# cw-lite-main.net
KiCad netlist of a schematic drawn in EAGLE
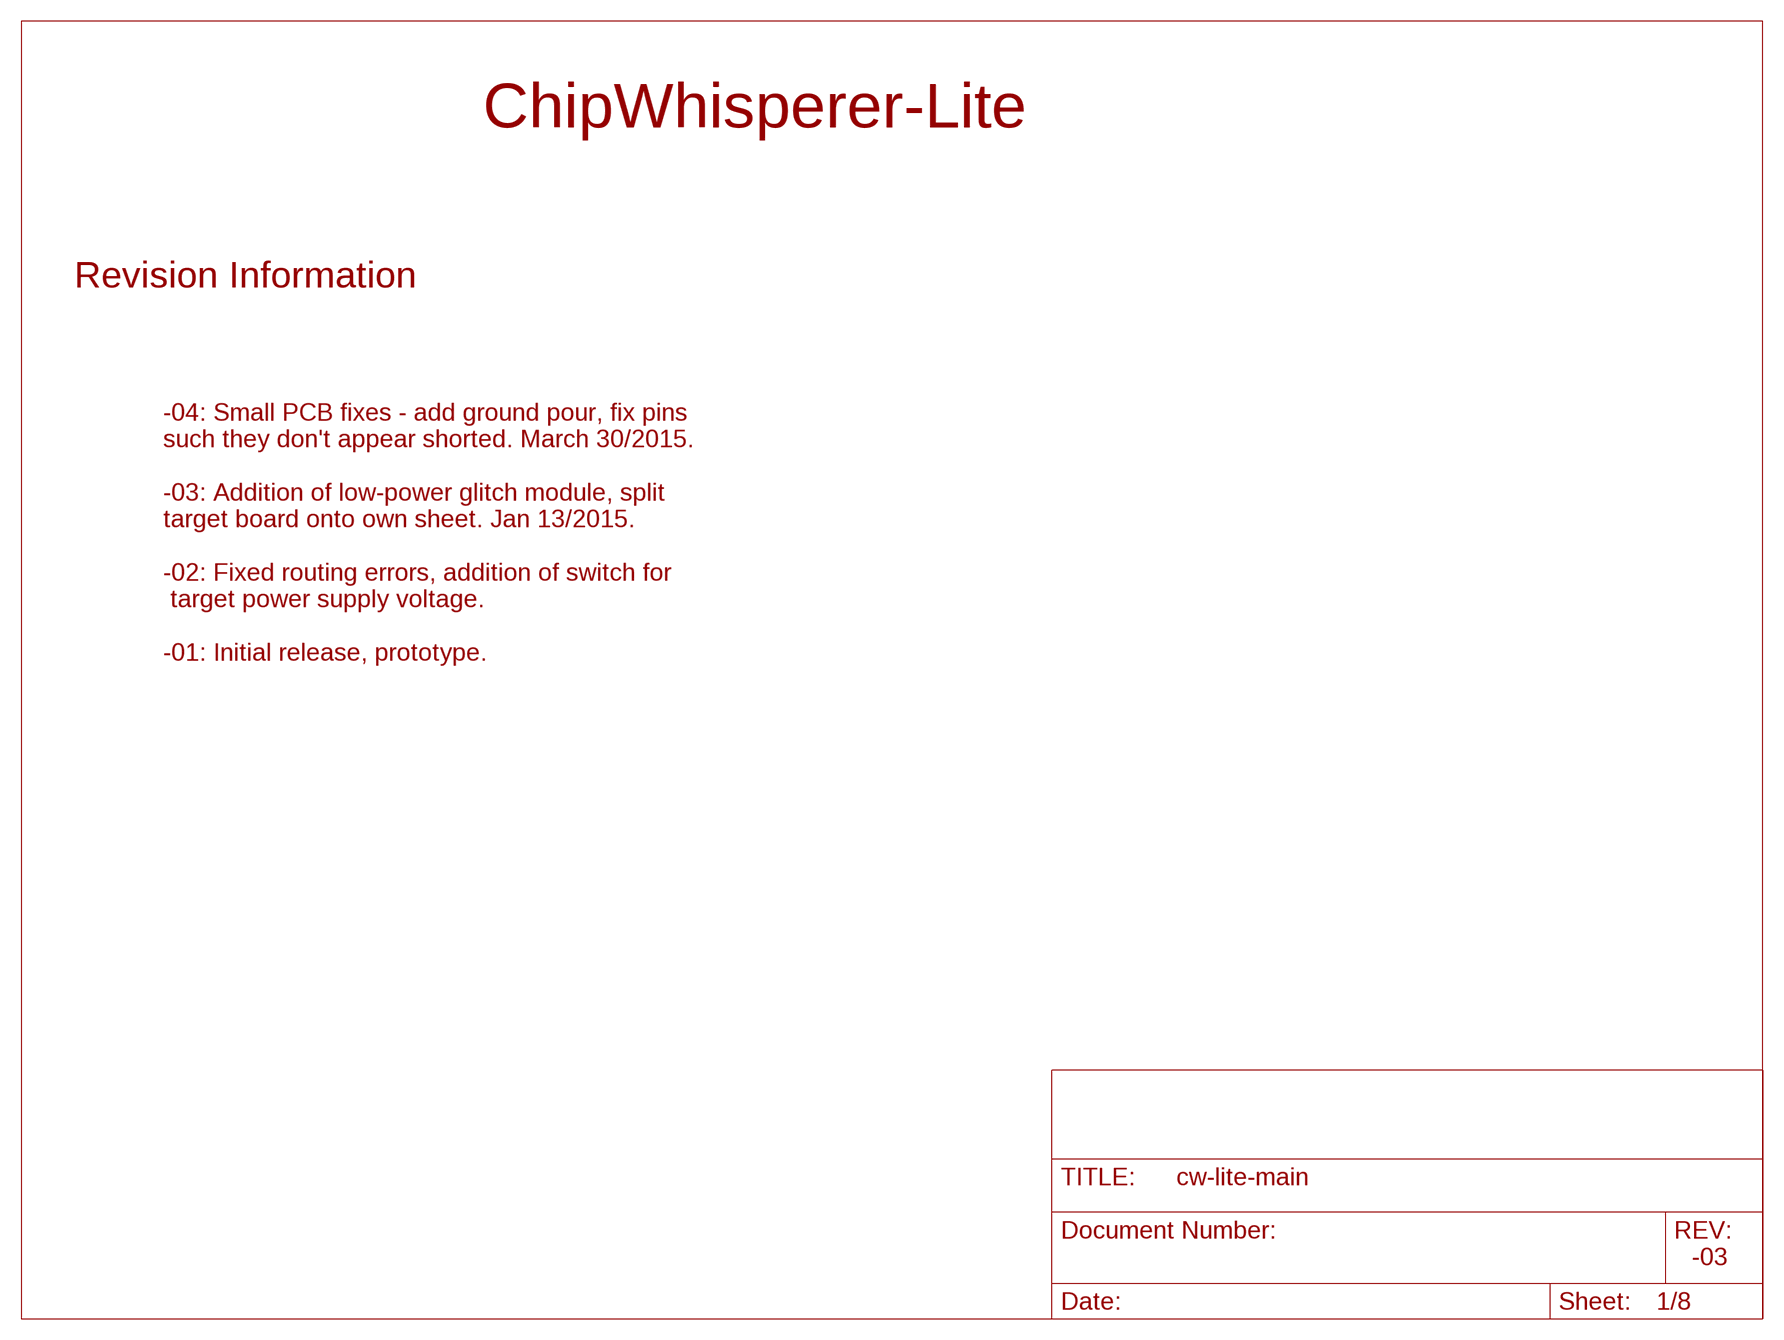
[diagram p0: schematic, sheet 1]
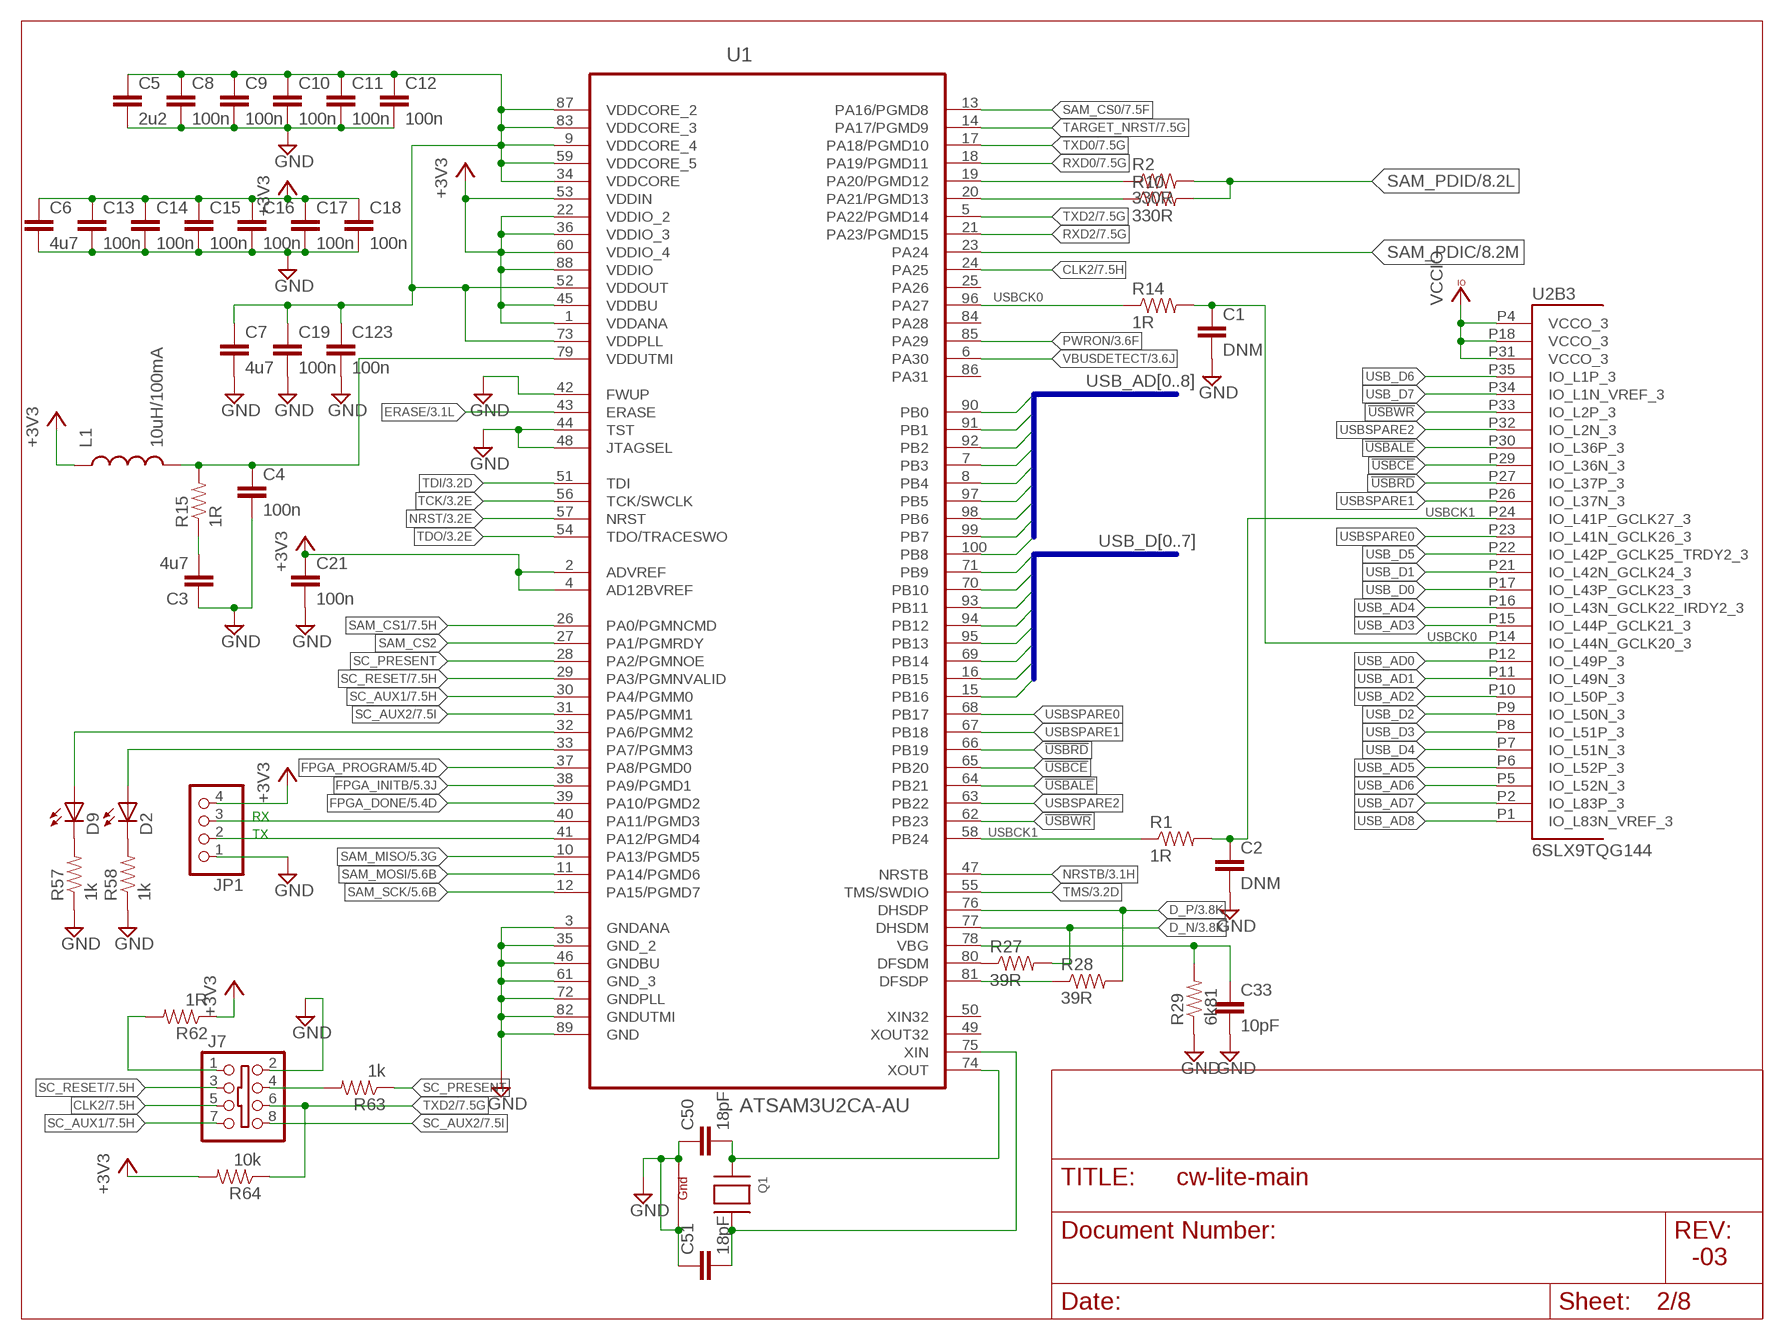
[diagram p1: schematic, sheet 2]
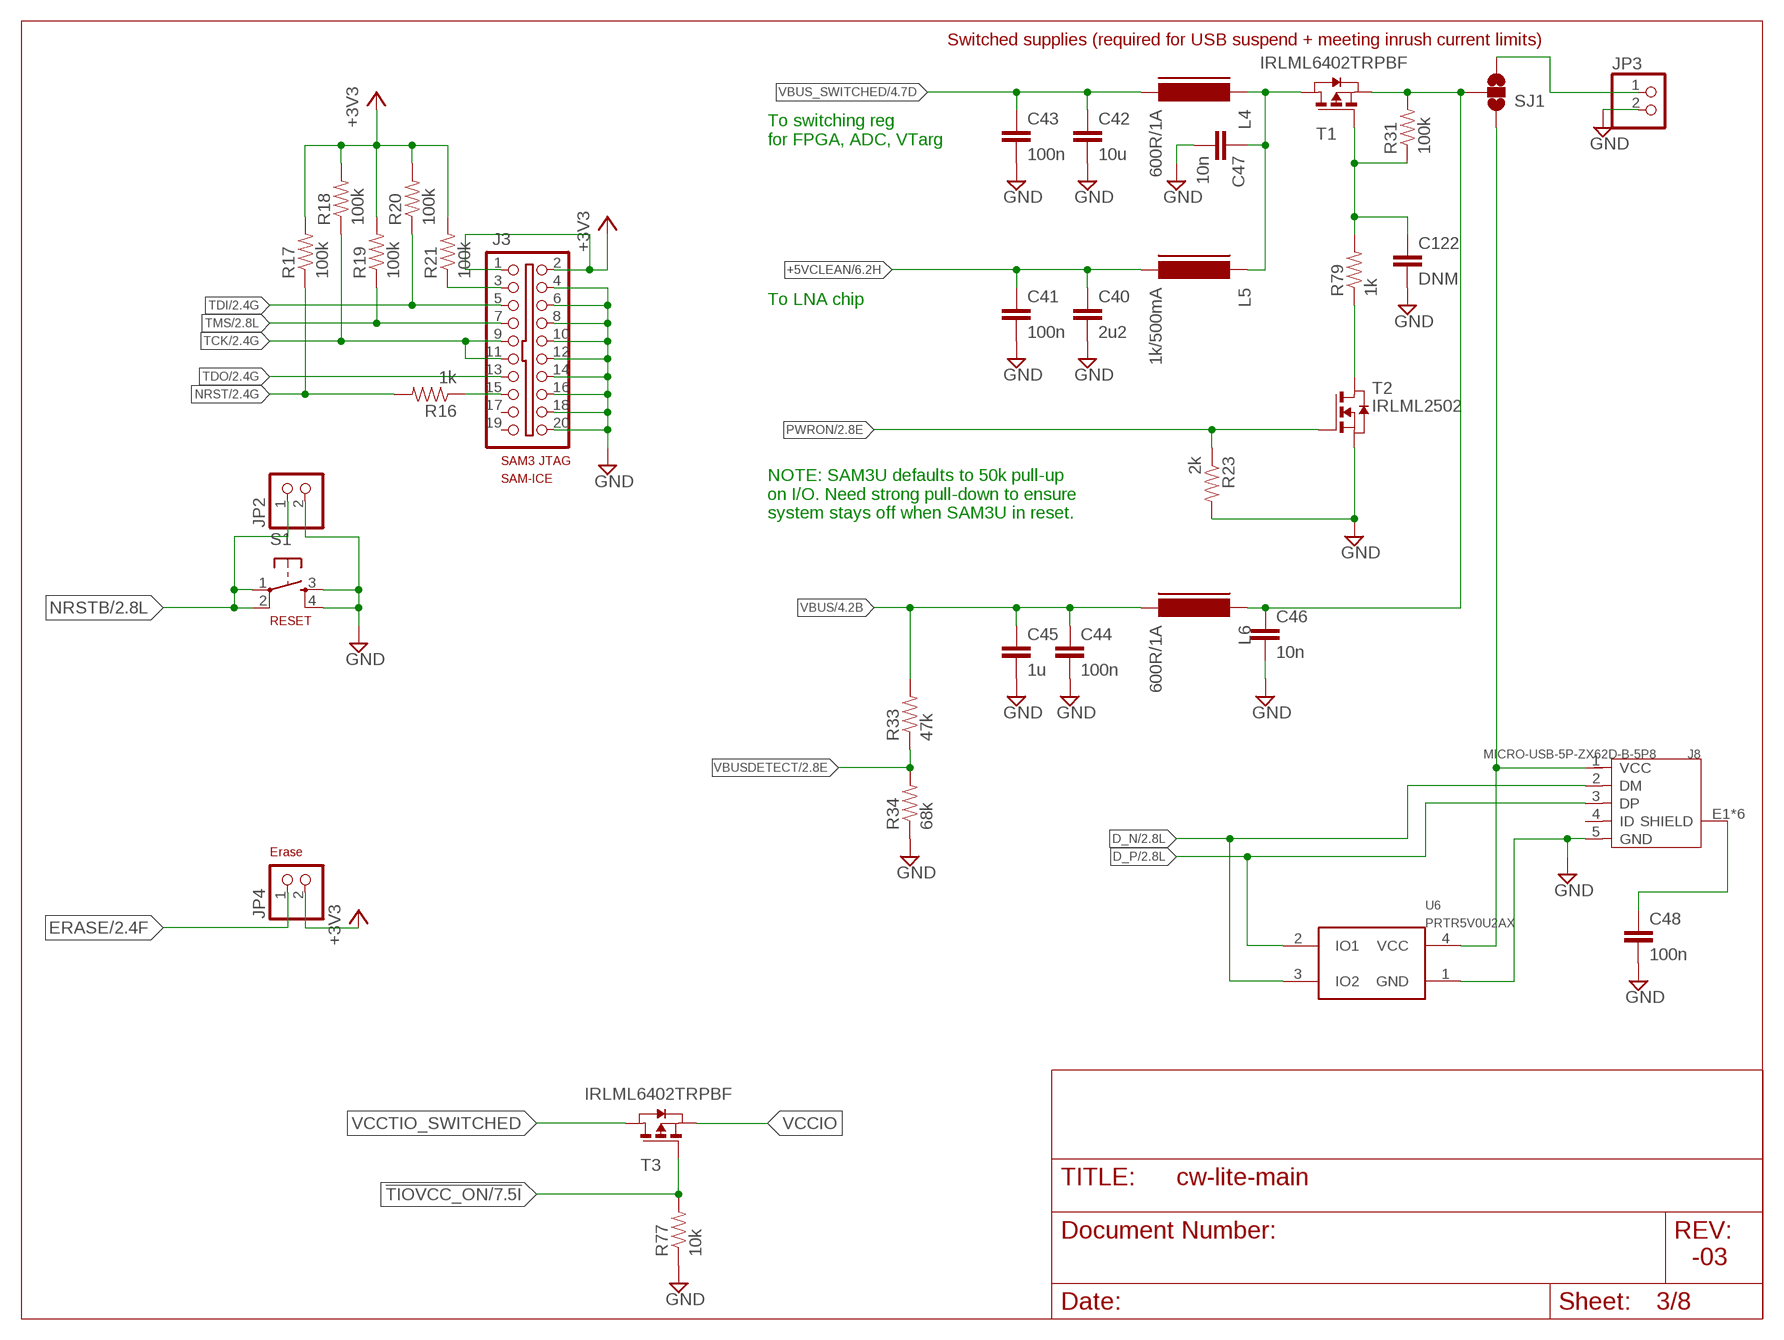
[diagram p2: schematic, sheet 3]
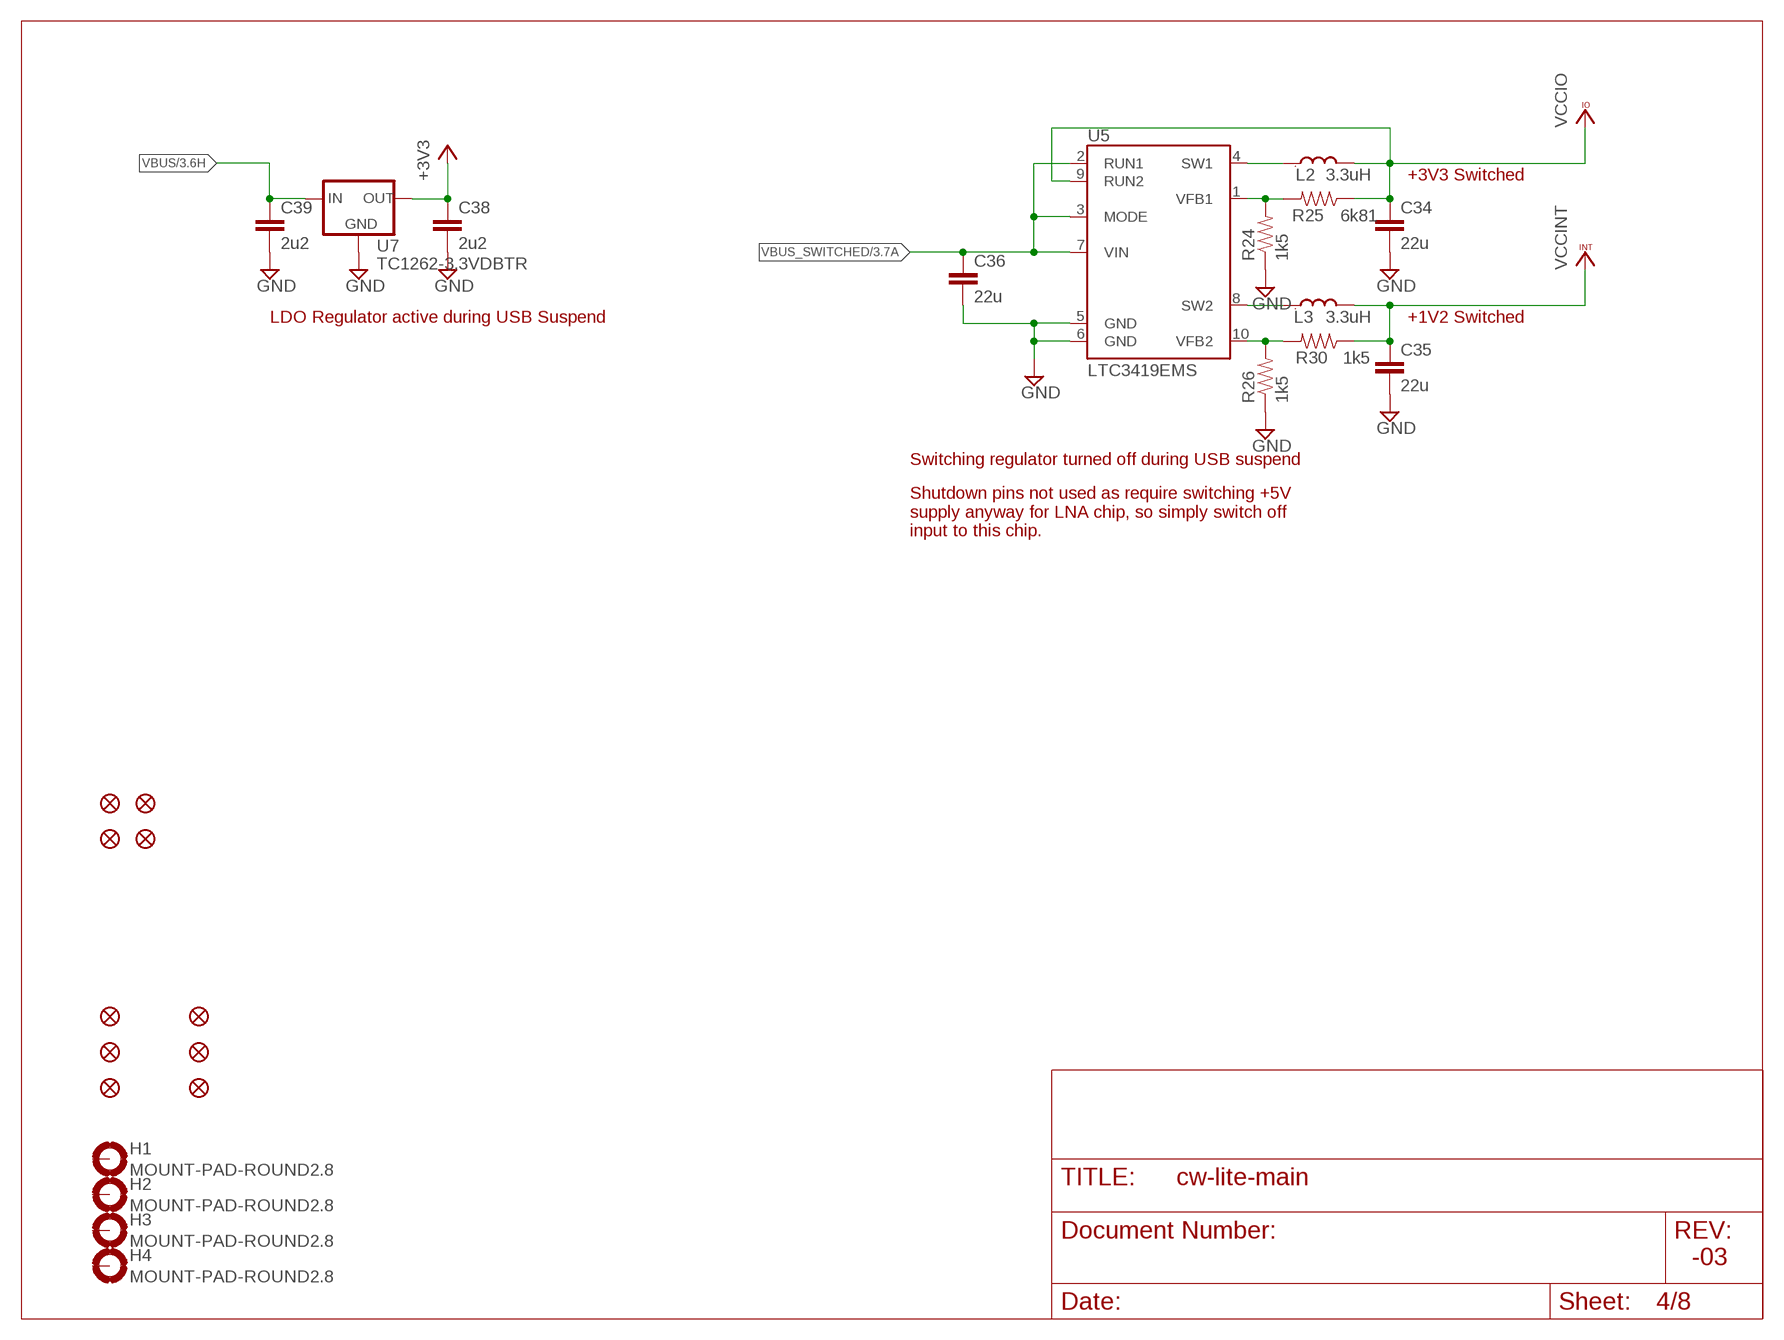
[diagram p3: schematic, sheet 4]
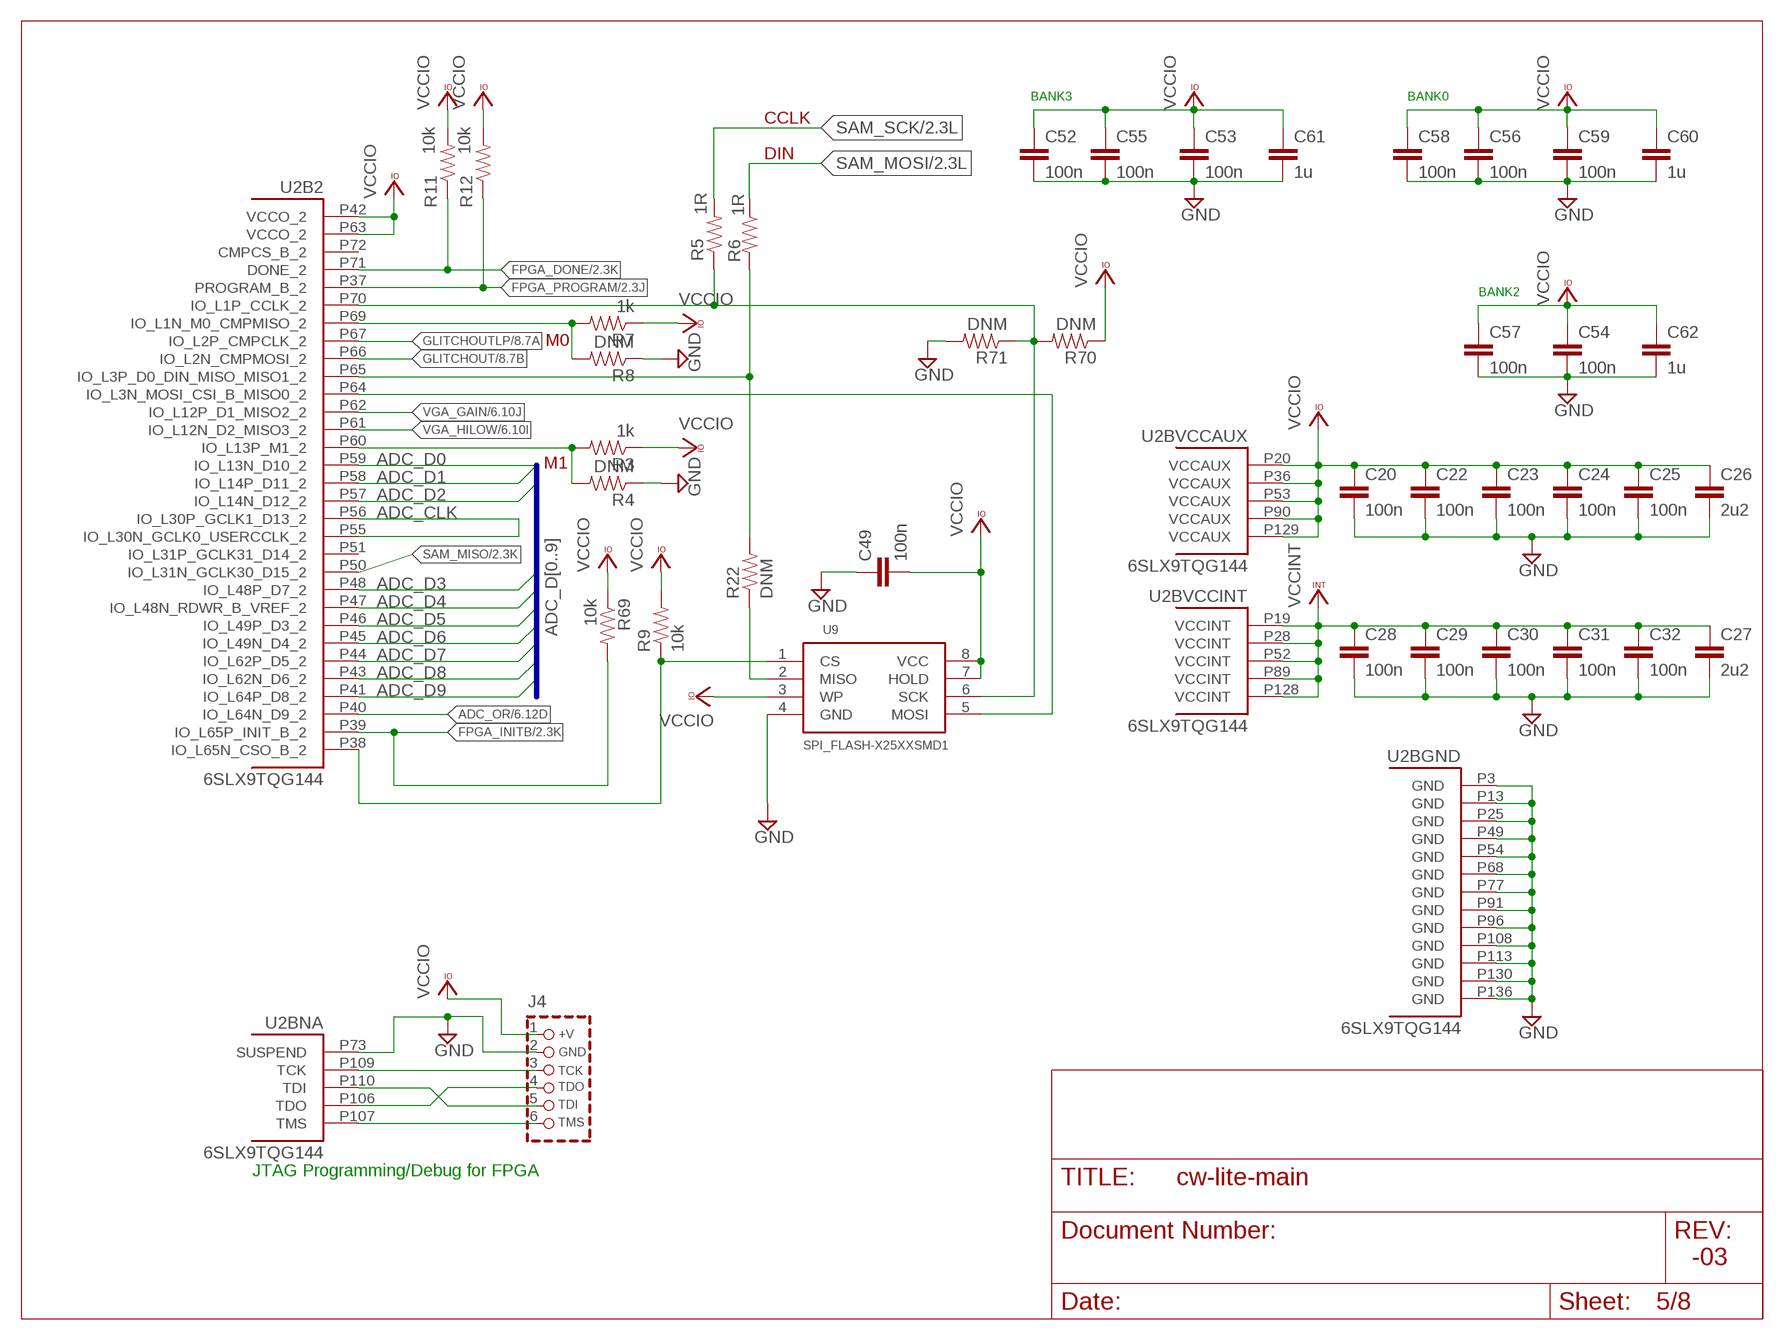
[diagram p4: schematic, sheet 5]
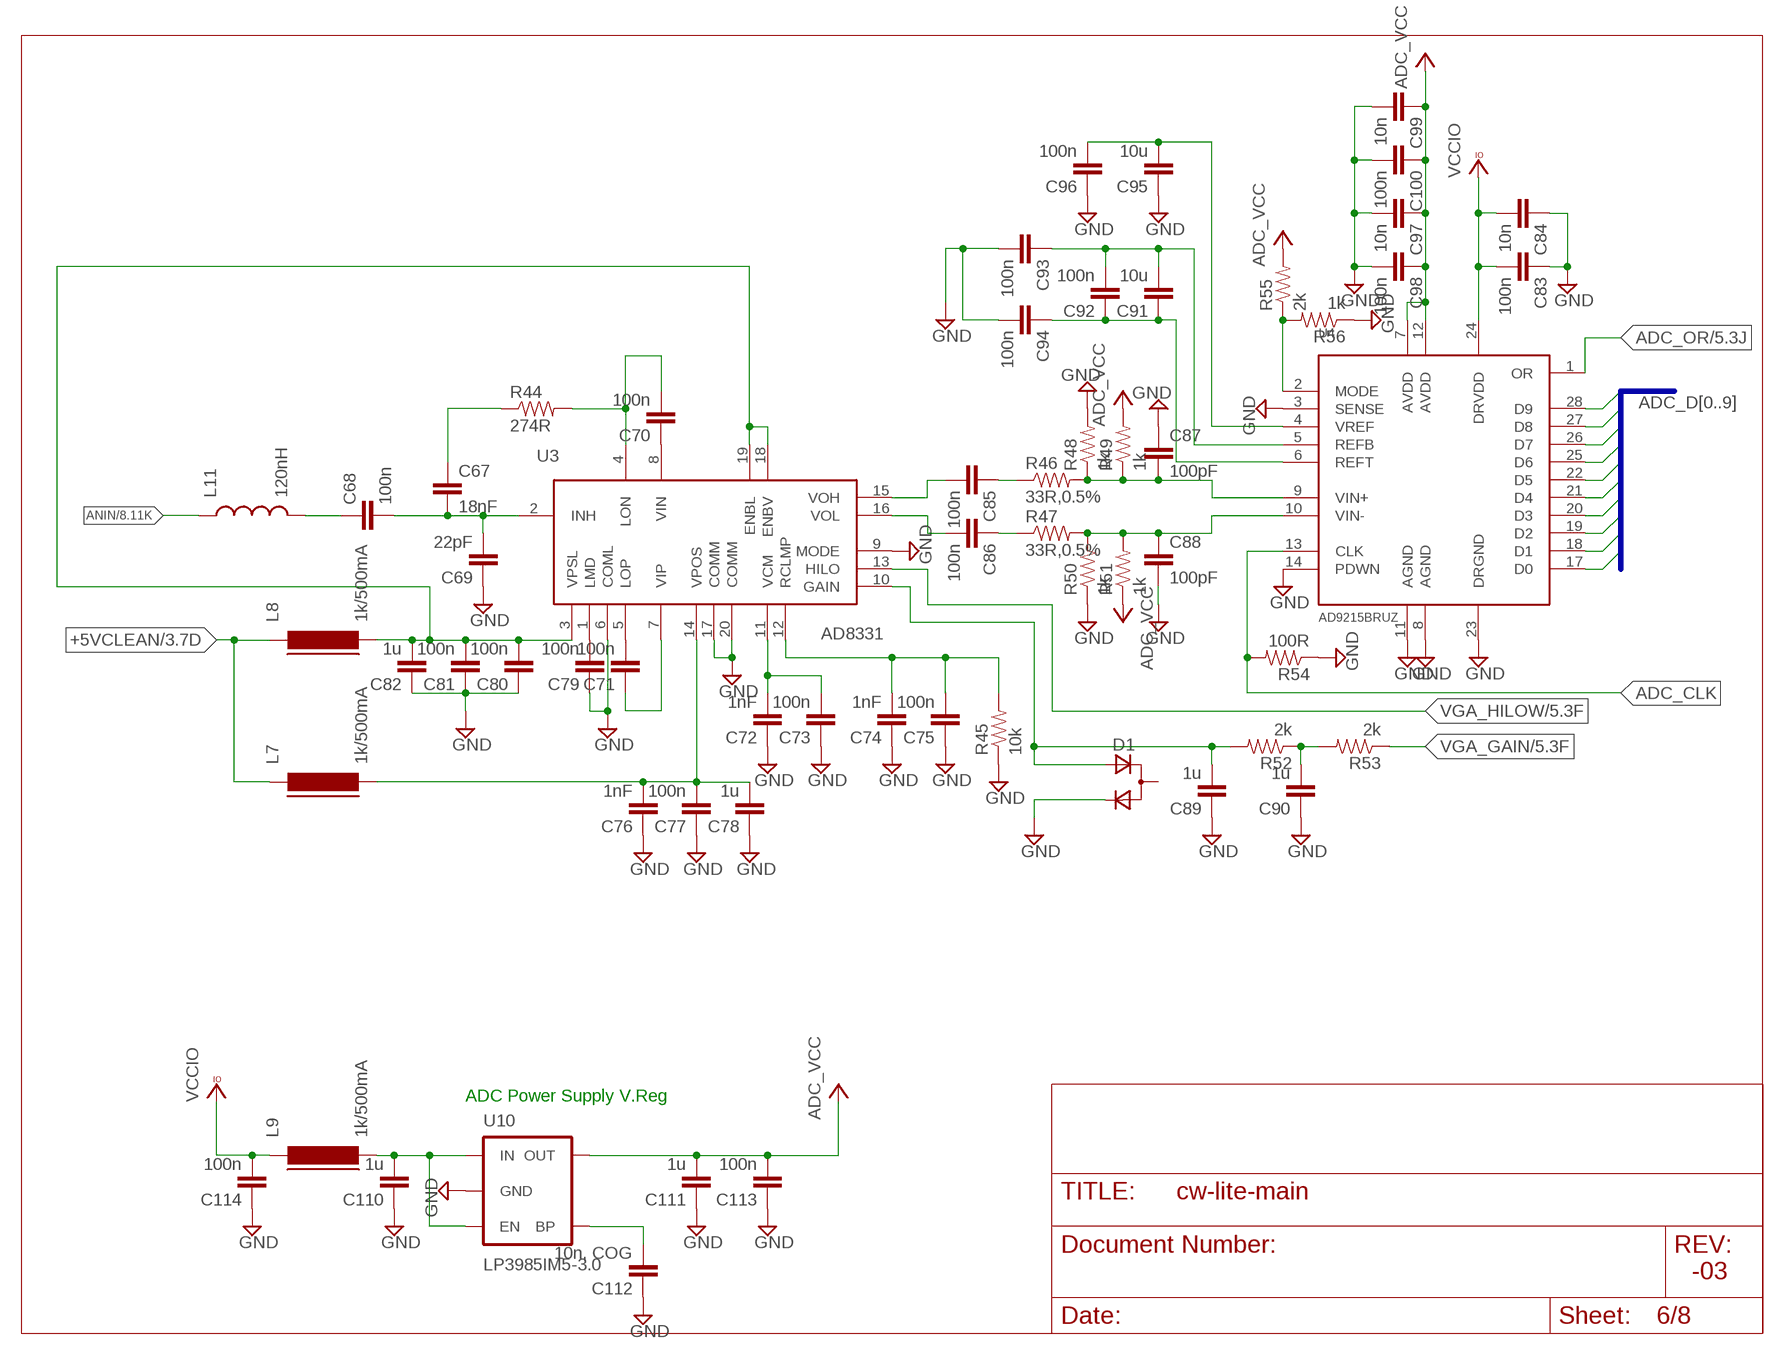
[diagram p5: schematic, sheet 6]
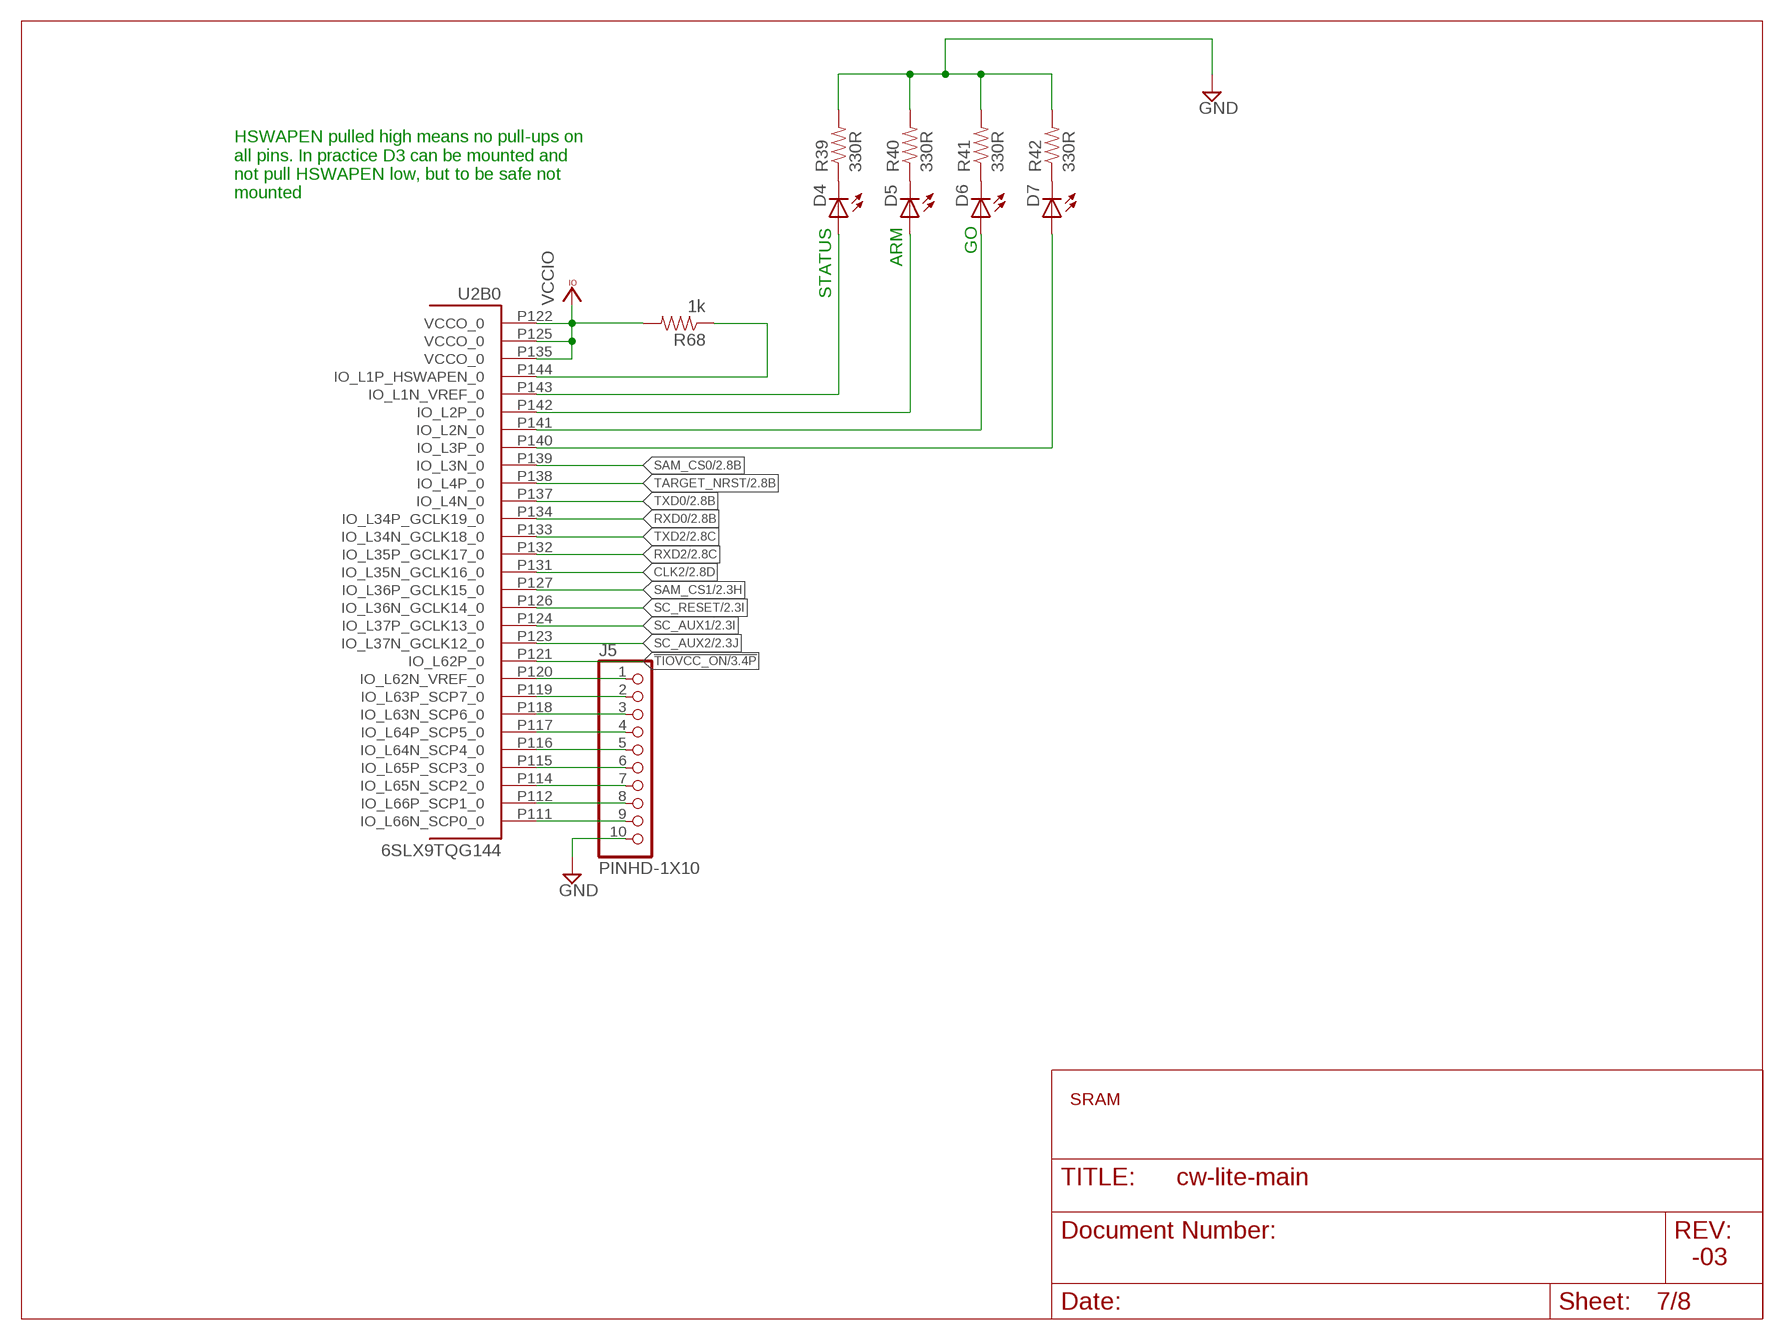
[diagram p6: schematic, sheet 7]
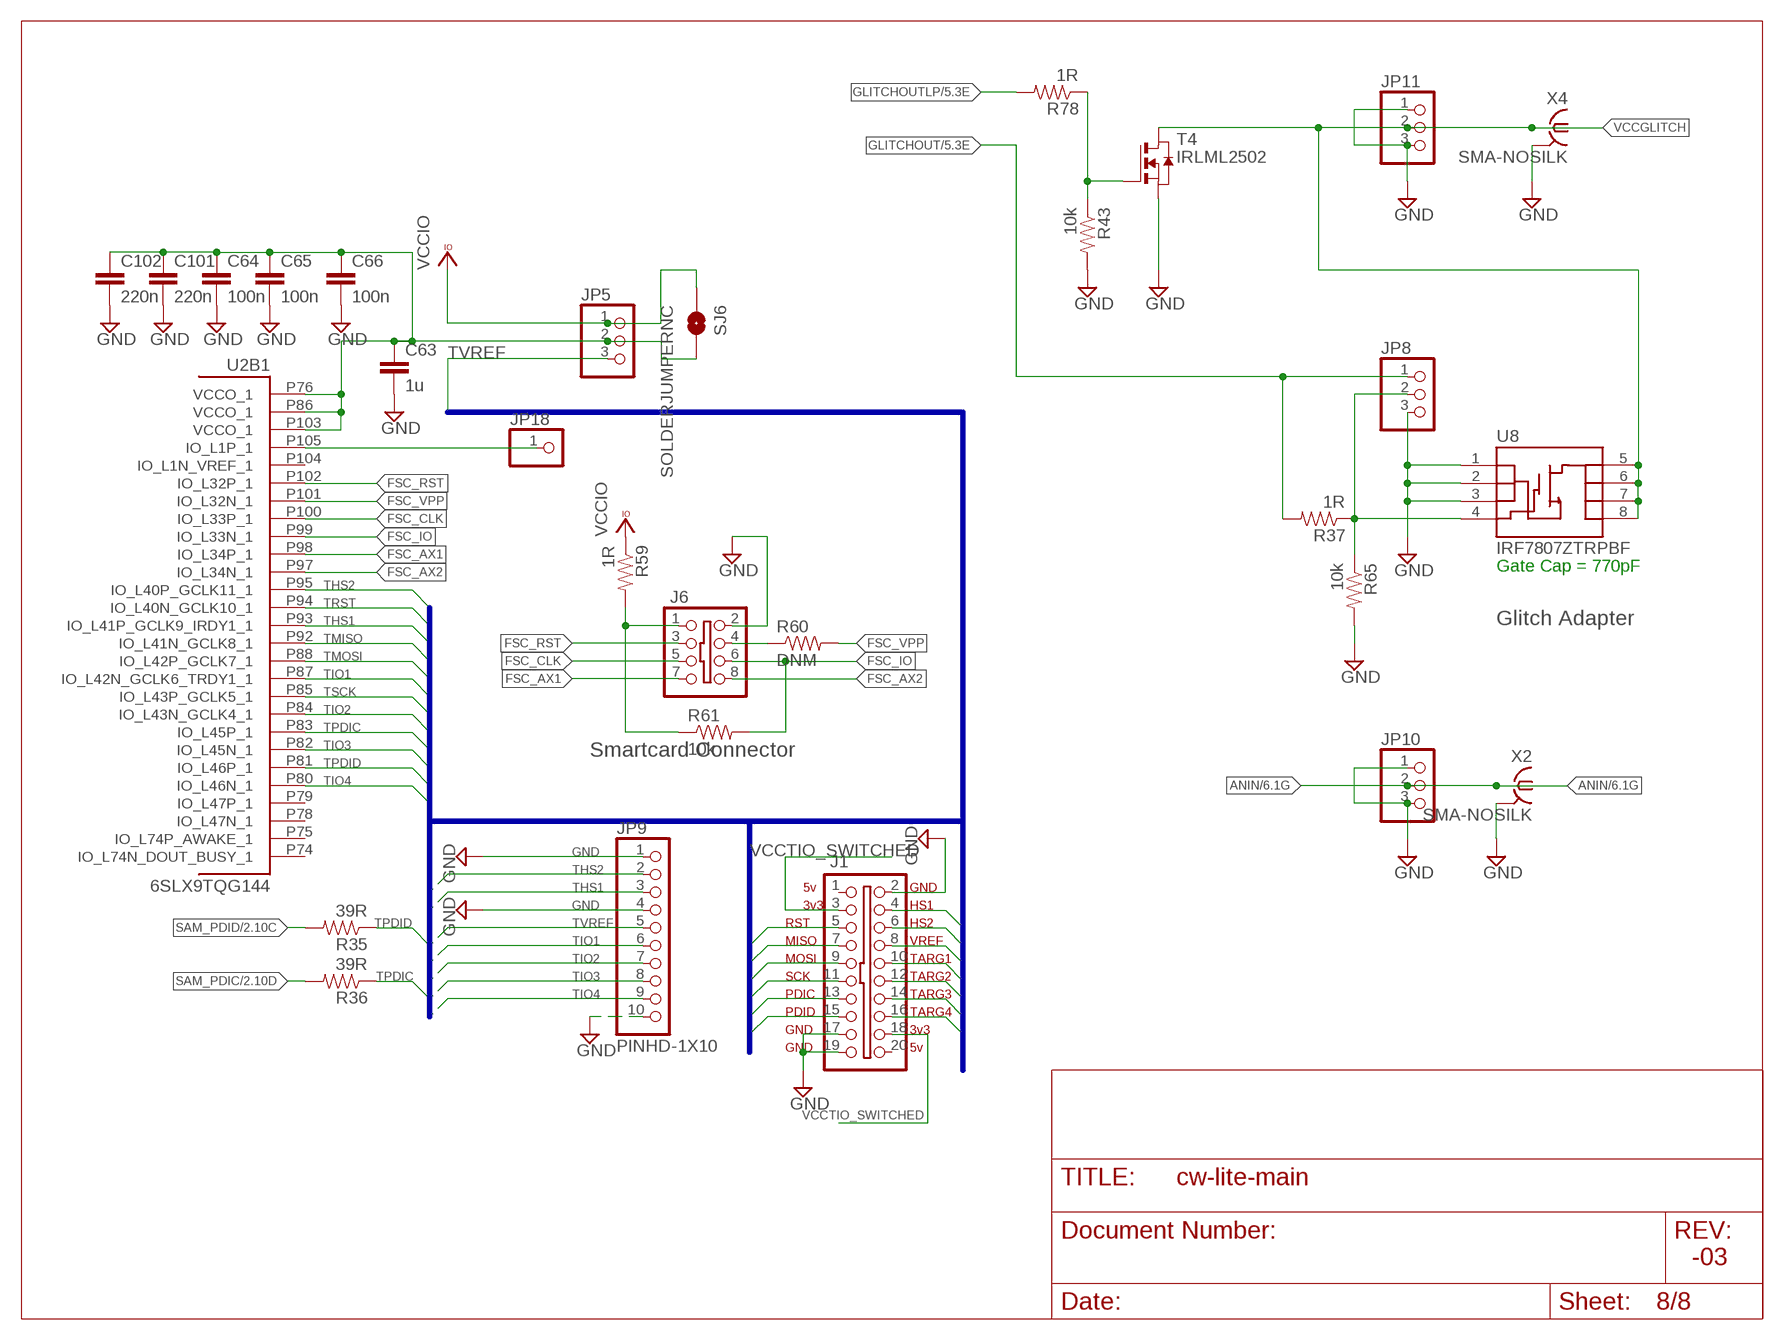
[diagram p7: schematic, sheet 8]

(export (version "E")
  (design (tool "Eeschema 10.0.6"))
  (components
    (comp (ref "D4")
      (value "LED0603")
      (footprint "eagle-import:LED-0603")
      (libsource (lib "eagle-import") (part "LED0603"))
    )
    (comp (ref "D5")
      (value "LED0603")
      (footprint "eagle-import:LED-0603")
      (libsource (lib "eagle-import") (part "LED0603"))
    )
    (comp (ref "D6")
      (value "LED0603")
      (footprint "eagle-import:LED-0603")
      (libsource (lib "eagle-import") (part "LED0603"))
    )
    (comp (ref "D7")
      (value "LED0603")
      (footprint "eagle-import:LED-0603")
      (libsource (lib "eagle-import") (part "LED0603"))
    )
    (comp (ref "J5")
      (value "PINHD-1X10")
      (footprint "eagle-import:1X10-BIG")
      (libsource (lib "eagle-import") (part "PINHD-1X10"))
    )
    (comp (ref "R39")
      (value "330R")
      (footprint "eagle-import:0402R")
      (libsource (lib "eagle-import") (part "custom-std_RES0402-RES"))
    )
    (comp (ref "R40")
      (value "330R")
      (footprint "eagle-import:0402R")
      (libsource (lib "eagle-import") (part "custom-std_RES0402-RES"))
    )
    (comp (ref "R41")
      (value "330R")
      (footprint "eagle-import:0402R")
      (libsource (lib "eagle-import") (part "custom-std_RES0402-RES"))
    )
    (comp (ref "R42")
      (value "330R")
      (footprint "eagle-import:0402R")
      (libsource (lib "eagle-import") (part "custom-std_RES0402-RES"))
    )
    (comp (ref "R68")
      (value "1k")
      (footprint "eagle-import:0402R")
      (libsource (lib "eagle-import") (part "custom-std_RES0402-RES"))
    )
    (comp (ref "U2")
      (value "6SLX9TQG144")
      (footprint "eagle-import:TQ144")
      (fields (field (name "MPN") "XC6SLX9-3TQG144C") (field (name "OC_DIGIKEY") "122-1748-ND"))
      (libsource (lib "eagle-import") (part "6SLX9TQG144"))
    )
    (comp (ref "C40")
      (value "2u2")
      (footprint "eagle-import:0603C")
      (libsource (lib "eagle-import") (part "custom-std_CAP0603-CAP"))
    )
    (comp (ref "C41")
      (value "100n")
      (footprint "eagle-import:0603C")
      (libsource (lib "eagle-import") (part "custom-std_CAP0603-CAP"))
    )
    (comp (ref "C42")
      (value "10u")
      (footprint "eagle-import:0603C")
      (libsource (lib "eagle-import") (part "custom-std_CAP0603-CAP"))
    )
    (comp (ref "C43")
      (value "100n")
      (footprint "eagle-import:0603C")
      (libsource (lib "eagle-import") (part "custom-std_CAP0603-CAP"))
    )
    (comp (ref "C44")
      (value "100n")
      (footprint "eagle-import:0603C")
      (libsource (lib "eagle-import") (part "custom-std_CAP0603-CAP"))
    )
    (comp (ref "C45")
      (value "1u")
      (footprint "eagle-import:0603C")
      (libsource (lib "eagle-import") (part "custom-std_CAP0603-CAP"))
    )
    (comp (ref "C46")
      (value "10n")
      (footprint "eagle-import:0603C")
      (libsource (lib "eagle-import") (part "custom-std_CAP0603-CAP"))
    )
    (comp (ref "C47")
      (value "10n")
      (footprint "eagle-import:0603C")
      (libsource (lib "eagle-import") (part "custom-std_CAP0603-CAP"))
    )
    (comp (ref "C48")
      (value "100n")
      (footprint "eagle-import:0603C")
      (libsource (lib "eagle-import") (part "custom-std_CAP0603-CAP"))
    )
    (comp (ref "C122")
      (value "DNM")
      (footprint "eagle-import:0603C")
      (libsource (lib "eagle-import") (part "custom-std_CAP0603-CAP"))
    )
    (comp (ref "J3")
      (value "SHROUD_2X10-SHROUDED")
      (footprint "eagle-import:PINSHRD_PTH_2X10")
      (libsource (lib "eagle-import") (part "SHROUD_2X10-SHROUDED"))
    )
    (comp (ref "J8")
      (value "MICRO-USB-5P-ZX62D-B-5P8")
      (footprint "eagle-import:B-SMD-5P-TH")
      (fields (field (name "MPN") "ZX62D-B-5P8") (field (name "OC_DIGIKEY") "H11610CT-ND"))
      (libsource (lib "eagle-import") (part "MICRO-USB-5P-ZX62D-B-5P8"))
    )
    (comp (ref "JP2")
      (value "PINHD-1X2")
      (footprint "eagle-import:1X02")
      (libsource (lib "eagle-import") (part "PINHD-1X2"))
    )
    (comp (ref "JP3")
      (value "PINHD-1X2")
      (footprint "eagle-import:1X02")
      (libsource (lib "eagle-import") (part "PINHD-1X2"))
    )
    (comp (ref "JP4")
      (value "PINHD-1X2")
      (footprint "eagle-import:1X02")
      (libsource (lib "eagle-import") (part "PINHD-1X2"))
    )
    (comp (ref "L4")
      (value "600R/1A")
      (footprint "eagle-import:FB603")
      (libsource (lib "eagle-import") (part "FERRITE-0603"))
    )
    (comp (ref "L5")
      (value "1k/500mA")
      (footprint "eagle-import:FB603")
      (libsource (lib "eagle-import") (part "FERRITE-0603"))
    )
    (comp (ref "L6")
      (value "600R/1A")
      (footprint "eagle-import:FB603")
      (libsource (lib "eagle-import") (part "FERRITE-0603"))
    )
    (comp (ref "R16")
      (value "1k")
      (footprint "eagle-import:0402R")
      (libsource (lib "eagle-import") (part "RES0402-RES"))
    )
    (comp (ref "R17")
      (value "100k")
      (footprint "eagle-import:0402R")
      (libsource (lib "eagle-import") (part "RES0402-RES"))
    )
    (comp (ref "R18")
      (value "100k")
      (footprint "eagle-import:0402R")
      (libsource (lib "eagle-import") (part "RES0402-RES"))
    )
    (comp (ref "R19")
      (value "100k")
      (footprint "eagle-import:0402R")
      (libsource (lib "eagle-import") (part "RES0402-RES"))
    )
    (comp (ref "R20")
      (value "100k")
      (footprint "eagle-import:0402R")
      (libsource (lib "eagle-import") (part "RES0402-RES"))
    )
    (comp (ref "R21")
      (value "100k")
      (footprint "eagle-import:0402R")
      (libsource (lib "eagle-import") (part "RES0402-RES"))
    )
    (comp (ref "R23")
      (value "2k")
      (footprint "eagle-import:0603R")
      (libsource (lib "eagle-import") (part "custom-std_RES0603-RES"))
    )
    (comp (ref "R31")
      (value "100k")
      (footprint "eagle-import:0402R")
      (libsource (lib "eagle-import") (part "custom-std_RES0402-RES"))
    )
    (comp (ref "R33")
      (value "47k")
      (footprint "eagle-import:0402R")
      (libsource (lib "eagle-import") (part "custom-std_RES0402-RES"))
    )
    (comp (ref "R34")
      (value "68k")
      (footprint "eagle-import:0402R")
      (libsource (lib "eagle-import") (part "custom-std_RES0402-RES"))
    )
    (comp (ref "R77")
      (value "10k")
      (footprint "eagle-import:0402R")
      (libsource (lib "eagle-import") (part "custom-std_RES0402-RES"))
    )
    (comp (ref "R79")
      (value "1k")
      (footprint "eagle-import:0603R")
      (libsource (lib "eagle-import") (part "custom-std_RES0603-RES"))
    )
    (comp (ref "S1")
      (value "TAC_SWITCHSMD")
      (footprint "eagle-import:TACTILE_SWITCH_SMD")
      (libsource (lib "eagle-import") (part "TAC_SWITCHSMD"))
    )
    (comp (ref "SJ1")
      (value "SOLDERJUMPER_2WAYPASTE1&2")
      (footprint "eagle-import:SJ_3_PASTE1&2")
      (libsource (lib "eagle-import") (part "SOLDERJUMPER_2WAYPASTE1&2"))
    )
    (comp (ref "T1")
      (value "IRLML6402TRPBF")
      (footprint "eagle-import:SOT-23")
      (fields (field (name "MPN") "IRLML6402TRPBF") (field (name "OC_DIGIKEY") "IRLML6402PBFCT-ND"))
      (libsource (lib "eagle-import") (part "PMOSSOT23"))
    )
    (comp (ref "T2")
      (value "IRLML2502")
      (footprint "eagle-import:SOT-23")
      (fields (field (name "MPN") "IRLML2502TRPBF") (field (name "OC_DIGIKEY") "IRLML2502PBFCT-ND"))
      (libsource (lib "eagle-import") (part "NMOSSOT23"))
    )
    (comp (ref "T3")
      (value "IRLML6402TRPBF")
      (footprint "eagle-import:SOT-23")
      (fields (field (name "MPN") "IRLML6402TRPBF") (field (name "OC_DIGIKEY") "IRLML6402PBFCT-ND"))
      (libsource (lib "eagle-import") (part "PMOSSOT23"))
    )
    (comp (ref "U6")
      (value "PRTR5V0U2AX")
      (footprint "eagle-import:SOT143B")
      (fields (field (name "MPN") "PRTR5V0U2AX,215") (field (name "OC_DIGIKEY") "568-4139-1-ND"))
      (libsource (lib "eagle-import") (part "PRTR5V0U2AX"))
    )
    (comp (ref "C67")
      (value "18nF")
      (footprint "eagle-import:0603C")
      (libsource (lib "eagle-import") (part "custom-std_CAP0603-CAP"))
    )
    (comp (ref "C68")
      (value "100n")
      (footprint "eagle-import:0603C")
      (libsource (lib "eagle-import") (part "custom-std_CAP0603-CAP"))
    )
    (comp (ref "C69")
      (value "22pF")
      (footprint "eagle-import:0603C")
      (libsource (lib "eagle-import") (part "custom-std_CAP0603-CAP"))
    )
    (comp (ref "C70")
      (value "100n")
      (footprint "eagle-import:0402C")
      (libsource (lib "eagle-import") (part "custom-std_CAP0402-CAP"))
    )
    (comp (ref "C71")
      (value "100n")
      (footprint "eagle-import:0402C")
      (libsource (lib "eagle-import") (part "custom-std_CAP0402-CAP"))
    )
    (comp (ref "C72")
      (value "1nF")
      (footprint "eagle-import:0402C")
      (libsource (lib "eagle-import") (part "custom-std_CAP0402-CAP"))
    )
    (comp (ref "C73")
      (value "100n")
      (footprint "eagle-import:0402C")
      (libsource (lib "eagle-import") (part "custom-std_CAP0402-CAP"))
    )
    (comp (ref "C74")
      (value "1nF")
      (footprint "eagle-import:0402C")
      (libsource (lib "eagle-import") (part "custom-std_CAP0402-CAP"))
    )
    (comp (ref "C75")
      (value "100n")
      (footprint "eagle-import:0402C")
      (libsource (lib "eagle-import") (part "custom-std_CAP0402-CAP"))
    )
    (comp (ref "C76")
      (value "1nF")
      (footprint "eagle-import:0402C")
      (libsource (lib "eagle-import") (part "custom-std_CAP0402-CAP"))
    )
    (comp (ref "C77")
      (value "100n")
      (footprint "eagle-import:0402C")
      (libsource (lib "eagle-import") (part "custom-std_CAP0402-CAP"))
    )
    (comp (ref "C78")
      (value "1u")
      (footprint "eagle-import:0603C")
      (libsource (lib "eagle-import") (part "custom-std_CAP0603-CAP"))
    )
    (comp (ref "C79")
      (value "100n")
      (footprint "eagle-import:0402C")
      (libsource (lib "eagle-import") (part "custom-std_CAP0402-CAP"))
    )
    (comp (ref "C80")
      (value "100n")
      (footprint "eagle-import:0402C")
      (libsource (lib "eagle-import") (part "custom-std_CAP0402-CAP"))
    )
    (comp (ref "C81")
      (value "100n")
      (footprint "eagle-import:0402C")
      (libsource (lib "eagle-import") (part "custom-std_CAP0402-CAP"))
    )
    (comp (ref "C82")
      (value "1u")
      (footprint "eagle-import:0603C")
      (libsource (lib "eagle-import") (part "custom-std_CAP0603-CAP"))
    )
    (comp (ref "C83")
      (value "100n")
      (footprint "eagle-import:0402C")
      (libsource (lib "eagle-import") (part "custom-std_CAP0402-CAP"))
    )
    (comp (ref "C84")
      (value "10n")
      (footprint "eagle-import:0402C")
      (libsource (lib "eagle-import") (part "custom-std_CAP0402-CAP"))
    )
    (comp (ref "C85")
      (value "100n")
      (footprint "eagle-import:0603C")
      (libsource (lib "eagle-import") (part "custom-std_CAP0603-CAP"))
    )
    (comp (ref "C86")
      (value "100n")
      (footprint "eagle-import:0603C")
      (libsource (lib "eagle-import") (part "custom-std_CAP0603-CAP"))
    )
    (comp (ref "C87")
      (value "100pF")
      (footprint "eagle-import:0603C")
      (libsource (lib "eagle-import") (part "custom-std_CAP0603-CAP"))
    )
    (comp (ref "C88")
      (value "100pF")
      (footprint "eagle-import:0603C")
      (libsource (lib "eagle-import") (part "custom-std_CAP0603-CAP"))
    )
    (comp (ref "C89")
      (value "1u")
      (footprint "eagle-import:0603C")
      (libsource (lib "eagle-import") (part "custom-std_CAP0603-CAP"))
    )
    (comp (ref "C90")
      (value "1u")
      (footprint "eagle-import:0603C")
      (libsource (lib "eagle-import") (part "custom-std_CAP0603-CAP"))
    )
    (comp (ref "C91")
      (value "10u")
      (footprint "eagle-import:0603C")
      (libsource (lib "eagle-import") (part "custom-std_CAP0603-CAP"))
    )
    (comp (ref "C92")
      (value "100n")
      (footprint "eagle-import:0402C")
      (libsource (lib "eagle-import") (part "custom-std_CAP0402-CAP"))
    )
    (comp (ref "C93")
      (value "100n")
      (footprint "eagle-import:0402C")
      (libsource (lib "eagle-import") (part "custom-std_CAP0402-CAP"))
    )
    (comp (ref "C94")
      (value "100n")
      (footprint "eagle-import:0402C")
      (libsource (lib "eagle-import") (part "custom-std_CAP0402-CAP"))
    )
    (comp (ref "C95")
      (value "10u")
      (footprint "eagle-import:0603C")
      (libsource (lib "eagle-import") (part "custom-std_CAP0603-CAP"))
    )
    (comp (ref "C96")
      (value "100n")
      (footprint "eagle-import:0402C")
      (libsource (lib "eagle-import") (part "custom-std_CAP0402-CAP"))
    )
    (comp (ref "C97")
      (value "10n")
      (footprint "eagle-import:0402C")
      (libsource (lib "eagle-import") (part "custom-std_CAP0402-CAP"))
    )
    (comp (ref "C98")
      (value "100n")
      (footprint "eagle-import:0402C")
      (libsource (lib "eagle-import") (part "custom-std_CAP0402-CAP"))
    )
    (comp (ref "C99")
      (value "10n")
      (footprint "eagle-import:0402C")
      (libsource (lib "eagle-import") (part "custom-std_CAP0402-CAP"))
    )
    (comp (ref "C100")
      (value "100n")
      (footprint "eagle-import:0402C")
      (libsource (lib "eagle-import") (part "custom-std_CAP0402-CAP"))
    )
    (comp (ref "C110")
      (value "1u")
      (footprint "eagle-import:0603C")
      (libsource (lib "eagle-import") (part "custom-std_CAP0603-CAP"))
    )
    (comp (ref "C111")
      (value "1u")
      (footprint "eagle-import:0603C")
      (libsource (lib "eagle-import") (part "custom-std_CAP0603-CAP"))
    )
    (comp (ref "C112")
      (value "10n, COG")
      (footprint "eagle-import:0402C")
      (libsource (lib "eagle-import") (part "custom-std_CAP0402-CAP"))
    )
    (comp (ref "C113")
      (value "100n")
      (footprint "eagle-import:0402C")
      (libsource (lib "eagle-import") (part "custom-std_CAP0402-CAP"))
    )
    (comp (ref "C114")
      (value "100n")
      (footprint "eagle-import:0402C")
      (libsource (lib "eagle-import") (part "custom-std_CAP0402-CAP"))
    )
    (comp (ref "D1")
      (value "D_ACACSOT23")
      (footprint "eagle-import:SOT-23")
      (fields (field (name "MPN") "BAV99-7F"))
      (libsource (lib "eagle-import") (part "D_ACACSOT23"))
    )
    (comp (ref "L7")
      (value "1k/500mA")
      (footprint "eagle-import:FB603")
      (libsource (lib "eagle-import") (part "FERRITE-0603"))
    )
    (comp (ref "L8")
      (value "1k/500mA")
      (footprint "eagle-import:FB603")
      (libsource (lib "eagle-import") (part "FERRITE-0603"))
    )
    (comp (ref "L9")
      (value "1k/500mA")
      (footprint "eagle-import:FB603")
      (libsource (lib "eagle-import") (part "FERRITE-0603"))
    )
    (comp (ref "L11")
      (value "120nH")
      (footprint "eagle-import:0603")
      (libsource (lib "eagle-import") (part "INDUCTOR0603"))
    )
    (comp (ref "R44")
      (value "274R")
      (footprint "eagle-import:0603R")
      (libsource (lib "eagle-import") (part "custom-std_RES0603-RES"))
    )
    (comp (ref "R45")
      (value "10k")
      (footprint "eagle-import:0603R")
      (libsource (lib "eagle-import") (part "custom-std_RES0603-RES"))
    )
    (comp (ref "R46")
      (value "33R,0.5%")
      (footprint "eagle-import:0603R")
      (libsource (lib "eagle-import") (part "custom-std_RES0603-RES"))
    )
    (comp (ref "R47")
      (value "33R,0.5%")
      (footprint "eagle-import:0603R")
      (libsource (lib "eagle-import") (part "custom-std_RES0603-RES"))
    )
    (comp (ref "R48")
      (value "1k")
      (footprint "eagle-import:0402R")
      (libsource (lib "eagle-import") (part "custom-std_RES0402-RES"))
    )
    (comp (ref "R49")
      (value "1k")
      (footprint "eagle-import:0402R")
      (libsource (lib "eagle-import") (part "custom-std_RES0402-RES"))
    )
    (comp (ref "R50")
      (value "1k")
      (footprint "eagle-import:0402R")
      (libsource (lib "eagle-import") (part "custom-std_RES0402-RES"))
    )
    (comp (ref "R51")
      (value "1k")
      (footprint "eagle-import:0402R")
      (libsource (lib "eagle-import") (part "custom-std_RES0402-RES"))
    )
    (comp (ref "R52")
      (value "2k")
      (footprint "eagle-import:0603R")
      (libsource (lib "eagle-import") (part "custom-std_RES0603-RES"))
    )
    (comp (ref "R53")
      (value "2k")
      (footprint "eagle-import:0603R")
      (libsource (lib "eagle-import") (part "custom-std_RES0603-RES"))
    )
    (comp (ref "R54")
      (value "100R")
      (footprint "eagle-import:0603R")
      (libsource (lib "eagle-import") (part "custom-std_RES0603-RES"))
    )
    (comp (ref "R55")
      (value "2k")
      (footprint "eagle-import:0603R")
      (libsource (lib "eagle-import") (part "custom-std_RES0603-RES"))
    )
    (comp (ref "R56")
      (value "1k")
      (footprint "eagle-import:0603R")
      (libsource (lib "eagle-import") (part "custom-std_RES0603-RES"))
    )
    (comp (ref "U3")
      (value "AD8331")
      (footprint "eagle-import:QSOP20")
      (fields (field (name "MPN") "AD8331ARQZ") (field (name "OC_DIGIKEY") "AD8331ARQZ-R7CT-ND"))
      (libsource (lib "eagle-import") (part "AD8331"))
    )
    (comp (ref "U4")
      (value "AD9215BRUZ")
      (footprint "eagle-import:TSSOP28")
      (fields (field (name "MPN") "AD9215BRUZ-105") (field (name "OC_DIGIKEY") "AD9215BRUZ-105-ND"))
      (libsource (lib "eagle-import") (part "AD9215BRUZ"))
    )
    (comp (ref "U10")
      (value "LP3985IM5-3.0")
      (footprint "eagle-import:SOT23-5")
      (fields
        (field (name "MPN") "LP3985IM5X-3.0/NOPB")
        (field (name "OC_DIGIKEY") "LP3985IM5X-3.0/NOPBCT-ND")
      )
      (libsource (lib "eagle-import") (part "V_REG_LDOSMD"))
    )
    (comp (ref "C34")
      (value "22u")
      (footprint "eagle-import:0805")
      (libsource (lib "eagle-import") (part "custom-std_CAP0805"))
    )
    (comp (ref "C35")
      (value "22u")
      (footprint "eagle-import:0805")
      (libsource (lib "eagle-import") (part "custom-std_CAP0805"))
    )
    (comp (ref "C36")
      (value "22u")
      (footprint "eagle-import:0805")
      (libsource (lib "eagle-import") (part "custom-std_CAP0805"))
    )
    (comp (ref "C38")
      (value "2u2")
      (footprint "eagle-import:0603C")
      (libsource (lib "eagle-import") (part "custom-std_CAP0603-CAP"))
    )
    (comp (ref "C39")
      (value "2u2")
      (footprint "eagle-import:0603C")
      (libsource (lib "eagle-import") (part "custom-std_CAP0603-CAP"))
    )
    (comp (ref "FID1")
      (value "FIDUCIAL1.5X3")
      (footprint "eagle-import:FIDUCIAL-1.5X3")
      (libsource (lib "eagle-import") (part "FIDUCIAL1.5X3"))
    )
    (comp (ref "FID2")
      (value "FIDUCIAL1.5X3")
      (footprint "eagle-import:FIDUCIAL-1.5X3")
      (libsource (lib "eagle-import") (part "FIDUCIAL1.5X3"))
    )
    (comp (ref "FID3")
      (value "FIDUCIAL1.5X3")
      (footprint "eagle-import:FIDUCIAL-1.5X3")
      (libsource (lib "eagle-import") (part "FIDUCIAL1.5X3"))
    )
    (comp (ref "FID4")
      (value "FIDUCIAL1.5X3")
      (footprint "eagle-import:FIDUCIAL-1.5X3")
      (libsource (lib "eagle-import") (part "FIDUCIAL1.5X3"))
    )
    (comp (ref "FID5")
      (value "FIDUCIAL1.5X3")
      (footprint "eagle-import:FIDUCIAL-1.5X3")
      (libsource (lib "eagle-import") (part "FIDUCIAL1.5X3"))
    )
    (comp (ref "FID6")
      (value "FIDUCIAL1.5X3")
      (footprint "eagle-import:FIDUCIAL-1.5X3")
      (libsource (lib "eagle-import") (part "FIDUCIAL1.5X3"))
    )
    (comp (ref "H1")
      (value "MOUNT-PAD-ROUND2.8")
      (footprint "eagle-import:2,8-PAD")
      (libsource (lib "eagle-import") (part "MOUNT-PAD-ROUND2.8"))
    )
    (comp (ref "H2")
      (value "MOUNT-PAD-ROUND2.8")
      (footprint "eagle-import:2,8-PAD")
      (libsource (lib "eagle-import") (part "MOUNT-PAD-ROUND2.8"))
    )
    (comp (ref "H3")
      (value "MOUNT-PAD-ROUND2.8")
      (footprint "eagle-import:2,8-PAD")
      (libsource (lib "eagle-import") (part "MOUNT-PAD-ROUND2.8"))
    )
    (comp (ref "H4")
      (value "MOUNT-PAD-ROUND2.8")
      (footprint "eagle-import:2,8-PAD")
      (libsource (lib "eagle-import") (part "MOUNT-PAD-ROUND2.8"))
    )
    (comp (ref "L2")
      (value "3.3uH")
      (footprint "eagle-import:VLS3015")
      (fields (field (name "OC_DIGIKEY") "445-6677-1-ND"))
      (libsource (lib "eagle-import") (part "L_VLS3015"))
    )
    (comp (ref "L3")
      (value "3.3uH")
      (footprint "eagle-import:VLS3015")
      (fields (field (name "MPN") "VLS3015ET-3R3M") (field (name "OC_DIGIKEY") "445-6677-1-ND"))
      (libsource (lib "eagle-import") (part "L_VLS3015"))
    )
    (comp (ref "MFID1")
      (value "FIDUCIALUFIDUCIAL")
      (footprint "eagle-import:MICRO-FIDUCIAL")
      (libsource (lib "eagle-import") (part "FIDUCIALUFIDUCIAL"))
    )
    (comp (ref "MFID2")
      (value "FIDUCIALUFIDUCIAL")
      (footprint "eagle-import:MICRO-FIDUCIAL")
      (libsource (lib "eagle-import") (part "FIDUCIALUFIDUCIAL"))
    )
    (comp (ref "MFID3")
      (value "FIDUCIALUFIDUCIAL")
      (footprint "eagle-import:MICRO-FIDUCIAL")
      (libsource (lib "eagle-import") (part "FIDUCIALUFIDUCIAL"))
    )
    (comp (ref "MFID4")
      (value "FIDUCIALUFIDUCIAL")
      (footprint "eagle-import:MICRO-FIDUCIAL")
      (libsource (lib "eagle-import") (part "FIDUCIALUFIDUCIAL"))
    )
    (comp (ref "R24")
      (value "1k5")
      (footprint "eagle-import:0402R")
      (libsource (lib "eagle-import") (part "custom-std_RES0402-RES"))
    )
    (comp (ref "R25")
      (value "6k81")
      (footprint "eagle-import:0402R")
      (libsource (lib "eagle-import") (part "custom-std_RES0402-RES"))
    )
    (comp (ref "R26")
      (value "1k5")
      (footprint "eagle-import:0402R")
      (libsource (lib "eagle-import") (part "custom-std_RES0402-RES"))
    )
    (comp (ref "R30")
      (value "1k5")
      (footprint "eagle-import:0402R")
      (libsource (lib "eagle-import") (part "custom-std_RES0402-RES"))
    )
    (comp (ref "U5")
      (value "LTC3419EMS")
      (footprint "eagle-import:MSOP10")
      (fields (field (name "MPN") "LTC3419EMS#PBF") (field (name "OC_DIGIKEY") "LTC3419EMS#PBF-ND"))
      (libsource (lib "eagle-import") (part "LTC3419MSE"))
    )
    (comp (ref "U7")
      (value "TC1262-3.3VDBTR")
      (footprint "eagle-import:SOT223")
      (fields (field (name "MPN") "TC1262-3.3VDBTR") (field (name "OC_DIGIKEY") "TC1262-3.3VDBCT-ND"))
      (libsource (lib "eagle-import") (part "V_REG_MIC2920"))
    )
    (comp (ref "C20")
      (value "100n")
      (footprint "eagle-import:0402C")
      (libsource (lib "eagle-import") (part "CAP0402-CAP"))
    )
    (comp (ref "C22")
      (value "100n")
      (footprint "eagle-import:0402C")
      (libsource (lib "eagle-import") (part "CAP0402-CAP"))
    )
    (comp (ref "C23")
      (value "100n")
      (footprint "eagle-import:0402C")
      (libsource (lib "eagle-import") (part "CAP0402-CAP"))
    )
    (comp (ref "C24")
      (value "100n")
      (footprint "eagle-import:0402C")
      (libsource (lib "eagle-import") (part "CAP0402-CAP"))
    )
    (comp (ref "C25")
      (value "100n")
      (footprint "eagle-import:0402C")
      (libsource (lib "eagle-import") (part "CAP0402-CAP"))
    )
    (comp (ref "C26")
      (value "2u2")
      (footprint "eagle-import:0603C")
      (libsource (lib "eagle-import") (part "CAP0603-CAP"))
    )
    (comp (ref "C27")
      (value "2u2")
      (footprint "eagle-import:0603C")
      (libsource (lib "eagle-import") (part "CAP0603-CAP"))
    )
    (comp (ref "C28")
      (value "100n")
      (footprint "eagle-import:0402C")
      (libsource (lib "eagle-import") (part "CAP0402-CAP"))
    )
    (comp (ref "C29")
      (value "100n")
      (footprint "eagle-import:0402C")
      (libsource (lib "eagle-import") (part "CAP0402-CAP"))
    )
    (comp (ref "C30")
      (value "100n")
      (footprint "eagle-import:0402C")
      (libsource (lib "eagle-import") (part "CAP0402-CAP"))
    )
    (comp (ref "C31")
      (value "100n")
      (footprint "eagle-import:0402C")
      (libsource (lib "eagle-import") (part "CAP0402-CAP"))
    )
    (comp (ref "C32")
      (value "100n")
      (footprint "eagle-import:0402C")
      (libsource (lib "eagle-import") (part "CAP0402-CAP"))
    )
    (comp (ref "C49")
      (value "100n")
      (footprint "eagle-import:0603C")
      (libsource (lib "eagle-import") (part "CAP0603-CAP"))
    )
    (comp (ref "C52")
      (value "100n")
      (footprint "eagle-import:0402C")
      (libsource (lib "eagle-import") (part "custom-std_CAP0402-CAP"))
    )
    (comp (ref "C53")
      (value "100n")
      (footprint "eagle-import:0402C")
      (libsource (lib "eagle-import") (part "custom-std_CAP0402-CAP"))
    )
    (comp (ref "C54")
      (value "100n")
      (footprint "eagle-import:0402C")
      (libsource (lib "eagle-import") (part "custom-std_CAP0402-CAP"))
    )
    (comp (ref "C55")
      (value "100n")
      (footprint "eagle-import:0402C")
      (libsource (lib "eagle-import") (part "custom-std_CAP0402-CAP"))
    )
    (comp (ref "C56")
      (value "100n")
      (footprint "eagle-import:0402C")
      (libsource (lib "eagle-import") (part "custom-std_CAP0402-CAP"))
    )
    (comp (ref "C57")
      (value "100n")
      (footprint "eagle-import:0402C")
      (libsource (lib "eagle-import") (part "custom-std_CAP0402-CAP"))
    )
    (comp (ref "C58")
      (value "100n")
      (footprint "eagle-import:0402C")
      (libsource (lib "eagle-import") (part "custom-std_CAP0402-CAP"))
    )
    (comp (ref "C59")
      (value "100n")
      (footprint "eagle-import:0402C")
      (libsource (lib "eagle-import") (part "custom-std_CAP0402-CAP"))
    )
    (comp (ref "C60")
      (value "1u")
      (footprint "eagle-import:0603C")
      (libsource (lib "eagle-import") (part "custom-std_CAP0603-CAP"))
    )
    (comp (ref "C61")
      (value "1u")
      (footprint "eagle-import:0603C")
      (libsource (lib "eagle-import") (part "custom-std_CAP0603-CAP"))
    )
    (comp (ref "C62")
      (value "1u")
      (footprint "eagle-import:0603C")
      (libsource (lib "eagle-import") (part "custom-std_CAP0603-CAP"))
    )
    (comp (ref "J4")
      (value "CON_HEADER_PRG_XILINX_JTAG6")
      (footprint "eagle-import:HEADER_PRG_1X06")
      (libsource (lib "eagle-import") (part "CON_HEADER_PRG_XILINX_JTAG6"))
    )
    (comp (ref "R3")
      (value "1k")
      (footprint "eagle-import:0603R")
      (libsource (lib "eagle-import") (part "RES0603-RES"))
    )
    (comp (ref "R4")
      (value "DNM")
      (footprint "eagle-import:0603R")
      (libsource (lib "eagle-import") (part "RES0603-RES"))
    )
    (comp (ref "R5")
      (value "1R")
      (footprint "eagle-import:0402R")
      (libsource (lib "eagle-import") (part "RES0402-RES"))
    )
    (comp (ref "R6")
      (value "1R")
      (footprint "eagle-import:0402R")
      (libsource (lib "eagle-import") (part "RES0402-RES"))
    )
    (comp (ref "R7")
      (value "1k")
      (footprint "eagle-import:0603R")
      (libsource (lib "eagle-import") (part "RES0603-RES"))
    )
    (comp (ref "R8")
      (value "DNM")
      (footprint "eagle-import:0603R")
      (libsource (lib "eagle-import") (part "RES0603-RES"))
    )
    (comp (ref "R9")
      (value "10k")
      (footprint "eagle-import:0402R")
      (libsource (lib "eagle-import") (part "RES0402-RES"))
    )
    (comp (ref "R11")
      (value "10k")
      (footprint "eagle-import:0402R")
      (libsource (lib "eagle-import") (part "RES0402-RES"))
    )
    (comp (ref "R12")
      (value "10k")
      (footprint "eagle-import:0402R")
      (libsource (lib "eagle-import") (part "RES0402-RES"))
    )
    (comp (ref "R22")
      (value "DNM")
      (footprint "eagle-import:0603R")
      (libsource (lib "eagle-import") (part "RES0603-RES"))
    )
    (comp (ref "R69")
      (value "10k")
      (footprint "eagle-import:0402R")
      (libsource (lib "eagle-import") (part "RES0402-RES"))
    )
    (comp (ref "R70")
      (value "DNM")
      (footprint "eagle-import:0402R")
      (libsource (lib "eagle-import") (part "RES0402-RES"))
    )
    (comp (ref "R71")
      (value "DNM")
      (footprint "eagle-import:0402R")
      (libsource (lib "eagle-import") (part "RES0402-RES"))
    )
    (comp (ref "U9")
      (value "SPI_FLASH-X25XXSMD1")
      (footprint "eagle-import:SO08-EIAJ")
      (libsource (lib "eagle-import") (part "SPI_FLASH-X25XXSMD1"))
    )
    (comp (ref "C63")
      (value "1u")
      (footprint "eagle-import:0603C")
      (libsource (lib "eagle-import") (part "custom-std_CAP0603-CAP"))
    )
    (comp (ref "C64")
      (value "100n")
      (footprint "eagle-import:0402C")
      (libsource (lib "eagle-import") (part "custom-std_CAP0402-CAP"))
    )
    (comp (ref "C65")
      (value "100n")
      (footprint "eagle-import:0402C")
      (libsource (lib "eagle-import") (part "custom-std_CAP0402-CAP"))
    )
    (comp (ref "C66")
      (value "100n")
      (footprint "eagle-import:0402C")
      (libsource (lib "eagle-import") (part "custom-std_CAP0402-CAP"))
    )
    (comp (ref "C101")
      (value "220n")
      (footprint "eagle-import:0402C")
      (libsource (lib "eagle-import") (part "custom-std_CAP0402-CAP"))
    )
    (comp (ref "C102")
      (value "220n")
      (footprint "eagle-import:0402C")
      (libsource (lib "eagle-import") (part "custom-std_CAP0402-CAP"))
    )
    (comp (ref "J1")
      (value "SHROUD_2X10-SHROUDED")
      (footprint "eagle-import:PINSHRD_PTH_2X10")
      (libsource (lib "eagle-import") (part "SHROUD_2X10-SHROUDED"))
    )
    (comp (ref "J6")
      (value "SHROUD_2X4SHROUD")
      (footprint "eagle-import:PINSHRD_PTH_2X04")
      (libsource (lib "eagle-import") (part "SHROUD_2X4SHROUD"))
    )
    (comp (ref "JP5")
      (value "PINHD-1X3")
      (footprint "eagle-import:1X03")
      (libsource (lib "eagle-import") (part "pinhead_PINHD-1X3"))
    )
    (comp (ref "JP8")
      (value "PINHD-1X3")
      (footprint "eagle-import:1X03")
      (libsource (lib "eagle-import") (part "PINHD-1X3"))
    )
    (comp (ref "JP9")
      (value "PINHD-1X10")
      (footprint "eagle-import:1X10-BIG")
      (libsource (lib "eagle-import") (part "PINHD-1X10"))
    )
    (comp (ref "JP10")
      (value "PINHD-1X3")
      (footprint "eagle-import:1X03")
      (libsource (lib "eagle-import") (part "PINHD-1X3"))
    )
    (comp (ref "JP11")
      (value "PINHD-1X3")
      (footprint "eagle-import:1X03")
      (libsource (lib "eagle-import") (part "PINHD-1X3"))
    )
    (comp (ref "JP18")
      (value "PINHD-1X1")
      (footprint "eagle-import:1X01")
      (libsource (lib "eagle-import") (part "PINHD-1X1"))
    )
    (comp (ref "R35")
      (value "39R")
      (footprint "eagle-import:0603R")
      (libsource (lib "eagle-import") (part "custom-std_RES0603-RES"))
    )
    (comp (ref "R36")
      (value "39R")
      (footprint "eagle-import:0603R")
      (libsource (lib "eagle-import") (part "custom-std_RES0603-RES"))
    )
    (comp (ref "R37")
      (value "1R")
      (footprint "eagle-import:0603R")
      (libsource (lib "eagle-import") (part "custom-std_RES0603-RES"))
    )
    (comp (ref "R43")
      (value "10k")
      (footprint "eagle-import:0603R")
      (libsource (lib "eagle-import") (part "custom-std_RES0603-RES"))
    )
    (comp (ref "R59")
      (value "1R")
      (footprint "eagle-import:0603R")
      (libsource (lib "eagle-import") (part "custom-std_RES0603-RES"))
    )
    (comp (ref "R60")
      (value "DNM")
      (footprint "eagle-import:0603R")
      (libsource (lib "eagle-import") (part "custom-std_RES0603-RES"))
    )
    (comp (ref "R61")
      (value "10k")
      (footprint "eagle-import:0603R")
      (libsource (lib "eagle-import") (part "custom-std_RES0603-RES"))
    )
    (comp (ref "R65")
      (value "10k")
      (footprint "eagle-import:0603R")
      (libsource (lib "eagle-import") (part "custom-std_RES0603-RES"))
    )
    (comp (ref "R78")
      (value "1R")
      (footprint "eagle-import:0603R")
      (libsource (lib "eagle-import") (part "custom-std_RES0603-RES"))
    )
    (comp (ref "SJ6")
      (value "SOLDERJUMPERNC")
      (footprint "eagle-import:SJ_2S")
      (libsource (lib "eagle-import") (part "SOLDERJUMPERNC"))
    )
    (comp (ref "T4")
      (value "IRLML2502")
      (footprint "eagle-import:SOT-23")
      (fields (field (name "MPN") "IRLML2502TRPBF") (field (name "OC_DIGIKEY") "IRLML2502PBFCT-ND"))
      (libsource (lib "eagle-import") (part "NMOSSOT23"))
    )
    (comp (ref "U8")
      (value "IRF7807ZTRPBF")
      (footprint "eagle-import:SO08")
      (libsource (lib "eagle-import") (part "MOSFET-NCHANNEL-SOIC8"))
    )
    (comp (ref "X2")
      (value "SMA-NOSILK")
      (footprint "eagle-import:J502-ND-142-0711-821_826-NOSILK")
      (libsource (lib "eagle-import") (part "SMA-NOSILK"))
    )
    (comp (ref "X4")
      (value "SMA-NOSILK")
      (footprint "eagle-import:J502-ND-142-0711-821_826-NOSILK")
      (libsource (lib "eagle-import") (part "SMA-NOSILK"))
    )
    (comp (ref "C1")
      (value "DNM")
      (footprint "eagle-import:0402C")
      (libsource (lib "eagle-import") (part "CAP0402-CAP"))
    )
    (comp (ref "C2")
      (value "DNM")
      (footprint "eagle-import:0402C")
      (libsource (lib "eagle-import") (part "CAP0402-CAP"))
    )
    (comp (ref "C3")
      (value "4u7")
      (footprint "eagle-import:0603C")
      (libsource (lib "eagle-import") (part "CAP0603-CAP"))
    )
    (comp (ref "C4")
      (value "100n")
      (footprint "eagle-import:0402C")
      (libsource (lib "eagle-import") (part "CAP0402-CAP"))
    )
    (comp (ref "C5")
      (value "2u2")
      (footprint "eagle-import:0603C")
      (libsource (lib "eagle-import") (part "CAP0603-CAP"))
    )
    (comp (ref "C6")
      (value "4u7")
      (footprint "eagle-import:0603C")
      (libsource (lib "eagle-import") (part "CAP0603-CAP"))
    )
    (comp (ref "C7")
      (value "4u7")
      (footprint "eagle-import:0603C")
      (libsource (lib "eagle-import") (part "CAP0603-CAP"))
    )
    (comp (ref "C8")
      (value "100n")
      (footprint "eagle-import:0402C")
      (libsource (lib "eagle-import") (part "CAP0402-CAP"))
    )
    (comp (ref "C9")
      (value "100n")
      (footprint "eagle-import:0402C")
      (libsource (lib "eagle-import") (part "CAP0402-CAP"))
    )
    (comp (ref "C10")
      (value "100n")
      (footprint "eagle-import:0402C")
      (libsource (lib "eagle-import") (part "CAP0402-CAP"))
    )
    (comp (ref "C11")
      (value "100n")
      (footprint "eagle-import:0402C")
      (libsource (lib "eagle-import") (part "CAP0402-CAP"))
    )
    (comp (ref "C12")
      (value "100n")
      (footprint "eagle-import:0402C")
      (libsource (lib "eagle-import") (part "CAP0402-CAP"))
    )
    (comp (ref "C13")
      (value "100n")
      (footprint "eagle-import:0402C")
      (libsource (lib "eagle-import") (part "CAP0402-CAP"))
    )
    (comp (ref "C14")
      (value "100n")
      (footprint "eagle-import:0402C")
      (libsource (lib "eagle-import") (part "CAP0402-CAP"))
    )
    (comp (ref "C15")
      (value "100n")
      (footprint "eagle-import:0402C")
      (libsource (lib "eagle-import") (part "CAP0402-CAP"))
    )
    (comp (ref "C16")
      (value "100n")
      (footprint "eagle-import:0402C")
      (libsource (lib "eagle-import") (part "CAP0402-CAP"))
    )
    (comp (ref "C17")
      (value "100n")
      (footprint "eagle-import:0402C")
      (libsource (lib "eagle-import") (part "CAP0402-CAP"))
    )
    (comp (ref "C18")
      (value "100n")
      (footprint "eagle-import:0402C")
      (libsource (lib "eagle-import") (part "CAP0402-CAP"))
    )
    (comp (ref "C19")
      (value "100n")
      (footprint "eagle-import:0402C")
      (libsource (lib "eagle-import") (part "CAP0402-CAP"))
    )
    (comp (ref "C21")
      (value "100n")
      (footprint "eagle-import:0402C")
      (libsource (lib "eagle-import") (part "CAP0402-CAP"))
    )
    (comp (ref "C33")
      (value "10pF")
      (footprint "eagle-import:0603C")
      (libsource (lib "eagle-import") (part "CAP0603-CAP"))
    )
    (comp (ref "C50")
      (value "18pF")
      (footprint "eagle-import:0402C")
      (libsource (lib "eagle-import") (part "CAP0402-CAP"))
    )
    (comp (ref "C51")
      (value "18pF")
      (footprint "eagle-import:0402C")
      (libsource (lib "eagle-import") (part "CAP0402-CAP"))
    )
    (comp (ref "C123")
      (value "100n")
      (footprint "eagle-import:0402C")
      (libsource (lib "eagle-import") (part "CAP0402-CAP"))
    )
    (comp (ref "D2")
      (value "LED0603")
      (footprint "eagle-import:LED-0603")
      (libsource (lib "eagle-import") (part "LED0603"))
    )
    (comp (ref "D9")
      (value "LED0603")
      (footprint "eagle-import:LED-0603")
      (libsource (lib "eagle-import") (part "LED0603"))
    )
    (comp (ref "J7")
      (value "SHROUD_2X4EDGE")
      (footprint "eagle-import:PINSHRD_EDGE_2X04.PAC")
      (libsource (lib "eagle-import") (part "SHROUD_2X4EDGE"))
    )
    (comp (ref "JP1")
      (value "PINHD-1X4")
      (footprint "eagle-import:1X04")
      (libsource (lib "eagle-import") (part "PINHD-1X4"))
    )
    (comp (ref "L1")
      (value "10uH/100mA")
      (footprint "eagle-import:0603")
      (libsource (lib "eagle-import") (part "INDUCTOR0603"))
    )
    (comp (ref "Q1")
      (value "XTAL-4ABM8G")
      (footprint "eagle-import:NX3225")
      (fields (field (name "MPN") "ABM8G-12.000MHZ-4Y-T3") (field (name "OC_DIGIKEY") "535-10901-1-ND"))
      (libsource (lib "eagle-import") (part "XTAL-4ABM8G"))
    )
    (comp (ref "R1")
      (value "1R")
      (footprint "eagle-import:0402R")
      (libsource (lib "eagle-import") (part "RES0402-RES"))
    )
    (comp (ref "R2")
      (value "330R")
      (footprint "eagle-import:0402R")
      (libsource (lib "eagle-import") (part "RES0402-RES"))
    )
    (comp (ref "R10")
      (value "330R")
      (footprint "eagle-import:0402R")
      (libsource (lib "eagle-import") (part "RES0402-RES"))
    )
    (comp (ref "R14")
      (value "1R")
      (footprint "eagle-import:0402R")
      (libsource (lib "eagle-import") (part "RES0402-RES"))
    )
    (comp (ref "R15")
      (value "1R")
      (footprint "eagle-import:0603R")
      (libsource (lib "eagle-import") (part "RES0603-RES"))
    )
    (comp (ref "R27")
      (value "39R")
      (footprint "eagle-import:0603R")
      (libsource (lib "eagle-import") (part "RES0603-RES"))
    )
    (comp (ref "R28")
      (value "39R")
      (footprint "eagle-import:0603R")
      (libsource (lib "eagle-import") (part "RES0603-RES"))
    )
    (comp (ref "R29")
      (value "6k81")
      (footprint "eagle-import:0402R")
      (libsource (lib "eagle-import") (part "RES0402-RES"))
    )
    (comp (ref "R57")
      (value "1k")
      (footprint "eagle-import:0603R")
      (libsource (lib "eagle-import") (part "RES0603-RES"))
    )
    (comp (ref "R58")
      (value "1k")
      (footprint "eagle-import:0603R")
      (libsource (lib "eagle-import") (part "RES0603-RES"))
    )
    (comp (ref "R62")
      (value "1R")
      (footprint "eagle-import:0603R")
      (libsource (lib "eagle-import") (part "RES0603-RES"))
    )
    (comp (ref "R63")
      (value "1k")
      (footprint "eagle-import:0603R")
      (libsource (lib "eagle-import") (part "RES0603-RES"))
    )
    (comp (ref "R64")
      (value "10k")
      (footprint "eagle-import:0603R")
      (libsource (lib "eagle-import") (part "RES0603-RES"))
    )
    (comp (ref "U1")
      (value "ATSAM3U2CA-AU")
      (footprint "eagle-import:QFP50P1600X1600X160-100N")
      (fields (field (name "OC_DIGIKEY") "ATSAM3U2CA-AU-ND"))
      (libsource (lib "eagle-import") (part "ATSAM3U2CA-AU"))
    )
  )
  (nets
    (net (code "1") (name "+3V3") (class "Default")
      (node (ref "C13") (pin "1") (pinfunction "1_1") (pintype "passive"))
      (node (ref "C14") (pin "1") (pinfunction "1_1") (pintype "passive"))
      (node (ref "C15") (pin "1") (pinfunction "1_1") (pintype "passive"))
      (node (ref "C16") (pin "1") (pinfunction "1_1") (pintype "passive"))
      (node (ref "C17") (pin "1") (pinfunction "1_1") (pintype "passive"))
      (node (ref "C18") (pin "1") (pinfunction "1_1") (pintype "passive"))
      (node (ref "C21") (pin "1") (pinfunction "1_1") (pintype "passive"))
      (node (ref "C38") (pin "1") (pinfunction "1_1") (pintype "passive"))
      (node (ref "C6") (pin "1") (pinfunction "1_1") (pintype "passive"))
      (node (ref "J3") (pin "1") (pinfunction "1_1") (pintype "passive"))
      (node (ref "J3") (pin "2") (pinfunction "2_2") (pintype "passive"))
      (node (ref "JP1") (pin "4") (pinfunction "4_4") (pintype "passive"))
      (node (ref "JP4") (pin "2") (pinfunction "2_2") (pintype "passive"))
      (node (ref "L1") (pin "1") (pinfunction "1_1") (pintype "passive"))
      (node (ref "R17") (pin "2") (pinfunction "2_2") (pintype "passive"))
      (node (ref "R18") (pin "2") (pinfunction "2_2") (pintype "passive"))
      (node (ref "R19") (pin "2") (pinfunction "2_2") (pintype "passive"))
      (node (ref "R20") (pin "2") (pinfunction "2_2") (pintype "passive"))
      (node (ref "R21") (pin "2") (pinfunction "2_2") (pintype "passive"))
      (node (ref "R62") (pin "1") (pinfunction "1_1") (pintype "passive"))
      (node (ref "R64") (pin "2") (pinfunction "2_2") (pintype "passive"))
      (node (ref "U1") (pin "1") (pinfunction "VDDANA_1") (pintype "power_in"))
      (node (ref "U1") (pin "2") (pinfunction "ADVREF_2") (pintype "passive"))
      (node (ref "U1") (pin "22") (pinfunction "VDDIO_2_22") (pintype "power_in"))
      (node (ref "U1") (pin "36") (pinfunction "VDDIO_3_36") (pintype "power_in"))
      (node (ref "U1") (pin "4") (pinfunction "AD12BVREF_4") (pintype "passive"))
      (node (ref "U1") (pin "45") (pinfunction "VDDBU_45") (pintype "power_in"))
      (node (ref "U1") (pin "53") (pinfunction "VDDIN_53") (pintype "power_in"))
      (node (ref "U1") (pin "60") (pinfunction "VDDIO_4_60") (pintype "power_in"))
      (node (ref "U1") (pin "88") (pinfunction "VDDIO_88") (pintype "power_in"))
      (node (ref "U7") (pin "3") (pinfunction "OUT_3") (pintype "output"))
    )
    (net (code "2") (name "+5VCLEAN") (class "Default")
      (node (ref "C40") (pin "1") (pinfunction "1_1") (pintype "passive"))
      (node (ref "C41") (pin "1") (pinfunction "1_1") (pintype "passive"))
      (node (ref "L5") (pin "2") (pinfunction "2_2") (pintype "passive"))
      (node (ref "L7") (pin "1") (pinfunction "1_1") (pintype "passive"))
      (node (ref "L8") (pin "1") (pinfunction "1_1") (pintype "passive"))
    )
    (net (code "7") (name "ADC_CLK") (class "Default")
      (node (ref "R54") (pin "2") (pinfunction "2_2") (pintype "passive"))
      (node (ref "U2") (pin "P55") (pinfunction "IO_L30N_GCLK0_USERCCLK_2_P55") (pintype "bidirectional"))
      (node (ref "U2") (pin "P56") (pinfunction "IO_L30P_GCLK1_D13_2_P56") (pintype "bidirectional"))
      (node (ref "U4") (pin "13") (pinfunction "CLK_13") (pintype "bidirectional"))
    )
    (net (code "8") (name "ADC_D0") (class "Default")
      (node (ref "U2") (pin "P59") (pinfunction "IO_L13N_D10_2_P59") (pintype "bidirectional"))
      (node (ref "U4") (pin "17") (pinfunction "D0_17") (pintype "bidirectional"))
    )
    (net (code "9") (name "ADC_D1") (class "Default")
      (node (ref "U2") (pin "P58") (pinfunction "IO_L14P_D11_2_P58") (pintype "bidirectional"))
      (node (ref "U4") (pin "18") (pinfunction "D1_18") (pintype "bidirectional"))
    )
    (net (code "10") (name "ADC_D2") (class "Default")
      (node (ref "U2") (pin "P57") (pinfunction "IO_L14N_D12_2_P57") (pintype "bidirectional"))
      (node (ref "U4") (pin "19") (pinfunction "D2_19") (pintype "bidirectional"))
    )
    (net (code "11") (name "ADC_D3") (class "Default")
      (node (ref "U2") (pin "P48") (pinfunction "IO_L48P_D7_2_P48") (pintype "bidirectional"))
      (node (ref "U4") (pin "20") (pinfunction "D3_20") (pintype "bidirectional"))
    )
    (net (code "12") (name "ADC_D4") (class "Default")
      (node (ref "U2") (pin "P47") (pinfunction "IO_L48N_RDWR_B_VREF_2_P47") (pintype "bidirectional"))
      (node (ref "U4") (pin "21") (pinfunction "D4_21") (pintype "bidirectional"))
    )
    (net (code "13") (name "ADC_D5") (class "Default")
      (node (ref "U2") (pin "P46") (pinfunction "IO_L49P_D3_2_P46") (pintype "bidirectional"))
      (node (ref "U4") (pin "22") (pinfunction "D5_22") (pintype "bidirectional"))
    )
    (net (code "14") (name "ADC_D6") (class "Default")
      (node (ref "U2") (pin "P45") (pinfunction "IO_L49N_D4_2_P45") (pintype "bidirectional"))
      (node (ref "U4") (pin "25") (pinfunction "D6_25") (pintype "bidirectional"))
    )
    (net (code "15") (name "ADC_D7") (class "Default")
      (node (ref "U2") (pin "P44") (pinfunction "IO_L62P_D5_2_P44") (pintype "bidirectional"))
      (node (ref "U4") (pin "26") (pinfunction "D7_26") (pintype "bidirectional"))
    )
    (net (code "16") (name "ADC_D8") (class "Default")
      (node (ref "U2") (pin "P43") (pinfunction "IO_L62N_D6_2_P43") (pintype "bidirectional"))
      (node (ref "U4") (pin "27") (pinfunction "D8_27") (pintype "bidirectional"))
    )
    (net (code "17") (name "ADC_D9") (class "Default")
      (node (ref "U2") (pin "P41") (pinfunction "IO_L64P_D8_2_P41") (pintype "bidirectional"))
      (node (ref "U4") (pin "28") (pinfunction "D9_28") (pintype "bidirectional"))
    )
    (net (code "18") (name "ADC_OR") (class "Default")
      (node (ref "U2") (pin "P40") (pinfunction "IO_L64N_D9_2_P40") (pintype "bidirectional"))
      (node (ref "U4") (pin "1") (pinfunction "OR_1") (pintype "bidirectional"))
    )
    (net (code "19") (name "ADC_VCC") (class "Default")
      (node (ref "C100") (pin "1") (pinfunction "1_1") (pintype "passive"))
      (node (ref "C111") (pin "2") (pinfunction "2_2") (pintype "passive"))
      (node (ref "C113") (pin "2") (pinfunction "2_2") (pintype "passive"))
      (node (ref "C97") (pin "1") (pinfunction "1_1") (pintype "passive"))
      (node (ref "C98") (pin "1") (pinfunction "1_1") (pintype "passive"))
      (node (ref "C99") (pin "1") (pinfunction "1_1") (pintype "passive"))
      (node (ref "R49") (pin "2") (pinfunction "2_2") (pintype "passive"))
      (node (ref "R51") (pin "1") (pinfunction "1_1") (pintype "passive"))
      (node (ref "R55") (pin "2") (pinfunction "2_2") (pintype "passive"))
      (node (ref "U10") (pin "5") (pinfunction "OUT_5") (pintype "passive"))
      (node (ref "U4") (pin "12") (pinfunction "AVDD_12") (pintype "bidirectional"))
      (node (ref "U4") (pin "7") (pinfunction "AVDD_7") (pintype "bidirectional"))
    )
    (net (code "20") (name "ANIN") (class "Default")
      (node (ref "JP10") (pin "2") (pinfunction "2_2") (pintype "passive"))
      (node (ref "L11") (pin "1") (pinfunction "1_1") (pintype "passive"))
      (node (ref "X2") (pin "1") (pinfunction "1_1") (pintype "passive"))
    )
    (net (code "21") (name "CLK2") (class "Default")
      (node (ref "J7") (pin "5") (pinfunction "5_5") (pintype "passive"))
      (node (ref "U1") (pin "24") (pinfunction "PA25_24") (pintype "bidirectional"))
      (node (ref "U2") (pin "P131") (pinfunction "IO_L35N_GCLK16_0_P131") (pintype "bidirectional"))
    )
    (net (code "22") (name "D_N") (class "Default")
      (node (ref "J8") (pin "2") (pinfunction "DM_2") (pintype "bidirectional"))
      (node (ref "R27") (pin "2") (pinfunction "2_2") (pintype "passive"))
      (node (ref "U1") (pin "77") (pinfunction "DHSDM_77") (pintype "bidirectional"))
      (node (ref "U6") (pin "3") (pinfunction "IO2_3") (pintype "bidirectional"))
    )
    (net (code "23") (name "D_P") (class "Default")
      (node (ref "J8") (pin "3") (pinfunction "DP_3") (pintype "bidirectional"))
      (node (ref "R28") (pin "2") (pinfunction "2_2") (pintype "passive"))
      (node (ref "U1") (pin "76") (pinfunction "DHSDP_76") (pintype "bidirectional"))
      (node (ref "U6") (pin "2") (pinfunction "IO1_2") (pintype "bidirectional"))
    )
    (net (code "24") (name "ERASE") (class "Default")
      (node (ref "JP4") (pin "1") (pinfunction "1_1") (pintype "passive"))
      (node (ref "U1") (pin "43") (pinfunction "ERASE_43") (pintype "input"))
    )
    (net (code "25") (name "FPGA_DONE") (class "Default")
      (node (ref "R11") (pin "1") (pinfunction "1_1") (pintype "passive"))
      (node (ref "U1") (pin "39") (pinfunction "PA10/PGMD2_39") (pintype "bidirectional"))
      (node (ref "U2") (pin "P71") (pinfunction "DONE_2_P71") (pintype "bidirectional"))
    )
    (net (code "26") (name "FPGA_INITB") (class "Default")
      (node (ref "R69") (pin "2") (pinfunction "2_2") (pintype "passive"))
      (node (ref "U1") (pin "38") (pinfunction "PA9/PGMD1_38") (pintype "bidirectional"))
      (node (ref "U2") (pin "P39") (pinfunction "IO_L65P_INIT_B_2_P39") (pintype "bidirectional"))
    )
    (net (code "27") (name "FPGA_PROGRAM") (class "Default")
      (node (ref "R12") (pin "1") (pinfunction "1_1") (pintype "passive"))
      (node (ref "U1") (pin "37") (pinfunction "PA8/PGMD0_37") (pintype "bidirectional"))
      (node (ref "U2") (pin "P37") (pinfunction "PROGRAM_B_2_P37") (pintype "input"))
    )
    (net (code "28") (name "FSC_AX1") (class "Default")
      (node (ref "J6") (pin "7") (pinfunction "7_7") (pintype "passive"))
      (node (ref "U2") (pin "P98") (pinfunction "IO_L34P_1_P98") (pintype "bidirectional"))
    )
    (net (code "29") (name "FSC_AX2") (class "Default")
      (node (ref "J6") (pin "8") (pinfunction "8_8") (pintype "passive"))
      (node (ref "U2") (pin "P97") (pinfunction "IO_L34N_1_P97") (pintype "bidirectional"))
    )
    (net (code "30") (name "FSC_CLK") (class "Default")
      (node (ref "J6") (pin "5") (pinfunction "5_5") (pintype "passive"))
      (node (ref "U2") (pin "P100") (pinfunction "IO_L33P_1_P100") (pintype "bidirectional"))
    )
    (net (code "31") (name "FSC_IO") (class "Default")
      (node (ref "J6") (pin "6") (pinfunction "6_6") (pintype "passive"))
      (node (ref "R61") (pin "2") (pinfunction "2_2") (pintype "passive"))
      (node (ref "U2") (pin "P99") (pinfunction "IO_L33N_1_P99") (pintype "bidirectional"))
    )
    (net (code "32") (name "FSC_RST") (class "Default")
      (node (ref "J6") (pin "3") (pinfunction "3_3") (pintype "passive"))
      (node (ref "U2") (pin "P102") (pinfunction "IO_L32P_1_P102") (pintype "bidirectional"))
    )
    (net (code "33") (name "FSC_VPP") (class "Default")
      (node (ref "R60") (pin "2") (pinfunction "2_2") (pintype "passive"))
      (node (ref "U2") (pin "P101") (pinfunction "IO_L32N_1_P101") (pintype "bidirectional"))
    )
    (net (code "34") (name "GLITCHOUT") (class "Default")
      (node (ref "JP8") (pin "1") (pinfunction "1_1") (pintype "passive"))
      (node (ref "R37") (pin "2") (pinfunction "2_2") (pintype "passive"))
      (node (ref "U2") (pin "P66") (pinfunction "IO_L2N_CMPMOSI_2_P66") (pintype "bidirectional"))
    )
    (net (code "35") (name "GLITCHOUTLP") (class "Default")
      (node (ref "R78") (pin "2") (pinfunction "2_2") (pintype "passive"))
      (node (ref "U2") (pin "P67") (pinfunction "IO_L2P_CMPCLK_2_P67") (pintype "bidirectional"))
    )
    (net (code "36") (name "GND") (class "Default")
      (node (ref "C1") (pin "2") (pinfunction "2_2") (pintype "passive"))
      (node (ref "C10") (pin "2") (pinfunction "2_2") (pintype "passive"))
      (node (ref "C100") (pin "2") (pinfunction "2_2") (pintype "passive"))
      (node (ref "C101") (pin "2") (pinfunction "2_2") (pintype "passive"))
      (node (ref "C102") (pin "2") (pinfunction "2_2") (pintype "passive"))
      (node (ref "C11") (pin "2") (pinfunction "2_2") (pintype "passive"))
      (node (ref "C110") (pin "1") (pinfunction "1_1") (pintype "passive"))
      (node (ref "C111") (pin "1") (pinfunction "1_1") (pintype "passive"))
      (node (ref "C112") (pin "1") (pinfunction "1_1") (pintype "passive"))
      (node (ref "C113") (pin "1") (pinfunction "1_1") (pintype "passive"))
      (node (ref "C114") (pin "1") (pinfunction "1_1") (pintype "passive"))
      (node (ref "C12") (pin "2") (pinfunction "2_2") (pintype "passive"))
      (node (ref "C122") (pin "2") (pinfunction "2_2") (pintype "passive"))
      (node (ref "C123") (pin "2") (pinfunction "2_2") (pintype "passive"))
      (node (ref "C13") (pin "2") (pinfunction "2_2") (pintype "passive"))
      (node (ref "C14") (pin "2") (pinfunction "2_2") (pintype "passive"))
      (node (ref "C15") (pin "2") (pinfunction "2_2") (pintype "passive"))
      (node (ref "C16") (pin "2") (pinfunction "2_2") (pintype "passive"))
      (node (ref "C17") (pin "2") (pinfunction "2_2") (pintype "passive"))
      (node (ref "C18") (pin "2") (pinfunction "2_2") (pintype "passive"))
      (node (ref "C19") (pin "2") (pinfunction "2_2") (pintype "passive"))
      (node (ref "C2") (pin "2") (pinfunction "2_2") (pintype "passive"))
      (node (ref "C20") (pin "2") (pinfunction "2_2") (pintype "passive"))
      (node (ref "C21") (pin "2") (pinfunction "2_2") (pintype "passive"))
      (node (ref "C22") (pin "2") (pinfunction "2_2") (pintype "passive"))
      (node (ref "C23") (pin "2") (pinfunction "2_2") (pintype "passive"))
      (node (ref "C24") (pin "2") (pinfunction "2_2") (pintype "passive"))
      (node (ref "C25") (pin "2") (pinfunction "2_2") (pintype "passive"))
      (node (ref "C26") (pin "2") (pinfunction "2_2") (pintype "passive"))
      (node (ref "C27") (pin "2") (pinfunction "2_2") (pintype "passive"))
      (node (ref "C28") (pin "2") (pinfunction "2_2") (pintype "passive"))
      (node (ref "C29") (pin "2") (pinfunction "2_2") (pintype "passive"))
      (node (ref "C3") (pin "1") (pinfunction "1_1") (pintype "passive"))
      (node (ref "C30") (pin "2") (pinfunction "2_2") (pintype "passive"))
      (node (ref "C31") (pin "2") (pinfunction "2_2") (pintype "passive"))
      (node (ref "C32") (pin "2") (pinfunction "2_2") (pintype "passive"))
      (node (ref "C33") (pin "2") (pinfunction "2_2") (pintype "passive"))
      (node (ref "C34") (pin "2") (pinfunction "2_2") (pintype "passive"))
      (node (ref "C35") (pin "2") (pinfunction "2_2") (pintype "passive"))
      (node (ref "C36") (pin "2") (pinfunction "2_2") (pintype "passive"))
      (node (ref "C38") (pin "2") (pinfunction "2_2") (pintype "passive"))
      (node (ref "C39") (pin "2") (pinfunction "2_2") (pintype "passive"))
      (node (ref "C4") (pin "2") (pinfunction "2_2") (pintype "passive"))
      (node (ref "C40") (pin "2") (pinfunction "2_2") (pintype "passive"))
      (node (ref "C41") (pin "2") (pinfunction "2_2") (pintype "passive"))
      (node (ref "C42") (pin "2") (pinfunction "2_2") (pintype "passive"))
      (node (ref "C43") (pin "2") (pinfunction "2_2") (pintype "passive"))
      (node (ref "C44") (pin "2") (pinfunction "2_2") (pintype "passive"))
      (node (ref "C45") (pin "2") (pinfunction "2_2") (pintype "passive"))
      (node (ref "C46") (pin "2") (pinfunction "2_2") (pintype "passive"))
      (node (ref "C47") (pin "2") (pinfunction "2_2") (pintype "passive"))
      (node (ref "C48") (pin "2") (pinfunction "2_2") (pintype "passive"))
      (node (ref "C49") (pin "1") (pinfunction "1_1") (pintype "passive"))
      (node (ref "C5") (pin "2") (pinfunction "2_2") (pintype "passive"))
      (node (ref "C50") (pin "1") (pinfunction "1_1") (pintype "passive"))
      (node (ref "C51") (pin "1") (pinfunction "1_1") (pintype "passive"))
      (node (ref "C52") (pin "2") (pinfunction "2_2") (pintype "passive"))
      (node (ref "C53") (pin "2") (pinfunction "2_2") (pintype "passive"))
      (node (ref "C54") (pin "2") (pinfunction "2_2") (pintype "passive"))
      (node (ref "C55") (pin "2") (pinfunction "2_2") (pintype "passive"))
      (node (ref "C56") (pin "2") (pinfunction "2_2") (pintype "passive"))
      (node (ref "C57") (pin "2") (pinfunction "2_2") (pintype "passive"))
      (node (ref "C58") (pin "2") (pinfunction "2_2") (pintype "passive"))
      (node (ref "C59") (pin "2") (pinfunction "2_2") (pintype "passive"))
      (node (ref "C6") (pin "2") (pinfunction "2_2") (pintype "passive"))
      (node (ref "C60") (pin "2") (pinfunction "2_2") (pintype "passive"))
      (node (ref "C61") (pin "2") (pinfunction "2_2") (pintype "passive"))
      (node (ref "C62") (pin "2") (pinfunction "2_2") (pintype "passive"))
      (node (ref "C63") (pin "2") (pinfunction "2_2") (pintype "passive"))
      (node (ref "C64") (pin "2") (pinfunction "2_2") (pintype "passive"))
      (node (ref "C65") (pin "2") (pinfunction "2_2") (pintype "passive"))
      (node (ref "C66") (pin "2") (pinfunction "2_2") (pintype "passive"))
      (node (ref "C69") (pin "1") (pinfunction "1_1") (pintype "passive"))
      (node (ref "C7") (pin "2") (pinfunction "2_2") (pintype "passive"))
      (node (ref "C72") (pin "1") (pinfunction "1_1") (pintype "passive"))
      (node (ref "C73") (pin "1") (pinfunction "1_1") (pintype "passive"))
      (node (ref "C74") (pin "1") (pinfunction "1_1") (pintype "passive"))
      (node (ref "C75") (pin "1") (pinfunction "1_1") (pintype "passive"))
      (node (ref "C76") (pin "1") (pinfunction "1_1") (pintype "passive"))
      (node (ref "C77") (pin "1") (pinfunction "1_1") (pintype "passive"))
      (node (ref "C78") (pin "1") (pinfunction "1_1") (pintype "passive"))
      (node (ref "C79") (pin "1") (pinfunction "1_1") (pintype "passive"))
      (node (ref "C8") (pin "2") (pinfunction "2_2") (pintype "passive"))
      (node (ref "C80") (pin "1") (pinfunction "1_1") (pintype "passive"))
      (node (ref "C81") (pin "1") (pinfunction "1_1") (pintype "passive"))
      (node (ref "C82") (pin "1") (pinfunction "1_1") (pintype "passive"))
      (node (ref "C83") (pin "1") (pinfunction "1_1") (pintype "passive"))
      (node (ref "C84") (pin "1") (pinfunction "1_1") (pintype "passive"))
      (node (ref "C87") (pin "1") (pinfunction "1_1") (pintype "passive"))
      (node (ref "C88") (pin "2") (pinfunction "2_2") (pintype "passive"))
      (node (ref "C89") (pin "1") (pinfunction "1_1") (pintype "passive"))
      (node (ref "C9") (pin "2") (pinfunction "2_2") (pintype "passive"))
      (node (ref "C90") (pin "1") (pinfunction "1_1") (pintype "passive"))
      (node (ref "C93") (pin "2") (pinfunction "2_2") (pintype "passive"))
      (node (ref "C94") (pin "2") (pinfunction "2_2") (pintype "passive"))
      (node (ref "C95") (pin "1") (pinfunction "1_1") (pintype "passive"))
      (node (ref "C96") (pin "1") (pinfunction "1_1") (pintype "passive"))
      (node (ref "C97") (pin "2") (pinfunction "2_2") (pintype "passive"))
      (node (ref "C98") (pin "2") (pinfunction "2_2") (pintype "passive"))
      (node (ref "C99") (pin "2") (pinfunction "2_2") (pintype "passive"))
      (node (ref "D1") (pin "2") (pinfunction "C_2") (pintype "passive"))
      (node (ref "J1") (pin "17") (pinfunction "17_17") (pintype "passive"))
      (node (ref "J1") (pin "19") (pinfunction "19_19") (pintype "passive"))
      (node (ref "J1") (pin "2") (pinfunction "2_2") (pintype "passive"))
      (node (ref "J3") (pin "10") (pinfunction "10_10") (pintype "passive"))
      (node (ref "J3") (pin "12") (pinfunction "12_12") (pintype "passive"))
      (node (ref "J3") (pin "14") (pinfunction "14_14") (pintype "passive"))
      (node (ref "J3") (pin "16") (pinfunction "16_16") (pintype "passive"))
      (node (ref "J3") (pin "18") (pinfunction "18_18") (pintype "passive"))
      (node (ref "J3") (pin "20") (pinfunction "20_20") (pintype "passive"))
      (node (ref "J3") (pin "4") (pinfunction "4_4") (pintype "passive"))
      (node (ref "J3") (pin "6") (pinfunction "6_6") (pintype "passive"))
      (node (ref "J3") (pin "8") (pinfunction "8_8") (pintype "passive"))
      (node (ref "J4") (pin "2") (pinfunction "GND_2") (pintype "passive"))
      (node (ref "J5") (pin "10") (pinfunction "10_10") (pintype "passive"))
      (node (ref "J6") (pin "2") (pinfunction "2_2") (pintype "passive"))
      (node (ref "J7") (pin "2") (pinfunction "2_2") (pintype "passive"))
      (node (ref "J8") (pin "5") (pinfunction "GND_5") (pintype "bidirectional"))
      (node (ref "JP1") (pin "1") (pinfunction "1_1") (pintype "passive"))
      (node (ref "JP10") (pin "1") (pinfunction "1_1") (pintype "passive"))
      (node (ref "JP10") (pin "3") (pinfunction "3_3") (pintype "passive"))
      (node (ref "JP11") (pin "1") (pinfunction "1_1") (pintype "passive"))
      (node (ref "JP11") (pin "3") (pinfunction "3_3") (pintype "passive"))
      (node (ref "JP2") (pin "2") (pinfunction "2_2") (pintype "passive"))
      (node (ref "JP3") (pin "2") (pinfunction "2_2") (pintype "passive"))
      (node (ref "JP8") (pin "3") (pinfunction "3_3") (pintype "passive"))
      (node (ref "JP9") (pin "1") (pinfunction "1_1") (pintype "passive"))
      (node (ref "JP9") (pin "10") (pinfunction "10_10") (pintype "passive"))
      (node (ref "JP9") (pin "4") (pinfunction "4_4") (pintype "passive"))
      (node (ref "Q1") (pin "2") (pinfunction "G1_2") (pintype "power_in"))
      (node (ref "Q1") (pin "4") (pinfunction "G2_4") (pintype "power_in"))
      (node (ref "R23") (pin "2") (pinfunction "2_2") (pintype "passive"))
      (node (ref "R24") (pin "1") (pinfunction "1_1") (pintype "passive"))
      (node (ref "R26") (pin "1") (pinfunction "1_1") (pintype "passive"))
      (node (ref "R29") (pin "1") (pinfunction "1_1") (pintype "passive"))
      (node (ref "R34") (pin "1") (pinfunction "1_1") (pintype "passive"))
      (node (ref "R39") (pin "2") (pinfunction "2_2") (pintype "passive"))
      (node (ref "R4") (pin "1") (pinfunction "1_1") (pintype "passive"))
      (node (ref "R40") (pin "2") (pinfunction "2_2") (pintype "passive"))
      (node (ref "R41") (pin "2") (pinfunction "2_2") (pintype "passive"))
      (node (ref "R42") (pin "2") (pinfunction "2_2") (pintype "passive"))
      (node (ref "R43") (pin "2") (pinfunction "2_2") (pintype "passive"))
      (node (ref "R45") (pin "1") (pinfunction "1_1") (pintype "passive"))
      (node (ref "R48") (pin "2") (pinfunction "2_2") (pintype "passive"))
      (node (ref "R50") (pin "1") (pinfunction "1_1") (pintype "passive"))
      (node (ref "R54") (pin "1") (pinfunction "1_1") (pintype "passive"))
      (node (ref "R56") (pin "1") (pinfunction "1_1") (pintype "passive"))
      (node (ref "R57") (pin "1") (pinfunction "1_1") (pintype "passive"))
      (node (ref "R58") (pin "1") (pinfunction "1_1") (pintype "passive"))
      (node (ref "R65") (pin "2") (pinfunction "2_2") (pintype "passive"))
      (node (ref "R71") (pin "2") (pinfunction "2_2") (pintype "passive"))
      (node (ref "R77") (pin "1") (pinfunction "1_1") (pintype "passive"))
      (node (ref "R8") (pin "1") (pinfunction "1_1") (pintype "passive"))
      (node (ref "S1") (pin "3") (pinfunction "3_3") (pintype "passive"))
      (node (ref "S1") (pin "4") (pinfunction "4_4") (pintype "passive"))
      (node (ref "T2") (pin "2") (pinfunction "S_2") (pintype "passive"))
      (node (ref "T4") (pin "2") (pinfunction "S_2") (pintype "passive"))
      (node (ref "U1") (pin "3") (pinfunction "GNDANA_3") (pintype "passive"))
      (node (ref "U1") (pin "35") (pinfunction "GND_2_35") (pintype "passive"))
      (node (ref "U1") (pin "42") (pinfunction "FWUP_42") (pintype "input"))
      (node (ref "U1") (pin "44") (pinfunction "TST_44") (pintype "input"))
      (node (ref "U1") (pin "46") (pinfunction "GNDBU_46") (pintype "passive"))
      (node (ref "U1") (pin "48") (pinfunction "JTAGSEL_48") (pintype "input"))
      (node (ref "U1") (pin "61") (pinfunction "GND_3_61") (pintype "passive"))
      (node (ref "U1") (pin "72") (pinfunction "GNDPLL_72") (pintype "passive"))
      (node (ref "U1") (pin "82") (pinfunction "GNDUTMI_82") (pintype "passive"))
      (node (ref "U1") (pin "89") (pinfunction "GND_89") (pintype "passive"))
      (node (ref "U10") (pin "2") (pinfunction "GND_2") (pintype "input"))
      (node (ref "U2") (pin "P108") (pinfunction "GND_P108") (pintype "power_in"))
      (node (ref "U2") (pin "P113") (pinfunction "GND_P113") (pintype "power_in"))
      (node (ref "U2") (pin "P13") (pinfunction "GND_P13") (pintype "power_in"))
      (node (ref "U2") (pin "P130") (pinfunction "GND_P130") (pintype "power_in"))
      (node (ref "U2") (pin "P136") (pinfunction "GND_P136") (pintype "power_in"))
      (node (ref "U2") (pin "P25") (pinfunction "GND_P25") (pintype "power_in"))
      (node (ref "U2") (pin "P3") (pinfunction "GND_P3") (pintype "power_in"))
      (node (ref "U2") (pin "P49") (pinfunction "GND_P49") (pintype "power_in"))
      (node (ref "U2") (pin "P54") (pinfunction "GND_P54") (pintype "power_in"))
      (node (ref "U2") (pin "P68") (pinfunction "GND_P68") (pintype "power_in"))
      (node (ref "U2") (pin "P73") (pinfunction "SUSPEND_P73") (pintype "input"))
      (node (ref "U2") (pin "P77") (pinfunction "GND_P77") (pintype "power_in"))
      (node (ref "U2") (pin "P91") (pinfunction "GND_P91") (pintype "power_in"))
      (node (ref "U2") (pin "P96") (pinfunction "GND_P96") (pintype "power_in"))
      (node (ref "U3") (pin "17") (pinfunction "COMM_17") (pintype "bidirectional"))
      (node (ref "U3") (pin "20") (pinfunction "COMM_20") (pintype "bidirectional"))
      (node (ref "U3") (pin "6") (pinfunction "COML_6") (pintype "bidirectional"))
      (node (ref "U3") (pin "9") (pinfunction "MODE_9") (pintype "bidirectional"))
      (node (ref "U4") (pin "11") (pinfunction "AGND_11") (pintype "bidirectional"))
      (node (ref "U4") (pin "14") (pinfunction "PDWN_14") (pintype "bidirectional"))
      (node (ref "U4") (pin "23") (pinfunction "DRGND_23") (pintype "bidirectional"))
      (node (ref "U4") (pin "3") (pinfunction "SENSE_3") (pintype "bidirectional"))
      (node (ref "U4") (pin "8") (pinfunction "AGND_8") (pintype "bidirectional"))
      (node (ref "U5") (pin "5") (pinfunction "GND_5") (pintype "power_in"))
      (node (ref "U5") (pin "6") (pinfunction "GND_6") (pintype "power_in"))
      (node (ref "U6") (pin "1") (pinfunction "GND_1") (pintype "bidirectional"))
      (node (ref "U7") (pin "2") (pinfunction "GND_2") (pintype "input"))
      (node (ref "U8") (pin "1") (pinfunction "S_1") (pintype "bidirectional"))
      (node (ref "U8") (pin "2") (pinfunction "S_2") (pintype "bidirectional"))
      (node (ref "U8") (pin "3") (pinfunction "S_3") (pintype "bidirectional"))
      (node (ref "U9") (pin "4") (pinfunction "GND_4") (pintype "bidirectional"))
      (node (ref "X2") (pin "G@1") (pinfunction "2_G@1") (pintype "passive"))
      (node (ref "X2") (pin "G@2") (pinfunction "2_G@2") (pintype "passive"))
      (node (ref "X2") (pin "G@3") (pinfunction "2_G@3") (pintype "passive"))
      (node (ref "X2") (pin "G@4") (pinfunction "2_G@4") (pintype "passive"))
      (node (ref "X4") (pin "G@1") (pinfunction "2_G@1") (pintype "passive"))
      (node (ref "X4") (pin "G@2") (pinfunction "2_G@2") (pintype "passive"))
      (node (ref "X4") (pin "G@3") (pinfunction "2_G@3") (pintype "passive"))
      (node (ref "X4") (pin "G@4") (pinfunction "2_G@4") (pintype "passive"))
    )
    (net (code "37") (name "NRST") (class "Default")
      (node (ref "R16") (pin "2") (pinfunction "2_2") (pintype "passive"))
      (node (ref "R17") (pin "1") (pinfunction "1_1") (pintype "passive"))
      (node (ref "U1") (pin "57") (pinfunction "NRST_57") (pintype "input"))
    )
    (net (code "38") (name "NRSTB") (class "Default")
      (node (ref "JP2") (pin "1") (pinfunction "1_1") (pintype "passive"))
      (node (ref "S1") (pin "1") (pinfunction "1_1") (pintype "passive"))
      (node (ref "S1") (pin "2") (pinfunction "2_2") (pintype "passive"))
      (node (ref "U1") (pin "47") (pinfunction "NRSTB_47") (pintype "bidirectional"))
    )
    (net (code "39") (name "Net-(C3-Pad2)") (class "Default")
      (node (ref "C3") (pin "2") (pinfunction "2_2") (pintype "passive"))
      (node (ref "R15") (pin "1") (pinfunction "1_1") (pintype "passive"))
    )
    (net (code "40") (name "Net-(C48-Pad1)") (class "Default")
      (node (ref "C48") (pin "1") (pinfunction "1_1") (pintype "passive"))
      (node (ref "J8") (pin "E1") (pinfunction "SHIELD_E1") (pintype "bidirectional"))
      (node (ref "J8") (pin "E2") (pinfunction "SHIELD_E2") (pintype "bidirectional"))
      (node (ref "J8") (pin "P$1") (pinfunction "SHIELD_P$1") (pintype "bidirectional"))
      (node (ref "J8") (pin "P$2") (pinfunction "SHIELD_P$2") (pintype "bidirectional"))
      (node (ref "J8") (pin "P$3") (pinfunction "SHIELD_P$3") (pintype "bidirectional"))
      (node (ref "J8") (pin "P$4") (pinfunction "SHIELD_P$4") (pintype "bidirectional"))
    )
    (net (code "41") (name "Net-(C67-Pad1)") (class "Default")
      (node (ref "C67") (pin "1") (pinfunction "1_1") (pintype "passive"))
      (node (ref "R44") (pin "1") (pinfunction "1_1") (pintype "passive"))
    )
    (net (code "42") (name "Net-(C68-Pad1)") (class "Default")
      (node (ref "C68") (pin "1") (pinfunction "1_1") (pintype "passive"))
      (node (ref "L11") (pin "2") (pinfunction "2_2") (pintype "passive"))
    )
    (net (code "43") (name "Net-(C85-Pad1)") (class "Default")
      (node (ref "C85") (pin "1") (pinfunction "1_1") (pintype "passive"))
      (node (ref "R46") (pin "1") (pinfunction "1_1") (pintype "passive"))
    )
    (net (code "44") (name "Net-(C86-Pad1)") (class "Default")
      (node (ref "C86") (pin "1") (pinfunction "1_1") (pintype "passive"))
      (node (ref "R47") (pin "1") (pinfunction "1_1") (pintype "passive"))
    )
    (net (code "45") (name "Net-(C90-Pad2)") (class "Default")
      (node (ref "C90") (pin "2") (pinfunction "2_2") (pintype "passive"))
      (node (ref "R52") (pin "1") (pinfunction "1_1") (pintype "passive"))
      (node (ref "R53") (pin "2") (pinfunction "2_2") (pintype "passive"))
    )
    (net (code "46") (name "Net-(C101-Pad1)") (class "Default")
      (node (ref "C101") (pin "1") (pinfunction "1_1") (pintype "passive"))
      (node (ref "C102") (pin "1") (pinfunction "1_1") (pintype "passive"))
      (node (ref "C63") (pin "1") (pinfunction "1_1") (pintype "passive"))
      (node (ref "C64") (pin "1") (pinfunction "1_1") (pintype "passive"))
      (node (ref "C65") (pin "1") (pinfunction "1_1") (pintype "passive"))
      (node (ref "C66") (pin "1") (pinfunction "1_1") (pintype "passive"))
      (node (ref "JP5") (pin "2") (pinfunction "2_2") (pintype "passive"))
      (node (ref "SJ6") (pin "2") (pinfunction "2_2") (pintype "passive"))
      (node (ref "U2") (pin "P103") (pinfunction "VCCO_1_P103") (pintype "input"))
      (node (ref "U2") (pin "P76") (pinfunction "VCCO_1_P76") (pintype "input"))
      (node (ref "U2") (pin "P86") (pinfunction "VCCO_1_P86") (pintype "input"))
    )
    (net (code "47") (name "Net-(D1-A)") (class "Default")
      (node (ref "C89") (pin "2") (pinfunction "2_2") (pintype "passive"))
      (node (ref "D1") (pin "3") (pinfunction "A_3") (pintype "passive"))
      (node (ref "R52") (pin "2") (pinfunction "2_2") (pintype "passive"))
      (node (ref "U3") (pin "10") (pinfunction "GAIN_10") (pintype "bidirectional"))
    )
    (net (code "48") (name "Net-(D2-PadC)") (class "Default")
      (node (ref "D2") (pin "C") (pinfunction "C_C") (pintype "passive"))
      (node (ref "R58") (pin "2") (pinfunction "2_2") (pintype "passive"))
    )
    (net (code "49") (name "Net-(D4-PadC)") (class "Default")
      (node (ref "D4") (pin "C") (pinfunction "C_C") (pintype "passive"))
      (node (ref "R39") (pin "1") (pinfunction "1_1") (pintype "passive"))
    )
    (net (code "50") (name "Net-(D5-PadC)") (class "Default")
      (node (ref "D5") (pin "C") (pinfunction "C_C") (pintype "passive"))
      (node (ref "R40") (pin "1") (pinfunction "1_1") (pintype "passive"))
    )
    (net (code "51") (name "Net-(D6-PadC)") (class "Default")
      (node (ref "D6") (pin "C") (pinfunction "C_C") (pintype "passive"))
      (node (ref "R41") (pin "1") (pinfunction "1_1") (pintype "passive"))
    )
    (net (code "52") (name "Net-(D7-PadC)") (class "Default")
      (node (ref "D7") (pin "C") (pinfunction "C_C") (pintype "passive"))
      (node (ref "R42") (pin "1") (pinfunction "1_1") (pintype "passive"))
    )
    (net (code "53") (name "Net-(D9-PadC)") (class "Default")
      (node (ref "D9") (pin "C") (pinfunction "C_C") (pintype "passive"))
      (node (ref "R57") (pin "2") (pinfunction "2_2") (pintype "passive"))
    )
    (net (code "54") (name "Net-(J3-Pad3)") (class "Default")
      (node (ref "J3") (pin "3") (pinfunction "3_3") (pintype "passive"))
      (node (ref "R21") (pin "1") (pinfunction "1_1") (pintype "passive"))
    )
    (net (code "55") (name "Net-(J3-Pad15)") (class "Default")
      (node (ref "J3") (pin "15") (pinfunction "15_15") (pintype "passive"))
      (node (ref "R16") (pin "1") (pinfunction "1_1") (pintype "passive"))
    )
    (net (code "56") (name "Net-(J4-TCK)") (class "Default")
      (node (ref "J4") (pin "3") (pinfunction "TCK_3") (pintype "passive"))
      (node (ref "U2") (pin "P109") (pinfunction "TCK_P109") (pintype "input"))
    )
    (net (code "57") (name "Net-(J4-TDI)") (class "Default")
      (node (ref "J4") (pin "5") (pinfunction "TDI_5") (pintype "passive"))
      (node (ref "U2") (pin "P110") (pinfunction "TDI_P110") (pintype "input"))
    )
    (net (code "58") (name "Net-(J4-TDO)") (class "Default")
      (node (ref "J4") (pin "4") (pinfunction "TDO_4") (pintype "passive"))
      (node (ref "U2") (pin "P106") (pinfunction "TDO_P106") (pintype "output"))
    )
    (net (code "59") (name "Net-(J4-TMS)") (class "Default")
      (node (ref "J4") (pin "6") (pinfunction "TMS_6") (pintype "passive"))
      (node (ref "U2") (pin "P107") (pinfunction "TMS_P107") (pintype "input"))
    )
    (net (code "60") (name "Net-(J6-Pad1)") (class "Default")
      (node (ref "J6") (pin "1") (pinfunction "1_1") (pintype "passive"))
      (node (ref "R59") (pin "2") (pinfunction "2_2") (pintype "passive"))
      (node (ref "R61") (pin "1") (pinfunction "1_1") (pintype "passive"))
    )
    (net (code "61") (name "Net-(J6-Pad4)") (class "Default")
      (node (ref "J6") (pin "4") (pinfunction "4_4") (pintype "passive"))
      (node (ref "R60") (pin "1") (pinfunction "1_1") (pintype "passive"))
    )
    (net (code "62") (name "Net-(J7-Pad1)") (class "Default")
      (node (ref "J7") (pin "1") (pinfunction "1_1") (pintype "passive"))
      (node (ref "R62") (pin "2") (pinfunction "2_2") (pintype "passive"))
    )
    (net (code "63") (name "Net-(J7-Pad4)") (class "Default")
      (node (ref "J7") (pin "4") (pinfunction "4_4") (pintype "passive"))
      (node (ref "R63") (pin "2") (pinfunction "2_2") (pintype "passive"))
    )
    (net (code "64") (name "Net-(J8-VCC)") (class "Default")
      (node (ref "J8") (pin "1") (pinfunction "VCC_1") (pintype "bidirectional"))
      (node (ref "SJ1") (pin "1") (pinfunction "1_1") (pintype "passive"))
      (node (ref "U6") (pin "4") (pinfunction "VCC_4") (pintype "bidirectional"))
    )
    (net (code "65") (name "Net-(JP3-Pad1)") (class "Default")
      (node (ref "JP3") (pin "1") (pinfunction "1_1") (pintype "passive"))
      (node (ref "SJ1") (pin "3") (pinfunction "3_3") (pintype "passive"))
    )
    (net (code "66") (name "Net-(Q1-X1)") (class "Default")
      (node (ref "C50") (pin "2") (pinfunction "2_2") (pintype "passive"))
      (node (ref "Q1") (pin "1") (pinfunction "X1_1") (pintype "bidirectional"))
      (node (ref "U1") (pin "74") (pinfunction "XOUT_74") (pintype "output"))
    )
    (net (code "67") (name "Net-(Q1-X2)") (class "Default")
      (node (ref "C51") (pin "2") (pinfunction "2_2") (pintype "passive"))
      (node (ref "Q1") (pin "3") (pinfunction "X2_3") (pintype "bidirectional"))
      (node (ref "U1") (pin "75") (pinfunction "XIN_75") (pintype "input"))
    )
    (net (code "68") (name "Net-(T1-D)") (class "Default")
      (node (ref "C47") (pin "1") (pinfunction "1_1") (pintype "passive"))
      (node (ref "L4") (pin "1") (pinfunction "1_1") (pintype "passive"))
      (node (ref "L5") (pin "1") (pinfunction "1_1") (pintype "passive"))
      (node (ref "T1") (pin "1") (pinfunction "D_1") (pintype "passive"))
    )
    (net (code "69") (name "Net-(T1-G)") (class "Default")
      (node (ref "C122") (pin "1") (pinfunction "1_1") (pintype "passive"))
      (node (ref "R31") (pin "1") (pinfunction "1_1") (pintype "passive"))
      (node (ref "R79") (pin "2") (pinfunction "2_2") (pintype "passive"))
      (node (ref "T1") (pin "3") (pinfunction "G_3") (pintype "passive"))
    )
    (net (code "70") (name "Net-(T1-S)") (class "Default")
      (node (ref "C46") (pin "1") (pinfunction "1_1") (pintype "passive"))
      (node (ref "L6") (pin "1") (pinfunction "1_1") (pintype "passive"))
      (node (ref "R31") (pin "2") (pinfunction "2_2") (pintype "passive"))
      (node (ref "SJ1") (pin "2") (pinfunction "2_2") (pintype "passive"))
      (node (ref "T1") (pin "2") (pinfunction "S_2") (pintype "passive"))
    )
    (net (code "71") (name "Net-(T2-D)") (class "Default")
      (node (ref "R79") (pin "1") (pinfunction "1_1") (pintype "passive"))
      (node (ref "T2") (pin "1") (pinfunction "D_1") (pintype "passive"))
    )
    (net (code "72") (name "Net-(T4-G)") (class "Default")
      (node (ref "R43") (pin "1") (pinfunction "1_1") (pintype "passive"))
      (node (ref "R78") (pin "1") (pinfunction "1_1") (pintype "passive"))
      (node (ref "T4") (pin "3") (pinfunction "G_3") (pintype "passive"))
    )
    (net (code "73") (name "Net-(U1-DFSDM)") (class "Default")
      (node (ref "R27") (pin "1") (pinfunction "1_1") (pintype "passive"))
      (node (ref "U1") (pin "80") (pinfunction "DFSDM_80") (pintype "bidirectional"))
    )
    (net (code "74") (name "Net-(U1-DFSDP)") (class "Default")
      (node (ref "R28") (pin "1") (pinfunction "1_1") (pintype "passive"))
      (node (ref "U1") (pin "81") (pinfunction "DFSDP_81") (pintype "bidirectional"))
    )
    (net (code "75") (name "Net-(U1-PA6{slash}PGMM2)") (class "Default")
      (node (ref "D9") (pin "A") (pinfunction "A_A") (pintype "passive"))
      (node (ref "U1") (pin "32") (pinfunction "PA6/PGMM2_32") (pintype "bidirectional"))
    )
    (net (code "76") (name "Net-(U1-PA7{slash}PGMM3)") (class "Default")
      (node (ref "D2") (pin "A") (pinfunction "A_A") (pintype "passive"))
      (node (ref "U1") (pin "33") (pinfunction "PA7/PGMM3_33") (pintype "bidirectional"))
    )
    (net (code "77") (name "Net-(U1-PA11{slash}PGMD3)") (class "Default")
      (node (ref "JP1") (pin "3") (pinfunction "3_3") (pintype "passive"))
      (node (ref "U1") (pin "40") (pinfunction "PA11/PGMD3_40") (pintype "bidirectional"))
    )
    (net (code "78") (name "Net-(U1-PA12{slash}PGMD4)") (class "Default")
      (node (ref "JP1") (pin "2") (pinfunction "2_2") (pintype "passive"))
      (node (ref "U1") (pin "41") (pinfunction "PA12/PGMD4_41") (pintype "bidirectional"))
    )
    (net (code "79") (name "Net-(U1-PA20{slash}PGMD12)") (class "Default")
      (node (ref "R2") (pin "1") (pinfunction "1_1") (pintype "passive"))
      (node (ref "U1") (pin "19") (pinfunction "PA20/PGMD12_19") (pintype "bidirectional"))
    )
    (net (code "80") (name "Net-(U1-PA21{slash}PGMD13)") (class "Default")
      (node (ref "R10") (pin "1") (pinfunction "1_1") (pintype "passive"))
      (node (ref "U1") (pin "20") (pinfunction "PA21/PGMD13_20") (pintype "bidirectional"))
    )
    (net (code "81") (name "Net-(U1-PA27)") (class "Default")
      (node (ref "R14") (pin "1") (pinfunction "1_1") (pintype "passive"))
      (node (ref "U1") (pin "96") (pinfunction "PA27_96") (pintype "bidirectional"))
    )
    (net (code "82") (name "Net-(U1-PB24)") (class "Default")
      (node (ref "R1") (pin "1") (pinfunction "1_1") (pintype "passive"))
      (node (ref "U1") (pin "58") (pinfunction "PB24_58") (pintype "bidirectional"))
    )
    (net (code "83") (name "Net-(U1-VBG)") (class "Default")
      (node (ref "C33") (pin "1") (pinfunction "1_1") (pintype "passive"))
      (node (ref "R29") (pin "2") (pinfunction "2_2") (pintype "passive"))
      (node (ref "U1") (pin "78") (pinfunction "VBG_78") (pintype "bidirectional"))
    )
    (net (code "84") (name "Net-(U1-VDDCORE)") (class "Default")
      (node (ref "C10") (pin "1") (pinfunction "1_1") (pintype "passive"))
      (node (ref "C11") (pin "1") (pinfunction "1_1") (pintype "passive"))
      (node (ref "C12") (pin "1") (pinfunction "1_1") (pintype "passive"))
      (node (ref "C123") (pin "1") (pinfunction "1_1") (pintype "passive"))
      (node (ref "C19") (pin "1") (pinfunction "1_1") (pintype "passive"))
      (node (ref "C5") (pin "1") (pinfunction "1_1") (pintype "passive"))
      (node (ref "C7") (pin "1") (pinfunction "1_1") (pintype "passive"))
      (node (ref "C8") (pin "1") (pinfunction "1_1") (pintype "passive"))
      (node (ref "C9") (pin "1") (pinfunction "1_1") (pintype "passive"))
      (node (ref "U1") (pin "34") (pinfunction "VDDCORE_34") (pintype "power_in"))
      (node (ref "U1") (pin "52") (pinfunction "VDDOUT_52") (pintype "power_in"))
      (node (ref "U1") (pin "59") (pinfunction "VDDCORE_5_59") (pintype "power_in"))
      (node (ref "U1") (pin "73") (pinfunction "VDDPLL_73") (pintype "power_in"))
      (node (ref "U1") (pin "83") (pinfunction "VDDCORE_3_83") (pintype "power_in"))
      (node (ref "U1") (pin "87") (pinfunction "VDDCORE_2_87") (pintype "power_in"))
      (node (ref "U1") (pin "9") (pinfunction "VDDCORE_4_9") (pintype "power_in"))
    )
    (net (code "85") (name "Net-(U1-VDDUTMI)") (class "Default")
      (node (ref "C4") (pin "1") (pinfunction "1_1") (pintype "passive"))
      (node (ref "L1") (pin "2") (pinfunction "2_2") (pintype "passive"))
      (node (ref "R15") (pin "2") (pinfunction "2_2") (pintype "passive"))
      (node (ref "U1") (pin "79") (pinfunction "VDDUTMI_79") (pintype "power_in"))
    )
    (net (code "86") (name "Net-(U2A-IO_L1N_VREF_0)") (class "Default")
      (node (ref "D4") (pin "A") (pinfunction "A_A") (pintype "passive"))
      (node (ref "U2") (pin "P143") (pinfunction "IO_L1N_VREF_0_P143") (pintype "bidirectional"))
    )
    (net (code "87") (name "Net-(U2A-IO_L1P_HSWAPEN_0)") (class "Default")
      (node (ref "R68") (pin "1") (pinfunction "1_1") (pintype "passive"))
      (node (ref "U2") (pin "P144") (pinfunction "IO_L1P_HSWAPEN_0_P144") (pintype "bidirectional"))
    )
    (net (code "88") (name "Net-(U2A-IO_L2N_0)") (class "Default")
      (node (ref "D6") (pin "A") (pinfunction "A_A") (pintype "passive"))
      (node (ref "U2") (pin "P141") (pinfunction "IO_L2N_0_P141") (pintype "bidirectional"))
    )
    (net (code "89") (name "Net-(U2A-IO_L2P_0)") (class "Default")
      (node (ref "D5") (pin "A") (pinfunction "A_A") (pintype "passive"))
      (node (ref "U2") (pin "P142") (pinfunction "IO_L2P_0_P142") (pintype "bidirectional"))
    )
    (net (code "90") (name "Net-(U2A-IO_L3P_0)") (class "Default")
      (node (ref "D7") (pin "A") (pinfunction "A_A") (pintype "passive"))
      (node (ref "U2") (pin "P140") (pinfunction "IO_L3P_0_P140") (pintype "bidirectional"))
    )
    (net (code "91") (name "Net-(U2A-IO_L62N_VREF_0)") (class "Default")
      (node (ref "J5") (pin "1") (pinfunction "1_1") (pintype "passive"))
      (node (ref "U2") (pin "P120") (pinfunction "IO_L62N_VREF_0_P120") (pintype "bidirectional"))
    )
    (net (code "92") (name "Net-(U2A-IO_L63N_SCP6_0)") (class "Default")
      (node (ref "J5") (pin "3") (pinfunction "3_3") (pintype "passive"))
      (node (ref "U2") (pin "P118") (pinfunction "IO_L63N_SCP6_0_P118") (pintype "bidirectional"))
    )
    (net (code "93") (name "Net-(U2A-IO_L63P_SCP7_0)") (class "Default")
      (node (ref "J5") (pin "2") (pinfunction "2_2") (pintype "passive"))
      (node (ref "U2") (pin "P119") (pinfunction "IO_L63P_SCP7_0_P119") (pintype "bidirectional"))
    )
    (net (code "94") (name "Net-(U2A-IO_L64N_SCP4_0)") (class "Default")
      (node (ref "J5") (pin "5") (pinfunction "5_5") (pintype "passive"))
      (node (ref "U2") (pin "P116") (pinfunction "IO_L64N_SCP4_0_P116") (pintype "bidirectional"))
    )
    (net (code "95") (name "Net-(U2A-IO_L64P_SCP5_0)") (class "Default")
      (node (ref "J5") (pin "4") (pinfunction "4_4") (pintype "passive"))
      (node (ref "U2") (pin "P117") (pinfunction "IO_L64P_SCP5_0_P117") (pintype "bidirectional"))
    )
    (net (code "96") (name "Net-(U2A-IO_L65N_SCP2_0)") (class "Default")
      (node (ref "J5") (pin "7") (pinfunction "7_7") (pintype "passive"))
      (node (ref "U2") (pin "P114") (pinfunction "IO_L65N_SCP2_0_P114") (pintype "bidirectional"))
    )
    (net (code "97") (name "Net-(U2A-IO_L65P_SCP3_0)") (class "Default")
      (node (ref "J5") (pin "6") (pinfunction "6_6") (pintype "passive"))
      (node (ref "U2") (pin "P115") (pinfunction "IO_L65P_SCP3_0_P115") (pintype "bidirectional"))
    )
    (net (code "98") (name "Net-(U2A-IO_L66N_SCP0_0)") (class "Default")
      (node (ref "J5") (pin "9") (pinfunction "9_9") (pintype "passive"))
      (node (ref "U2") (pin "P111") (pinfunction "IO_L66N_SCP0_0_P111") (pintype "bidirectional"))
    )
    (net (code "99") (name "Net-(U2A-IO_L66P_SCP1_0)") (class "Default")
      (node (ref "J5") (pin "8") (pinfunction "8_8") (pintype "passive"))
      (node (ref "U2") (pin "P112") (pinfunction "IO_L66P_SCP1_0_P112") (pintype "bidirectional"))
    )
    (net (code "100") (name "Net-(U2B-IO_L1P_1)") (class "Default")
      (node (ref "JP18") (pin "1") (pinfunction "1_1") (pintype "passive"))
      (node (ref "U2") (pin "P105") (pinfunction "IO_L1P_1_P105") (pintype "bidirectional"))
    )
    (net (code "101") (name "Net-(U2C-IO_L1N_M0_CMPMISO_2)") (class "Default")
      (node (ref "R7") (pin "2") (pinfunction "2_2") (pintype "passive"))
      (node (ref "R8") (pin "2") (pinfunction "2_2") (pintype "passive"))
      (node (ref "U2") (pin "P69") (pinfunction "IO_L1N_M0_CMPMISO_2_P69") (pintype "bidirectional"))
    )
    (net (code "102") (name "Net-(U2C-IO_L1P_CCLK_2)") (class "Default")
      (node (ref "R5") (pin "1") (pinfunction "1_1") (pintype "passive"))
      (node (ref "R70") (pin "2") (pinfunction "2_2") (pintype "passive"))
      (node (ref "R71") (pin "1") (pinfunction "1_1") (pintype "passive"))
      (node (ref "U2") (pin "P70") (pinfunction "IO_L1P_CCLK_2_P70") (pintype "bidirectional"))
      (node (ref "U9") (pin "6") (pinfunction "SCK_6") (pintype "bidirectional"))
    )
    (net (code "103") (name "Net-(U2C-IO_L3N_MOSI_CSI_B_MISO0_2)") (class "Default")
      (node (ref "U2") (pin "P64") (pinfunction "IO_L3N_MOSI_CSI_B_MISO0_2_P64") (pintype "bidirectional"))
      (node (ref "U9") (pin "5") (pinfunction "MOSI_5") (pintype "bidirectional"))
    )
    (net (code "104") (name "Net-(U2C-IO_L3P_D0_DIN_MISO_MISO1_2)") (class "Default")
      (node (ref "R22") (pin "2") (pinfunction "2_2") (pintype "passive"))
      (node (ref "R6") (pin "2") (pinfunction "2_2") (pintype "passive"))
      (node (ref "U2") (pin "P65") (pinfunction "IO_L3P_D0_DIN_MISO_MISO1_2_P65") (pintype "bidirectional"))
    )
    (net (code "105") (name "Net-(U2C-IO_L13P_M1_2)") (class "Default")
      (node (ref "R3") (pin "2") (pinfunction "2_2") (pintype "passive"))
      (node (ref "R4") (pin "2") (pinfunction "2_2") (pintype "passive"))
      (node (ref "U2") (pin "P60") (pinfunction "IO_L13P_M1_2_P60") (pintype "bidirectional"))
    )
    (net (code "106") (name "Net-(U2C-IO_L65N_CSO_B_2)") (class "Default")
      (node (ref "R9") (pin "1") (pinfunction "1_1") (pintype "passive"))
      (node (ref "U2") (pin "P38") (pinfunction "IO_L65N_CSO_B_2_P38") (pintype "bidirectional"))
      (node (ref "U9") (pin "1") (pinfunction "CS_1") (pintype "bidirectional"))
    )
    (net (code "107") (name "Net-(U3-ENBL)") (class "Default")
      (node (ref "C80") (pin "2") (pinfunction "2_2") (pintype "passive"))
      (node (ref "C81") (pin "2") (pinfunction "2_2") (pintype "passive"))
      (node (ref "C82") (pin "2") (pinfunction "2_2") (pintype "passive"))
      (node (ref "L8") (pin "2") (pinfunction "2_2") (pintype "passive"))
      (node (ref "U3") (pin "18") (pinfunction "ENBV_18") (pintype "bidirectional"))
      (node (ref "U3") (pin "19") (pinfunction "ENBL_19") (pintype "bidirectional"))
      (node (ref "U3") (pin "3") (pinfunction "VPSL_3") (pintype "bidirectional"))
    )
    (net (code "108") (name "Net-(U3-INH)") (class "Default")
      (node (ref "C67") (pin "2") (pinfunction "2_2") (pintype "passive"))
      (node (ref "C68") (pin "2") (pinfunction "2_2") (pintype "passive"))
      (node (ref "C69") (pin "2") (pinfunction "2_2") (pintype "passive"))
      (node (ref "U3") (pin "2") (pinfunction "INH_2") (pintype "bidirectional"))
    )
    (net (code "109") (name "Net-(U3-LMD)") (class "Default")
      (node (ref "C79") (pin "2") (pinfunction "2_2") (pintype "passive"))
      (node (ref "U3") (pin "1") (pinfunction "LMD_1") (pintype "bidirectional"))
    )
    (net (code "110") (name "Net-(U3-LON)") (class "Default")
      (node (ref "C70") (pin "2") (pinfunction "2_2") (pintype "passive"))
      (node (ref "R44") (pin "2") (pinfunction "2_2") (pintype "passive"))
      (node (ref "U3") (pin "4") (pinfunction "LON_4") (pintype "bidirectional"))
    )
    (net (code "111") (name "Net-(U3-LOP)") (class "Default")
      (node (ref "C71") (pin "2") (pinfunction "2_2") (pintype "passive"))
      (node (ref "U3") (pin "5") (pinfunction "LOP_5") (pintype "bidirectional"))
    )
    (net (code "112") (name "Net-(U3-RCLMP)") (class "Default")
      (node (ref "C74") (pin "2") (pinfunction "2_2") (pintype "passive"))
      (node (ref "C75") (pin "2") (pinfunction "2_2") (pintype "passive"))
      (node (ref "R45") (pin "2") (pinfunction "2_2") (pintype "passive"))
      (node (ref "U3") (pin "12") (pinfunction "RCLMP_12") (pintype "bidirectional"))
    )
    (net (code "113") (name "Net-(U3-VCM)") (class "Default")
      (node (ref "C72") (pin "2") (pinfunction "2_2") (pintype "passive"))
      (node (ref "C73") (pin "2") (pinfunction "2_2") (pintype "passive"))
      (node (ref "U3") (pin "11") (pinfunction "VCM_11") (pintype "bidirectional"))
    )
    (net (code "114") (name "Net-(U3-VIN)") (class "Default")
      (node (ref "C70") (pin "1") (pinfunction "1_1") (pintype "passive"))
      (node (ref "U3") (pin "8") (pinfunction "VIN_8") (pintype "bidirectional"))
    )
    (net (code "115") (name "Net-(U3-VIP)") (class "Default")
      (node (ref "C71") (pin "1") (pinfunction "1_1") (pintype "passive"))
      (node (ref "U3") (pin "7") (pinfunction "VIP_7") (pintype "bidirectional"))
    )
    (net (code "116") (name "Net-(U3-VOH)") (class "Default")
      (node (ref "C85") (pin "2") (pinfunction "2_2") (pintype "passive"))
      (node (ref "U3") (pin "15") (pinfunction "VOH_15") (pintype "bidirectional"))
    )
    (net (code "117") (name "Net-(U3-VOL)") (class "Default")
      (node (ref "C86") (pin "2") (pinfunction "2_2") (pintype "passive"))
      (node (ref "U3") (pin "16") (pinfunction "VOL_16") (pintype "bidirectional"))
    )
    (net (code "118") (name "Net-(U3-VPOS)") (class "Default")
      (node (ref "C76") (pin "2") (pinfunction "2_2") (pintype "passive"))
      (node (ref "C77") (pin "2") (pinfunction "2_2") (pintype "passive"))
      (node (ref "C78") (pin "2") (pinfunction "2_2") (pintype "passive"))
      (node (ref "L7") (pin "2") (pinfunction "2_2") (pintype "passive"))
      (node (ref "U3") (pin "14") (pinfunction "VPOS_14") (pintype "bidirectional"))
    )
    (net (code "119") (name "Net-(U4-MODE)") (class "Default")
      (node (ref "R55") (pin "1") (pinfunction "1_1") (pintype "passive"))
      (node (ref "R56") (pin "2") (pinfunction "2_2") (pintype "passive"))
      (node (ref "U4") (pin "2") (pinfunction "MODE_2") (pintype "bidirectional"))
    )
    (net (code "120") (name "Net-(U4-REFB)") (class "Default")
      (node (ref "C91") (pin "2") (pinfunction "2_2") (pintype "passive"))
      (node (ref "C92") (pin "2") (pinfunction "2_2") (pintype "passive"))
      (node (ref "C93") (pin "1") (pinfunction "1_1") (pintype "passive"))
      (node (ref "U4") (pin "5") (pinfunction "REFB_5") (pintype "bidirectional"))
    )
    (net (code "121") (name "Net-(U4-REFT)") (class "Default")
      (node (ref "C91") (pin "1") (pinfunction "1_1") (pintype "passive"))
      (node (ref "C92") (pin "1") (pinfunction "1_1") (pintype "passive"))
      (node (ref "C94") (pin "1") (pinfunction "1_1") (pintype "passive"))
      (node (ref "U4") (pin "6") (pinfunction "REFT_6") (pintype "bidirectional"))
    )
    (net (code "122") (name "Net-(U4-VIN+)") (class "Default")
      (node (ref "C87") (pin "2") (pinfunction "2_2") (pintype "passive"))
      (node (ref "R46") (pin "2") (pinfunction "2_2") (pintype "passive"))
      (node (ref "R48") (pin "1") (pinfunction "1_1") (pintype "passive"))
      (node (ref "R49") (pin "1") (pinfunction "1_1") (pintype "passive"))
      (node (ref "U4") (pin "9") (pinfunction "VIN+_9") (pintype "bidirectional"))
    )
    (net (code "123") (name "Net-(U4-VIN-)") (class "Default")
      (node (ref "C88") (pin "1") (pinfunction "1_1") (pintype "passive"))
      (node (ref "R47") (pin "2") (pinfunction "2_2") (pintype "passive"))
      (node (ref "R50") (pin "2") (pinfunction "2_2") (pintype "passive"))
      (node (ref "R51") (pin "2") (pinfunction "2_2") (pintype "passive"))
      (node (ref "U4") (pin "10") (pinfunction "VIN-_10") (pintype "bidirectional"))
    )
    (net (code "124") (name "Net-(U4-VREF)") (class "Default")
      (node (ref "C95") (pin "2") (pinfunction "2_2") (pintype "passive"))
      (node (ref "C96") (pin "2") (pinfunction "2_2") (pintype "passive"))
      (node (ref "U4") (pin "4") (pinfunction "VREF_4") (pintype "bidirectional"))
    )
    (net (code "125") (name "Net-(U5-SW1)") (class "Default")
      (node (ref "L2") (pin "1") (pinfunction "1_1") (pintype "passive"))
      (node (ref "U5") (pin "4") (pinfunction "SW1_4") (pintype "output"))
    )
    (net (code "126") (name "Net-(U5-SW2)") (class "Default")
      (node (ref "L3") (pin "1") (pinfunction "1_1") (pintype "passive"))
      (node (ref "U5") (pin "8") (pinfunction "SW2_8") (pintype "output"))
    )
    (net (code "127") (name "Net-(U5-VFB1)") (class "Default")
      (node (ref "R24") (pin "2") (pinfunction "2_2") (pintype "passive"))
      (node (ref "R25") (pin "2") (pinfunction "2_2") (pintype "passive"))
      (node (ref "U5") (pin "1") (pinfunction "VFB1_1") (pintype "input"))
    )
    (net (code "128") (name "Net-(U5-VFB2)") (class "Default")
      (node (ref "R26") (pin "2") (pinfunction "2_2") (pintype "passive"))
      (node (ref "R30") (pin "2") (pinfunction "2_2") (pintype "passive"))
      (node (ref "U5") (pin "10") (pinfunction "VFB2_10") (pintype "input"))
    )
    (net (code "129") (name "Net-(U8-G)") (class "Default")
      (node (ref "JP8") (pin "2") (pinfunction "2_2") (pintype "passive"))
      (node (ref "R37") (pin "1") (pinfunction "1_1") (pintype "passive"))
      (node (ref "R65") (pin "1") (pinfunction "1_1") (pintype "passive"))
      (node (ref "U8") (pin "4") (pinfunction "G_4") (pintype "bidirectional"))
    )
    (net (code "130") (name "Net-(U9-MISO)") (class "Default")
      (node (ref "R22") (pin "1") (pinfunction "1_1") (pintype "passive"))
      (node (ref "U9") (pin "2") (pinfunction "MISO_2") (pintype "bidirectional"))
    )
    (net (code "131") (name "Net-(U10-BP)") (class "Default")
      (node (ref "C112") (pin "2") (pinfunction "2_2") (pintype "passive"))
      (node (ref "U10") (pin "4") (pinfunction "BP_4") (pintype "input"))
    )
    (net (code "132") (name "Net-(U10-EN)") (class "Default")
      (node (ref "C110") (pin "2") (pinfunction "2_2") (pintype "passive"))
      (node (ref "L9") (pin "2") (pinfunction "2_2") (pintype "passive"))
      (node (ref "U10") (pin "1") (pinfunction "IN_1") (pintype "input"))
      (node (ref "U10") (pin "3") (pinfunction "EN_3") (pintype "input"))
    )
    (net (code "133") (name "PWRON") (class "Default")
      (node (ref "R23") (pin "1") (pinfunction "1_1") (pintype "passive"))
      (node (ref "T2") (pin "3") (pinfunction "G_3") (pintype "passive"))
      (node (ref "U1") (pin "85") (pinfunction "PA29_85") (pintype "bidirectional"))
    )
    (net (code "134") (name "RXD0") (class "Default")
      (node (ref "U1") (pin "18") (pinfunction "PA19/PGMD11_18") (pintype "bidirectional"))
      (node (ref "U2") (pin "P134") (pinfunction "IO_L34P_GCLK19_0_P134") (pintype "bidirectional"))
    )
    (net (code "135") (name "RXD2") (class "Default")
      (node (ref "U1") (pin "21") (pinfunction "PA23/PGMD15_21") (pintype "bidirectional"))
      (node (ref "U2") (pin "P132") (pinfunction "IO_L35P_GCLK17_0_P132") (pintype "bidirectional"))
    )
    (net (code "136") (name "SAM_CS0") (class "Default")
      (node (ref "U1") (pin "13") (pinfunction "PA16/PGMD8_13") (pintype "bidirectional"))
      (node (ref "U2") (pin "P139") (pinfunction "IO_L3N_0_P139") (pintype "bidirectional"))
    )
    (net (code "137") (name "SAM_CS1") (class "Default")
      (node (ref "U1") (pin "26") (pinfunction "PA0/PGMNCMD_26") (pintype "bidirectional"))
      (node (ref "U2") (pin "P127") (pinfunction "IO_L36P_GCLK15_0_P127") (pintype "bidirectional"))
    )
    (net (code "138") (name "SAM_CS2") (class "Default")
      (node (ref "U1") (pin "27") (pinfunction "PA1/PGMRDY_27") (pintype "bidirectional"))
    )
    (net (code "139") (name "SAM_MISO") (class "Default")
      (node (ref "U1") (pin "10") (pinfunction "PA13/PGMD5_10") (pintype "bidirectional"))
      (node (ref "U2") (pin "P50") (pinfunction "IO_L31N_GCLK30_D15_2_P50") (pintype "bidirectional"))
    )
    (net (code "140") (name "SAM_MOSI") (class "Default")
      (node (ref "R6") (pin "1") (pinfunction "1_1") (pintype "passive"))
      (node (ref "U1") (pin "11") (pinfunction "PA14/PGMD6_11") (pintype "bidirectional"))
    )
    (net (code "141") (name "SAM_PDIC") (class "Default")
      (node (ref "R36") (pin "2") (pinfunction "2_2") (pintype "passive"))
      (node (ref "U1") (pin "23") (pinfunction "PA24_23") (pintype "bidirectional"))
    )
    (net (code "142") (name "SAM_PDID") (class "Default")
      (node (ref "R10") (pin "2") (pinfunction "2_2") (pintype "passive"))
      (node (ref "R2") (pin "2") (pinfunction "2_2") (pintype "passive"))
      (node (ref "R35") (pin "2") (pinfunction "2_2") (pintype "passive"))
    )
    (net (code "143") (name "SAM_SCK") (class "Default")
      (node (ref "R5") (pin "2") (pinfunction "2_2") (pintype "passive"))
      (node (ref "U1") (pin "12") (pinfunction "PA15/PGMD7_12") (pintype "bidirectional"))
    )
    (net (code "144") (name "SC_AUX1") (class "Default")
      (node (ref "J7") (pin "7") (pinfunction "7_7") (pintype "passive"))
      (node (ref "U1") (pin "30") (pinfunction "PA4/PGMM0_30") (pintype "bidirectional"))
      (node (ref "U2") (pin "P124") (pinfunction "IO_L37P_GCLK13_0_P124") (pintype "bidirectional"))
    )
    (net (code "145") (name "SC_AUX2") (class "Default")
      (node (ref "J7") (pin "8") (pinfunction "8_8") (pintype "passive"))
      (node (ref "U1") (pin "31") (pinfunction "PA5/PGMM1_31") (pintype "bidirectional"))
      (node (ref "U2") (pin "P123") (pinfunction "IO_L37N_GCLK12_0_P123") (pintype "bidirectional"))
    )
    (net (code "146") (name "SC_PRESENT") (class "Default")
      (node (ref "R63") (pin "1") (pinfunction "1_1") (pintype "passive"))
      (node (ref "U1") (pin "28") (pinfunction "PA2/PGMNOE_28") (pintype "bidirectional"))
    )
    (net (code "147") (name "SC_RESET") (class "Default")
      (node (ref "J7") (pin "3") (pinfunction "3_3") (pintype "passive"))
      (node (ref "U1") (pin "29") (pinfunction "PA3/PGMNVALID_29") (pintype "bidirectional"))
      (node (ref "U2") (pin "P126") (pinfunction "IO_L36N_GCLK14_0_P126") (pintype "bidirectional"))
    )
    (net (code "148") (name "TARGET_NRST") (class "Default")
      (node (ref "U1") (pin "14") (pinfunction "PA17/PGMD9_14") (pintype "bidirectional"))
      (node (ref "U2") (pin "P138") (pinfunction "IO_L4P_0_P138") (pintype "bidirectional"))
    )
    (net (code "149") (name "TCK") (class "Default")
      (node (ref "J3") (pin "11") (pinfunction "11_11") (pintype "passive"))
      (node (ref "J3") (pin "9") (pinfunction "9_9") (pintype "passive"))
      (node (ref "R18") (pin "1") (pinfunction "1_1") (pintype "passive"))
      (node (ref "U1") (pin "56") (pinfunction "TCK/SWCLK_56") (pintype "input"))
    )
    (net (code "150") (name "TDI") (class "Default")
      (node (ref "J3") (pin "5") (pinfunction "5_5") (pintype "passive"))
      (node (ref "R20") (pin "1") (pinfunction "1_1") (pintype "passive"))
      (node (ref "U1") (pin "51") (pinfunction "TDI_51") (pintype "input"))
    )
    (net (code "151") (name "TDO") (class "Default")
      (node (ref "J3") (pin "13") (pinfunction "13_13") (pintype "passive"))
      (node (ref "U1") (pin "54") (pinfunction "TDO/TRACESWO_54") (pintype "output"))
    )
    (net (code "152") (name "THS1") (class "Default")
      (node (ref "J1") (pin "4") (pinfunction "4_4") (pintype "passive"))
      (node (ref "JP9") (pin "3") (pinfunction "3_3") (pintype "passive"))
      (node (ref "U2") (pin "P93") (pinfunction "IO_L41P_GCLK9_IRDY1_1_P93") (pintype "bidirectional"))
    )
    (net (code "153") (name "THS2") (class "Default")
      (node (ref "J1") (pin "6") (pinfunction "6_6") (pintype "passive"))
      (node (ref "JP9") (pin "2") (pinfunction "2_2") (pintype "passive"))
      (node (ref "U2") (pin "P95") (pinfunction "IO_L40P_GCLK11_1_P95") (pintype "bidirectional"))
    )
    (net (code "154") (name "TIO1") (class "Default")
      (node (ref "J1") (pin "10") (pinfunction "10_10") (pintype "passive"))
      (node (ref "JP9") (pin "6") (pinfunction "6_6") (pintype "passive"))
      (node (ref "U2") (pin "P87") (pinfunction "IO_L42N_GCLK6_TRDY1_1_P87") (pintype "bidirectional"))
    )
    (net (code "155") (name "TIO2") (class "Default")
      (node (ref "J1") (pin "12") (pinfunction "12_12") (pintype "passive"))
      (node (ref "JP9") (pin "7") (pinfunction "7_7") (pintype "passive"))
      (node (ref "U2") (pin "P84") (pinfunction "IO_L43N_GCLK4_1_P84") (pintype "bidirectional"))
    )
    (net (code "156") (name "TIO3") (class "Default")
      (node (ref "J1") (pin "14") (pinfunction "14_14") (pintype "passive"))
      (node (ref "JP9") (pin "8") (pinfunction "8_8") (pintype "passive"))
      (node (ref "U2") (pin "P82") (pinfunction "IO_L45N_1_P82") (pintype "bidirectional"))
    )
    (net (code "157") (name "TIO4") (class "Default")
      (node (ref "J1") (pin "16") (pinfunction "16_16") (pintype "passive"))
      (node (ref "JP9") (pin "9") (pinfunction "9_9") (pintype "passive"))
      (node (ref "U2") (pin "P80") (pinfunction "IO_L46N_1_P80") (pintype "bidirectional"))
    )
    (net (code "158") (name "TMISO") (class "Default")
      (node (ref "J1") (pin "7") (pinfunction "7_7") (pintype "passive"))
      (node (ref "U2") (pin "P92") (pinfunction "IO_L41N_GCLK8_1_P92") (pintype "bidirectional"))
    )
    (net (code "159") (name "TMOSI") (class "Default")
      (node (ref "J1") (pin "9") (pinfunction "9_9") (pintype "passive"))
      (node (ref "U2") (pin "P88") (pinfunction "IO_L42P_GCLK7_1_P88") (pintype "bidirectional"))
    )
    (net (code "160") (name "TMS") (class "Default")
      (node (ref "J3") (pin "7") (pinfunction "7_7") (pintype "passive"))
      (node (ref "R19") (pin "1") (pinfunction "1_1") (pintype "passive"))
      (node (ref "U1") (pin "55") (pinfunction "TMS/SWDIO_55") (pintype "bidirectional"))
    )
    (net (code "161") (name "TPDIC") (class "Default")
      (node (ref "J1") (pin "13") (pinfunction "13_13") (pintype "passive"))
      (node (ref "R36") (pin "1") (pinfunction "1_1") (pintype "passive"))
      (node (ref "U2") (pin "P83") (pinfunction "IO_L45P_1_P83") (pintype "bidirectional"))
    )
    (net (code "162") (name "TPDID") (class "Default")
      (node (ref "J1") (pin "15") (pinfunction "15_15") (pintype "passive"))
      (node (ref "R35") (pin "1") (pinfunction "1_1") (pintype "passive"))
      (node (ref "U2") (pin "P81") (pinfunction "IO_L46P_1_P81") (pintype "bidirectional"))
    )
    (net (code "163") (name "TRST") (class "Default")
      (node (ref "J1") (pin "5") (pinfunction "5_5") (pintype "passive"))
      (node (ref "U2") (pin "P94") (pinfunction "IO_L40N_GCLK10_1_P94") (pintype "bidirectional"))
    )
    (net (code "164") (name "TSCK") (class "Default")
      (node (ref "J1") (pin "11") (pinfunction "11_11") (pintype "passive"))
      (node (ref "U2") (pin "P85") (pinfunction "IO_L43P_GCLK5_1_P85") (pintype "bidirectional"))
    )
    (net (code "165") (name "TVREF") (class "Default")
      (node (ref "J1") (pin "8") (pinfunction "8_8") (pintype "passive"))
      (node (ref "JP5") (pin "3") (pinfunction "3_3") (pintype "passive"))
      (node (ref "JP9") (pin "5") (pinfunction "5_5") (pintype "passive"))
    )
    (net (code "166") (name "TXD0") (class "Default")
      (node (ref "U1") (pin "17") (pinfunction "PA18/PGMD10_17") (pintype "bidirectional"))
      (node (ref "U2") (pin "P137") (pinfunction "IO_L4N_0_P137") (pintype "bidirectional"))
    )
    (net (code "167") (name "TXD2") (class "Default")
      (node (ref "J7") (pin "6") (pinfunction "6_6") (pintype "passive"))
      (node (ref "R64") (pin "1") (pinfunction "1_1") (pintype "passive"))
      (node (ref "U1") (pin "5") (pinfunction "PA22/PGMD14_5") (pintype "bidirectional"))
      (node (ref "U2") (pin "P133") (pinfunction "IO_L34N_GCLK18_0_P133") (pintype "bidirectional"))
    )
    (net (code "168") (name "USBCK0") (class "Default")
      (node (ref "C1") (pin "1") (pinfunction "1_1") (pintype "passive"))
      (node (ref "R14") (pin "2") (pinfunction "2_2") (pintype "passive"))
      (node (ref "U2") (pin "P14") (pinfunction "IO_L44N_GCLK20_3_P14") (pintype "bidirectional"))
    )
    (net (code "169") (name "USBCK1") (class "Default")
      (node (ref "C2") (pin "1") (pinfunction "1_1") (pintype "passive"))
      (node (ref "R1") (pin "2") (pinfunction "2_2") (pintype "passive"))
      (node (ref "U2") (pin "P24") (pinfunction "IO_L41P_GCLK27_3_P24") (pintype "bidirectional"))
    )
    (net (code "170") (name "USBSPARE0") (class "Default")
      (node (ref "U1") (pin "68") (pinfunction "PB17_68") (pintype "bidirectional"))
      (node (ref "U2") (pin "P23") (pinfunction "IO_L41N_GCLK26_3_P23") (pintype "bidirectional"))
    )
    (net (code "171") (name "USBSPARE1") (class "Default")
      (node (ref "U1") (pin "67") (pinfunction "PB18_67") (pintype "bidirectional"))
      (node (ref "U2") (pin "P26") (pinfunction "IO_L37N_3_P26") (pintype "bidirectional"))
    )
    (net (code "172") (name "USBSPARE2") (class "Default")
      (node (ref "U1") (pin "63") (pinfunction "PB22_63") (pintype "bidirectional"))
      (node (ref "U2") (pin "P32") (pinfunction "IO_L2N_3_P32") (pintype "bidirectional"))
    )
    (net (code "173") (name "USB_AD0") (class "Default")
      (node (ref "U1") (pin "90") (pinfunction "PB0_90") (pintype "bidirectional"))
      (node (ref "U2") (pin "P12") (pinfunction "IO_L49P_3_P12") (pintype "bidirectional"))
    )
    (net (code "174") (name "USB_AD1") (class "Default")
      (node (ref "U1") (pin "91") (pinfunction "PB1_91") (pintype "bidirectional"))
      (node (ref "U2") (pin "P11") (pinfunction "IO_L49N_3_P11") (pintype "bidirectional"))
    )
    (net (code "175") (name "USB_AD2") (class "Default")
      (node (ref "U1") (pin "92") (pinfunction "PB2_92") (pintype "bidirectional"))
      (node (ref "U2") (pin "P10") (pinfunction "IO_L50P_3_P10") (pintype "bidirectional"))
    )
    (net (code "176") (name "USB_AD3") (class "Default")
      (node (ref "U1") (pin "7") (pinfunction "PB3_7") (pintype "bidirectional"))
      (node (ref "U2") (pin "P15") (pinfunction "IO_L44P_GCLK21_3_P15") (pintype "bidirectional"))
    )
    (net (code "177") (name "USB_AD4") (class "Default")
      (node (ref "U1") (pin "8") (pinfunction "PB4_8") (pintype "bidirectional"))
      (node (ref "U2") (pin "P16") (pinfunction "IO_L43N_GCLK22_IRDY2_3_P16") (pintype "bidirectional"))
    )
    (net (code "178") (name "USB_AD5") (class "Default")
      (node (ref "U1") (pin "97") (pinfunction "PB5_97") (pintype "bidirectional"))
      (node (ref "U2") (pin "P6") (pinfunction "IO_L52P_3_P6") (pintype "bidirectional"))
    )
    (net (code "179") (name "USB_AD6") (class "Default")
      (node (ref "U1") (pin "98") (pinfunction "PB6_98") (pintype "bidirectional"))
      (node (ref "U2") (pin "P5") (pinfunction "IO_L52N_3_P5") (pintype "bidirectional"))
    )
    (net (code "180") (name "USB_AD7") (class "Default")
      (node (ref "U1") (pin "99") (pinfunction "PB7_99") (pintype "bidirectional"))
      (node (ref "U2") (pin "P2") (pinfunction "IO_L83P_3_P2") (pintype "bidirectional"))
    )
    (net (code "181") (name "USB_AD8") (class "Default")
      (node (ref "U1") (pin "100") (pinfunction "PB8_100") (pintype "bidirectional"))
      (node (ref "U2") (pin "P1") (pinfunction "IO_L83N_VREF_3_P1") (pintype "bidirectional"))
    )
    (net (code "182") (name "USB_D0") (class "Default")
      (node (ref "U1") (pin "71") (pinfunction "PB9_71") (pintype "bidirectional"))
      (node (ref "U2") (pin "P17") (pinfunction "IO_L43P_GCLK23_3_P17") (pintype "bidirectional"))
    )
    (net (code "183") (name "USB_D1") (class "Default")
      (node (ref "U1") (pin "70") (pinfunction "PB10_70") (pintype "bidirectional"))
      (node (ref "U2") (pin "P21") (pinfunction "IO_L42N_GCLK24_3_P21") (pintype "bidirectional"))
    )
    (net (code "184") (name "USB_D2") (class "Default")
      (node (ref "U1") (pin "93") (pinfunction "PB11_93") (pintype "bidirectional"))
      (node (ref "U2") (pin "P9") (pinfunction "IO_L50N_3_P9") (pintype "bidirectional"))
    )
    (net (code "185") (name "USB_D3") (class "Default")
      (node (ref "U1") (pin "94") (pinfunction "PB12_94") (pintype "bidirectional"))
      (node (ref "U2") (pin "P8") (pinfunction "IO_L51P_3_P8") (pintype "bidirectional"))
    )
    (net (code "186") (name "USB_D4") (class "Default")
      (node (ref "U1") (pin "95") (pinfunction "PB13_95") (pintype "bidirectional"))
      (node (ref "U2") (pin "P7") (pinfunction "IO_L51N_3_P7") (pintype "bidirectional"))
    )
    (net (code "187") (name "USB_D5") (class "Default")
      (node (ref "U1") (pin "69") (pinfunction "PB14_69") (pintype "bidirectional"))
      (node (ref "U2") (pin "P22") (pinfunction "IO_L42P_GCLK25_TRDY2_3_P22") (pintype "bidirectional"))
    )
    (net (code "188") (name "USB_D6") (class "Default")
      (node (ref "U1") (pin "16") (pinfunction "PB15_16") (pintype "bidirectional"))
      (node (ref "U2") (pin "P35") (pinfunction "IO_L1P_3_P35") (pintype "bidirectional"))
    )
    (net (code "189") (name "USB_D7") (class "Default")
      (node (ref "U1") (pin "15") (pinfunction "PB16_15") (pintype "bidirectional"))
      (node (ref "U2") (pin "P34") (pinfunction "IO_L1N_VREF_3_P34") (pintype "bidirectional"))
    )
    (net (code "190") (name "VBUS") (class "Default")
      (node (ref "C39") (pin "1") (pinfunction "1_1") (pintype "passive"))
      (node (ref "C44") (pin "1") (pinfunction "1_1") (pintype "passive"))
      (node (ref "C45") (pin "1") (pinfunction "1_1") (pintype "passive"))
      (node (ref "L6") (pin "2") (pinfunction "2_2") (pintype "passive"))
      (node (ref "R33") (pin "2") (pinfunction "2_2") (pintype "passive"))
      (node (ref "U7") (pin "1") (pinfunction "IN_1") (pintype "input"))
    )
    (net (code "191") (name "VBUSDETECT") (class "Default")
      (node (ref "R33") (pin "1") (pinfunction "1_1") (pintype "passive"))
      (node (ref "R34") (pin "2") (pinfunction "2_2") (pintype "passive"))
      (node (ref "U1") (pin "6") (pinfunction "PA30_6") (pintype "bidirectional"))
    )
    (net (code "192") (name "VBUS_SWITCHED") (class "Default")
      (node (ref "C36") (pin "1") (pinfunction "1_1") (pintype "passive"))
      (node (ref "C42") (pin "1") (pinfunction "1_1") (pintype "passive"))
      (node (ref "C43") (pin "1") (pinfunction "1_1") (pintype "passive"))
      (node (ref "L4") (pin "2") (pinfunction "2_2") (pintype "passive"))
      (node (ref "U5") (pin "2") (pinfunction "RUN1_2") (pintype "input"))
      (node (ref "U5") (pin "3") (pinfunction "MODE_3") (pintype "input"))
      (node (ref "U5") (pin "7") (pinfunction "VIN_7") (pintype "input"))
    )
    (net (code "193") (name "VCCGLITCH") (class "Default")
      (node (ref "JP11") (pin "2") (pinfunction "2_2") (pintype "passive"))
      (node (ref "T4") (pin "1") (pinfunction "D_1") (pintype "passive"))
      (node (ref "U8") (pin "5") (pinfunction "D_5") (pintype "bidirectional"))
      (node (ref "U8") (pin "6") (pinfunction "D_6") (pintype "bidirectional"))
      (node (ref "U8") (pin "7") (pinfunction "D_7") (pintype "bidirectional"))
      (node (ref "U8") (pin "8") (pinfunction "D_8") (pintype "bidirectional"))
      (node (ref "X4") (pin "1") (pinfunction "1_1") (pintype "passive"))
    )
    (net (code "194") (name "VCCINT") (class "Default")
      (node (ref "C27") (pin "1") (pinfunction "1_1") (pintype "passive"))
      (node (ref "C28") (pin "1") (pinfunction "1_1") (pintype "passive"))
      (node (ref "C29") (pin "1") (pinfunction "1_1") (pintype "passive"))
      (node (ref "C30") (pin "1") (pinfunction "1_1") (pintype "passive"))
      (node (ref "C31") (pin "1") (pinfunction "1_1") (pintype "passive"))
      (node (ref "C32") (pin "1") (pinfunction "1_1") (pintype "passive"))
      (node (ref "C35") (pin "1") (pinfunction "1_1") (pintype "passive"))
      (node (ref "L3") (pin "2") (pinfunction "2_2") (pintype "passive"))
      (node (ref "R30") (pin "1") (pinfunction "1_1") (pintype "passive"))
      (node (ref "U2") (pin "P128") (pinfunction "VCCINT_P128") (pintype "input"))
      (node (ref "U2") (pin "P19") (pinfunction "VCCINT_P19") (pintype "input"))
      (node (ref "U2") (pin "P28") (pinfunction "VCCINT_P28") (pintype "input"))
      (node (ref "U2") (pin "P52") (pinfunction "VCCINT_P52") (pintype "input"))
      (node (ref "U2") (pin "P89") (pinfunction "VCCINT_P89") (pintype "input"))
    )
    (net (code "195") (name "VCCIO") (class "Default")
      (node (ref "C114") (pin "2") (pinfunction "2_2") (pintype "passive"))
      (node (ref "C20") (pin "1") (pinfunction "1_1") (pintype "passive"))
      (node (ref "C22") (pin "1") (pinfunction "1_1") (pintype "passive"))
      (node (ref "C23") (pin "1") (pinfunction "1_1") (pintype "passive"))
      (node (ref "C24") (pin "1") (pinfunction "1_1") (pintype "passive"))
      (node (ref "C25") (pin "1") (pinfunction "1_1") (pintype "passive"))
      (node (ref "C26") (pin "1") (pinfunction "1_1") (pintype "passive"))
      (node (ref "C34") (pin "1") (pinfunction "1_1") (pintype "passive"))
      (node (ref "C49") (pin "2") (pinfunction "2_2") (pintype "passive"))
      (node (ref "C52") (pin "1") (pinfunction "1_1") (pintype "passive"))
      (node (ref "C53") (pin "1") (pinfunction "1_1") (pintype "passive"))
      (node (ref "C54") (pin "1") (pinfunction "1_1") (pintype "passive"))
      (node (ref "C55") (pin "1") (pinfunction "1_1") (pintype "passive"))
      (node (ref "C56") (pin "1") (pinfunction "1_1") (pintype "passive"))
      (node (ref "C57") (pin "1") (pinfunction "1_1") (pintype "passive"))
      (node (ref "C58") (pin "1") (pinfunction "1_1") (pintype "passive"))
      (node (ref "C59") (pin "1") (pinfunction "1_1") (pintype "passive"))
      (node (ref "C60") (pin "1") (pinfunction "1_1") (pintype "passive"))
      (node (ref "C61") (pin "1") (pinfunction "1_1") (pintype "passive"))
      (node (ref "C62") (pin "1") (pinfunction "1_1") (pintype "passive"))
      (node (ref "C83") (pin "2") (pinfunction "2_2") (pintype "passive"))
      (node (ref "C84") (pin "2") (pinfunction "2_2") (pintype "passive"))
      (node (ref "J4") (pin "1") (pinfunction "+V_1") (pintype "passive"))
      (node (ref "JP5") (pin "1") (pinfunction "1_1") (pintype "passive"))
      (node (ref "L2") (pin "2") (pinfunction "2_2") (pintype "passive"))
      (node (ref "L9") (pin "1") (pinfunction "1_1") (pintype "passive"))
      (node (ref "R11") (pin "2") (pinfunction "2_2") (pintype "passive"))
      (node (ref "R12") (pin "2") (pinfunction "2_2") (pintype "passive"))
      (node (ref "R25") (pin "1") (pinfunction "1_1") (pintype "passive"))
      (node (ref "R3") (pin "1") (pinfunction "1_1") (pintype "passive"))
      (node (ref "R59") (pin "1") (pinfunction "1_1") (pintype "passive"))
      (node (ref "R68") (pin "2") (pinfunction "2_2") (pintype "passive"))
      (node (ref "R69") (pin "1") (pinfunction "1_1") (pintype "passive"))
      (node (ref "R7") (pin "1") (pinfunction "1_1") (pintype "passive"))
      (node (ref "R70") (pin "1") (pinfunction "1_1") (pintype "passive"))
      (node (ref "R9") (pin "2") (pinfunction "2_2") (pintype "passive"))
      (node (ref "SJ6") (pin "1") (pinfunction "1_1") (pintype "passive"))
      (node (ref "T3") (pin "2") (pinfunction "S_2") (pintype "passive"))
      (node (ref "U2") (pin "P122") (pinfunction "VCCO_0_P122") (pintype "input"))
      (node (ref "U2") (pin "P125") (pinfunction "VCCO_0_P125") (pintype "input"))
      (node (ref "U2") (pin "P129") (pinfunction "VCCAUX_P129") (pintype "input"))
      (node (ref "U2") (pin "P135") (pinfunction "VCCO_0_P135") (pintype "input"))
      (node (ref "U2") (pin "P18") (pinfunction "VCCO_3_P18") (pintype "input"))
      (node (ref "U2") (pin "P20") (pinfunction "VCCAUX_P20") (pintype "input"))
      (node (ref "U2") (pin "P31") (pinfunction "VCCO_3_P31") (pintype "input"))
      (node (ref "U2") (pin "P36") (pinfunction "VCCAUX_P36") (pintype "input"))
      (node (ref "U2") (pin "P4") (pinfunction "VCCO_3_P4") (pintype "input"))
      (node (ref "U2") (pin "P42") (pinfunction "VCCO_2_P42") (pintype "input"))
      (node (ref "U2") (pin "P53") (pinfunction "VCCAUX_P53") (pintype "input"))
      (node (ref "U2") (pin "P63") (pinfunction "VCCO_2_P63") (pintype "input"))
      (node (ref "U2") (pin "P90") (pinfunction "VCCAUX_P90") (pintype "input"))
      (node (ref "U4") (pin "24") (pinfunction "DRVDD_24") (pintype "bidirectional"))
      (node (ref "U5") (pin "9") (pinfunction "RUN2_9") (pintype "input"))
      (node (ref "U9") (pin "3") (pinfunction "WP_3") (pintype "bidirectional"))
      (node (ref "U9") (pin "7") (pinfunction "HOLD_7") (pintype "bidirectional"))
      (node (ref "U9") (pin "8") (pinfunction "VCC_8") (pintype "bidirectional"))
    )
    (net (code "196") (name "VCCTIO_SWITCHED") (class "Default")
      (node (ref "J1") (pin "18") (pinfunction "18_18") (pintype "passive"))
      (node (ref "J1") (pin "3") (pinfunction "3_3") (pintype "passive"))
      (node (ref "T3") (pin "1") (pinfunction "D_1") (pintype "passive"))
    )
    (net (code "197") (name "VGA_GAIN") (class "Default")
      (node (ref "R53") (pin "1") (pinfunction "1_1") (pintype "passive"))
      (node (ref "U2") (pin "P62") (pinfunction "IO_L12P_D1_MISO2_2_P62") (pintype "bidirectional"))
    )
    (net (code "198") (name "VGA_HILOW") (class "Default")
      (node (ref "U2") (pin "P61") (pinfunction "IO_L12N_D2_MISO3_2_P61") (pintype "bidirectional"))
      (node (ref "U3") (pin "13") (pinfunction "HILO_13") (pintype "bidirectional"))
    )
    (net (code "199") (name "unconnected-(D1-CA-Pad1)") (class "Default")
      (node (ref "D1") (pin "1") (pinfunction "CA_1") (pintype "passive"))
    )
    (net (code "200") (name "unconnected-(H1-MOUNT-PadB2,8)") (class "Default")
      (node (ref "H1") (pin "B2,8") (pinfunction "MOUNT_B2,8") (pintype "passive"))
    )
    (net (code "201") (name "unconnected-(H2-MOUNT-PadB2,8)") (class "Default")
      (node (ref "H2") (pin "B2,8") (pinfunction "MOUNT_B2,8") (pintype "passive"))
    )
    (net (code "202") (name "unconnected-(H3-MOUNT-PadB2,8)") (class "Default")
      (node (ref "H3") (pin "B2,8") (pinfunction "MOUNT_B2,8") (pintype "passive"))
    )
    (net (code "203") (name "unconnected-(H4-MOUNT-PadB2,8)") (class "Default")
      (node (ref "H4") (pin "B2,8") (pinfunction "MOUNT_B2,8") (pintype "passive"))
    )
    (net (code "204") (name "unconnected-(J1-Pad1)") (class "Default")
      (node (ref "J1") (pin "1") (pinfunction "1_1") (pintype "passive"))
    )
    (net (code "205") (name "unconnected-(J1-Pad20)") (class "Default")
      (node (ref "J1") (pin "20") (pinfunction "20_20") (pintype "passive"))
    )
    (net (code "206") (name "unconnected-(J3-Pad17)") (class "Default")
      (node (ref "J3") (pin "17") (pinfunction "17_17") (pintype "passive"))
    )
    (net (code "207") (name "unconnected-(J3-Pad19)") (class "Default")
      (node (ref "J3") (pin "19") (pinfunction "19_19") (pintype "passive"))
    )
    (net (code "208") (name "unconnected-(J8-ID-Pad4)") (class "Default")
      (node (ref "J8") (pin "4") (pinfunction "ID_4") (pintype "bidirectional"))
    )
    (net (code "209") (name "unconnected-(U1-PA26-Pad25)") (class "Default")
      (node (ref "U1") (pin "25") (pinfunction "PA26_25") (pintype "bidirectional"))
    )
    (net (code "210") (name "unconnected-(U1-PA28-Pad84)") (class "Default")
      (node (ref "U1") (pin "84") (pinfunction "PA28_84") (pintype "bidirectional"))
    )
    (net (code "211") (name "unconnected-(U1-PA31-Pad86)") (class "Default")
      (node (ref "U1") (pin "86") (pinfunction "PA31_86") (pintype "bidirectional"))
    )
    (net (code "212") (name "unconnected-(U1-XIN32-Pad50)") (class "Default")
      (node (ref "U1") (pin "50") (pinfunction "XIN32_50") (pintype "input"))
    )
    (net (code "213") (name "unconnected-(U1-XOUT32-Pad49)") (class "Default")
      (node (ref "U1") (pin "49") (pinfunction "XOUT32_49") (pintype "output"))
    )
    (net (code "214") (name "unconnected-(U2B-IO_L1N_VREF_1-PadP104)") (class "Default")
      (node (ref "U2") (pin "P104") (pinfunction "IO_L1N_VREF_1_P104") (pintype "bidirectional"))
    )
    (net (code "215") (name "unconnected-(U2B-IO_L47N_1-PadP78)") (class "Default")
      (node (ref "U2") (pin "P78") (pinfunction "IO_L47N_1_P78") (pintype "bidirectional"))
    )
    (net (code "216") (name "unconnected-(U2B-IO_L47P_1-PadP79)") (class "Default")
      (node (ref "U2") (pin "P79") (pinfunction "IO_L47P_1_P79") (pintype "bidirectional"))
    )
    (net (code "217") (name "unconnected-(U2B-IO_L74N_DOUT_BUSY_1-PadP74)") (class "Default")
      (node (ref "U2") (pin "P74") (pinfunction "IO_L74N_DOUT_BUSY_1_P74") (pintype "bidirectional"))
    )
    (net (code "218") (name "unconnected-(U2B-IO_L74P_AWAKE_1-PadP75)") (class "Default")
      (node (ref "U2") (pin "P75") (pinfunction "IO_L74P_AWAKE_1_P75") (pintype "bidirectional"))
    )
    (net (code "219") (name "unconnected-(U2C-CMPCS_B_2-PadP72)") (class "Default")
      (node (ref "U2") (pin "P72") (pinfunction "CMPCS_B_2_P72") (pintype "bidirectional"))
    )
    (net (code "220") (name "unconnected-(U2C-IO_L31P_GCLK31_D14_2-PadP51)") (class "Default")
      (node (ref "U2") (pin "P51") (pinfunction "IO_L31P_GCLK31_D14_2_P51") (pintype "bidirectional"))
    )
    (net (code "221") (name "~{TIOVCC_ON}") (class "Default")
      (node (ref "R77") (pin "2") (pinfunction "2_2") (pintype "passive"))
      (node (ref "T3") (pin "3") (pinfunction "G_3") (pintype "passive"))
      (node (ref "U2") (pin "P121") (pinfunction "IO_L62P_0_P121") (pintype "bidirectional"))
    )
    (net (code "222") (name "~{USBALE}") (class "Default")
      (node (ref "U1") (pin "64") (pinfunction "PB21_64") (pintype "bidirectional"))
      (node (ref "U2") (pin "P30") (pinfunction "IO_L36P_3_P30") (pintype "bidirectional"))
    )
    (net (code "223") (name "~{USBCE}") (class "Default")
      (node (ref "U1") (pin "65") (pinfunction "PB20_65") (pintype "bidirectional"))
      (node (ref "U2") (pin "P29") (pinfunction "IO_L36N_3_P29") (pintype "bidirectional"))
    )
    (net (code "224") (name "~{USBRD}") (class "Default")
      (node (ref "U1") (pin "66") (pinfunction "PB19_66") (pintype "bidirectional"))
      (node (ref "U2") (pin "P27") (pinfunction "IO_L37P_3_P27") (pintype "bidirectional"))
    )
    (net (code "225") (name "~{USBWR}") (class "Default")
      (node (ref "U1") (pin "62") (pinfunction "PB23_62") (pintype "bidirectional"))
      (node (ref "U2") (pin "P33") (pinfunction "IO_L2P_3_P33") (pintype "bidirectional"))
    )
  )
)
